# WMHS_Team_A_Mission_Possible_Electrical.net
KiCad netlist of a schematic drawn in EAGLE
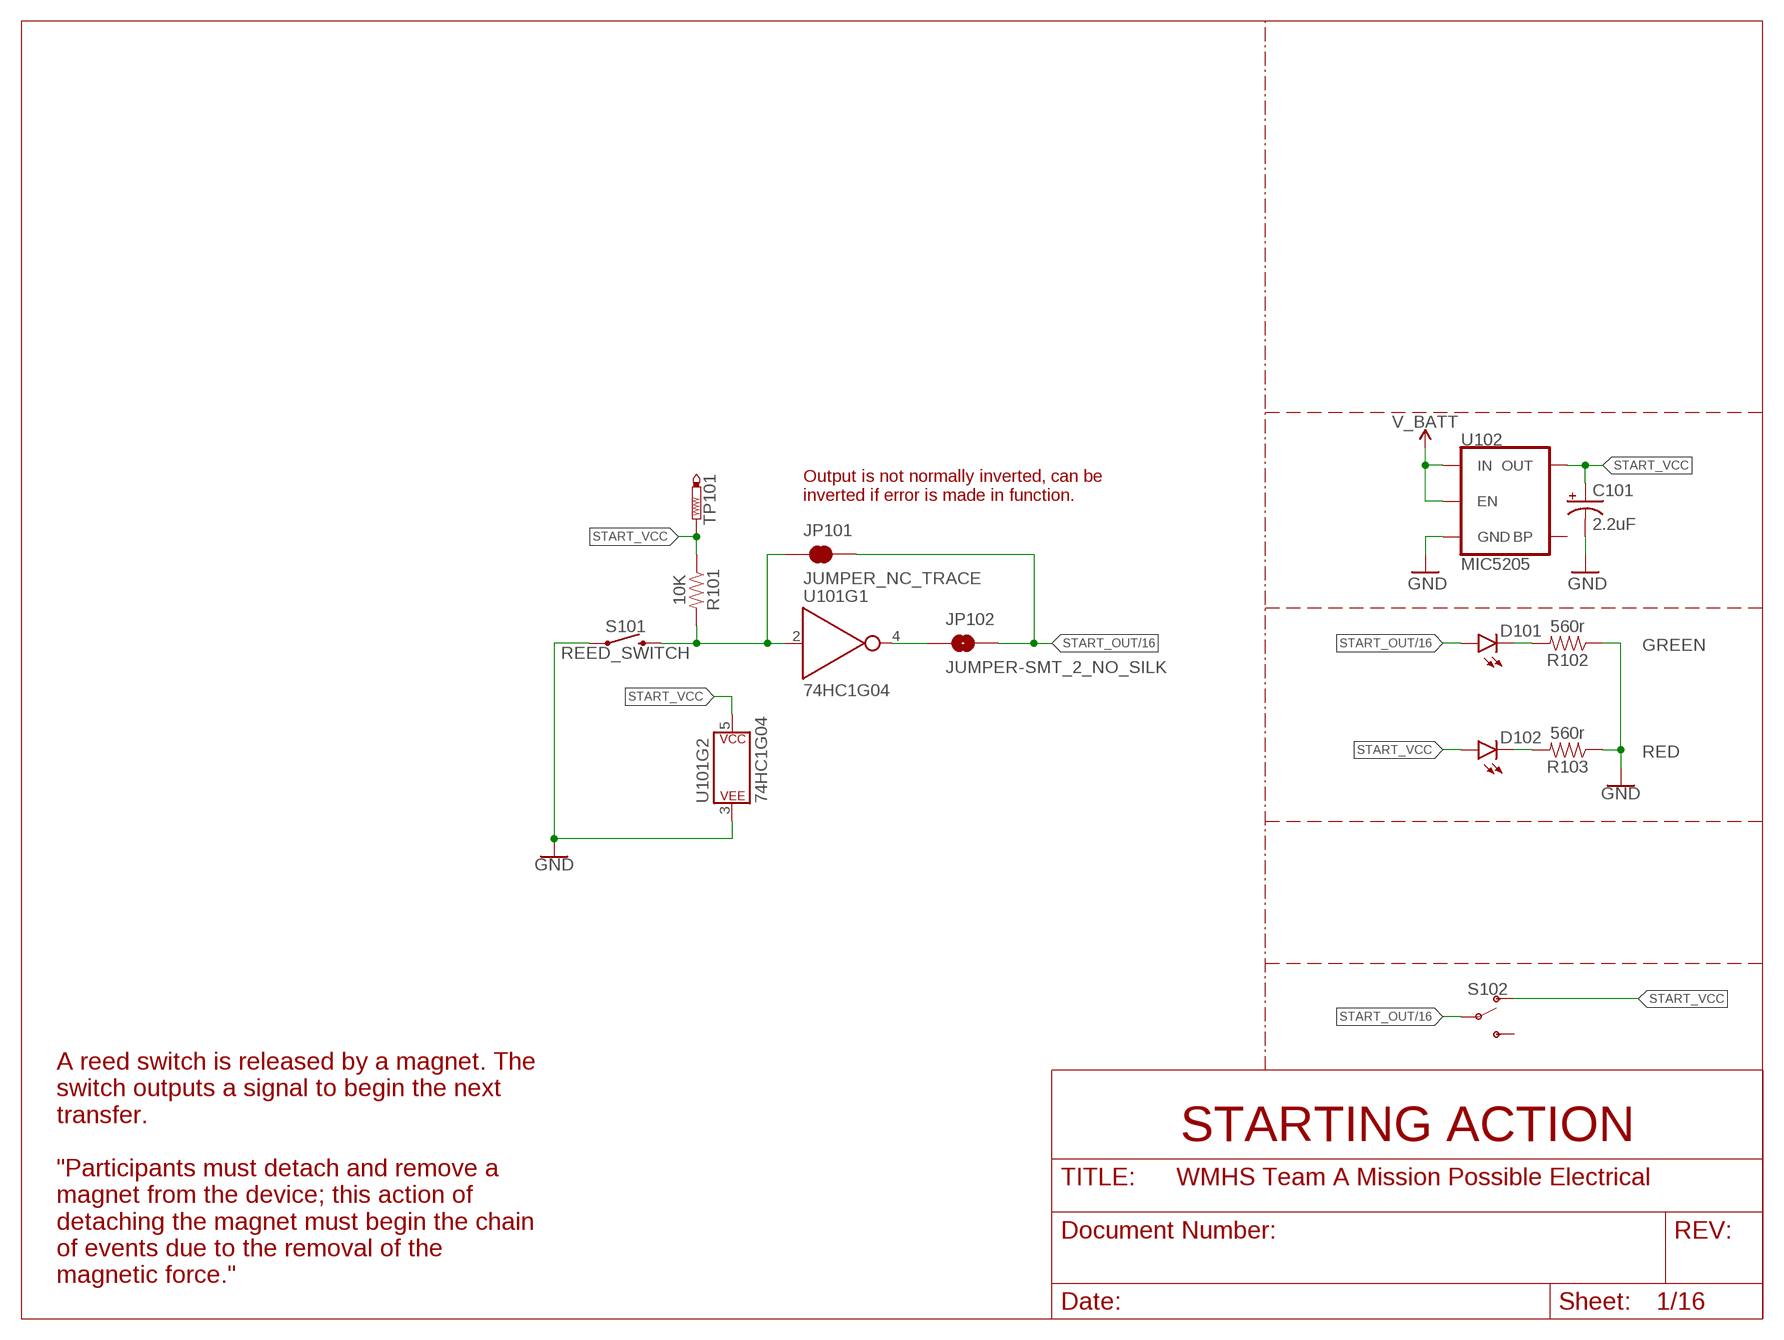
[diagram p0: schematic, sheet 1]
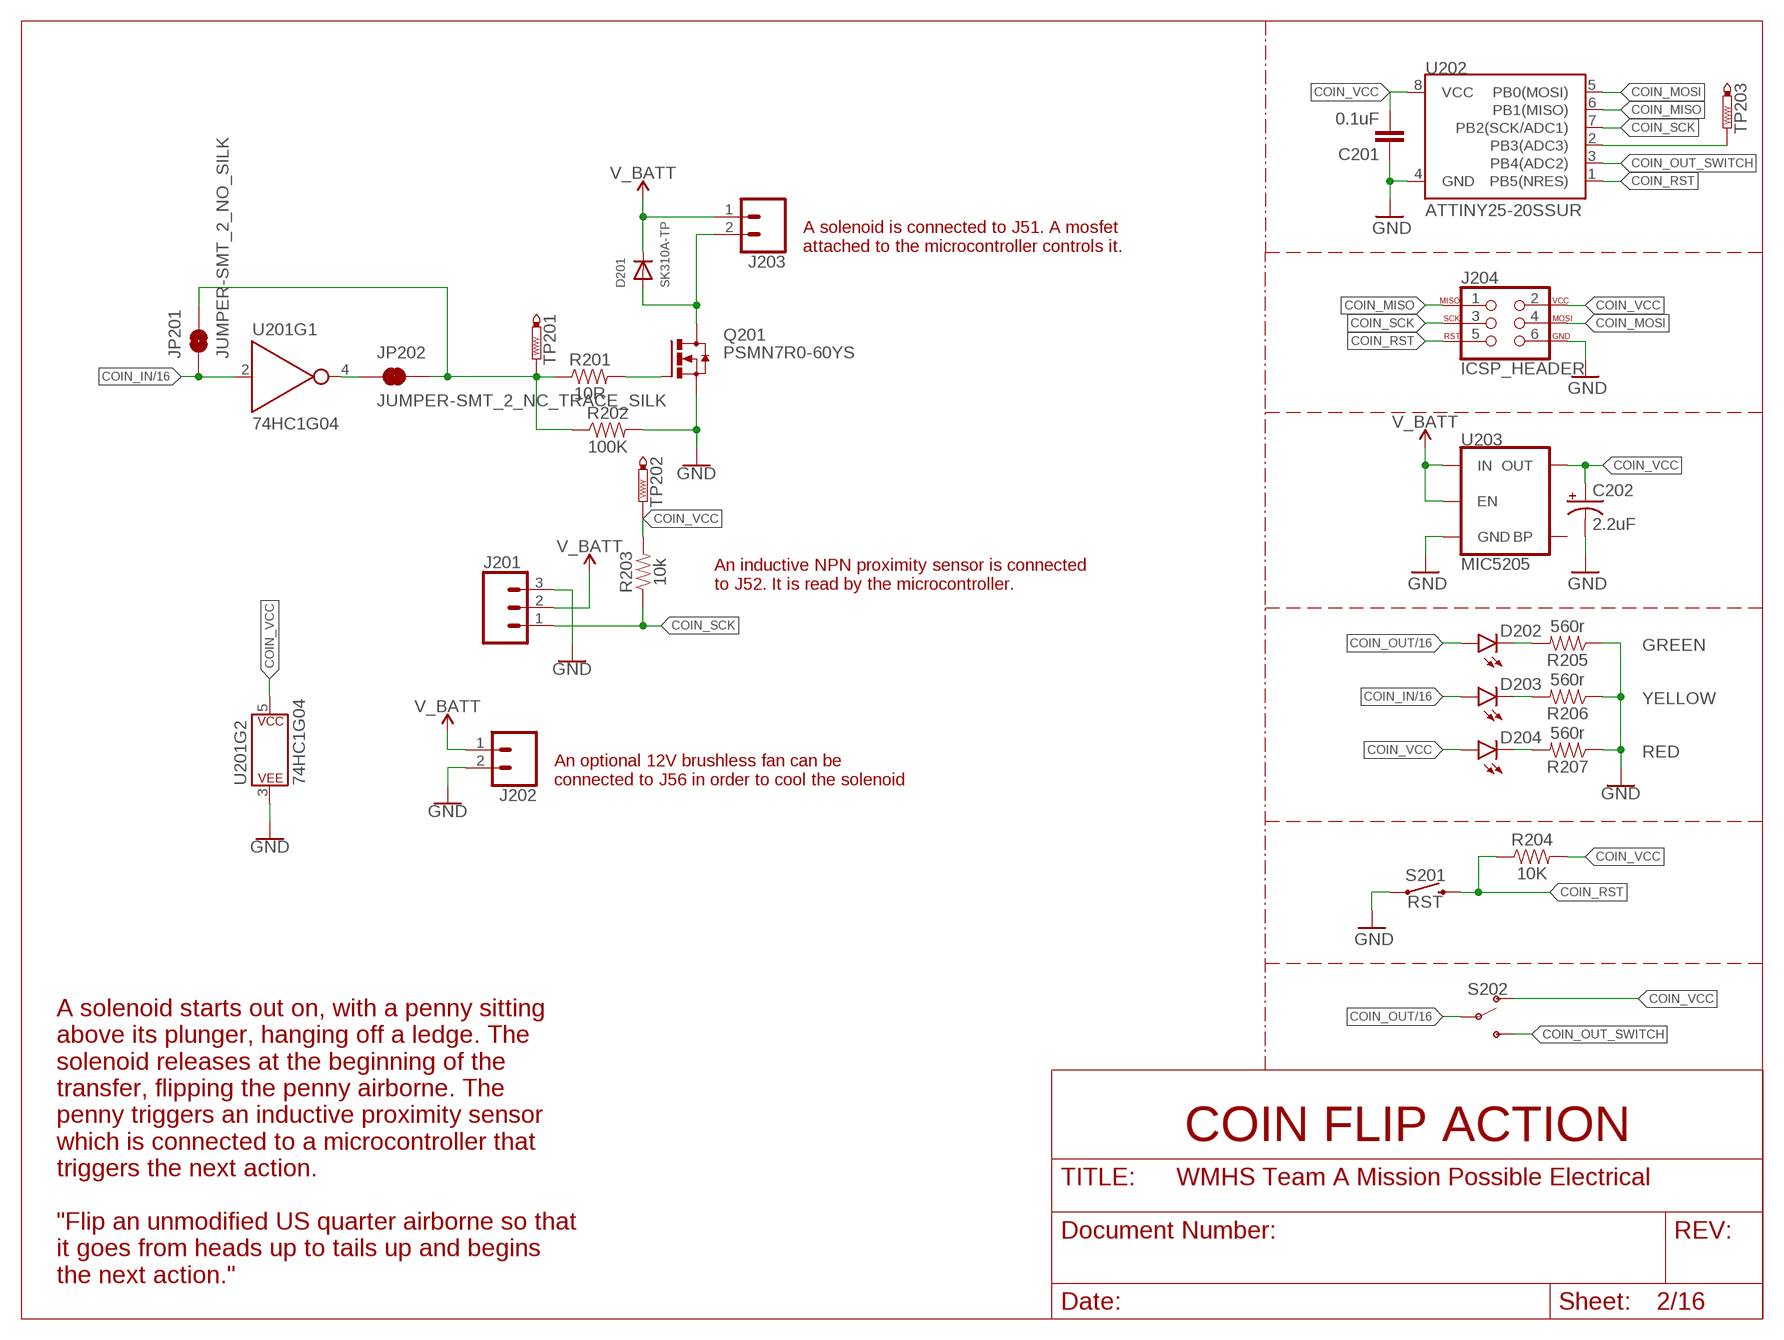
[diagram p1: schematic, sheet 2]
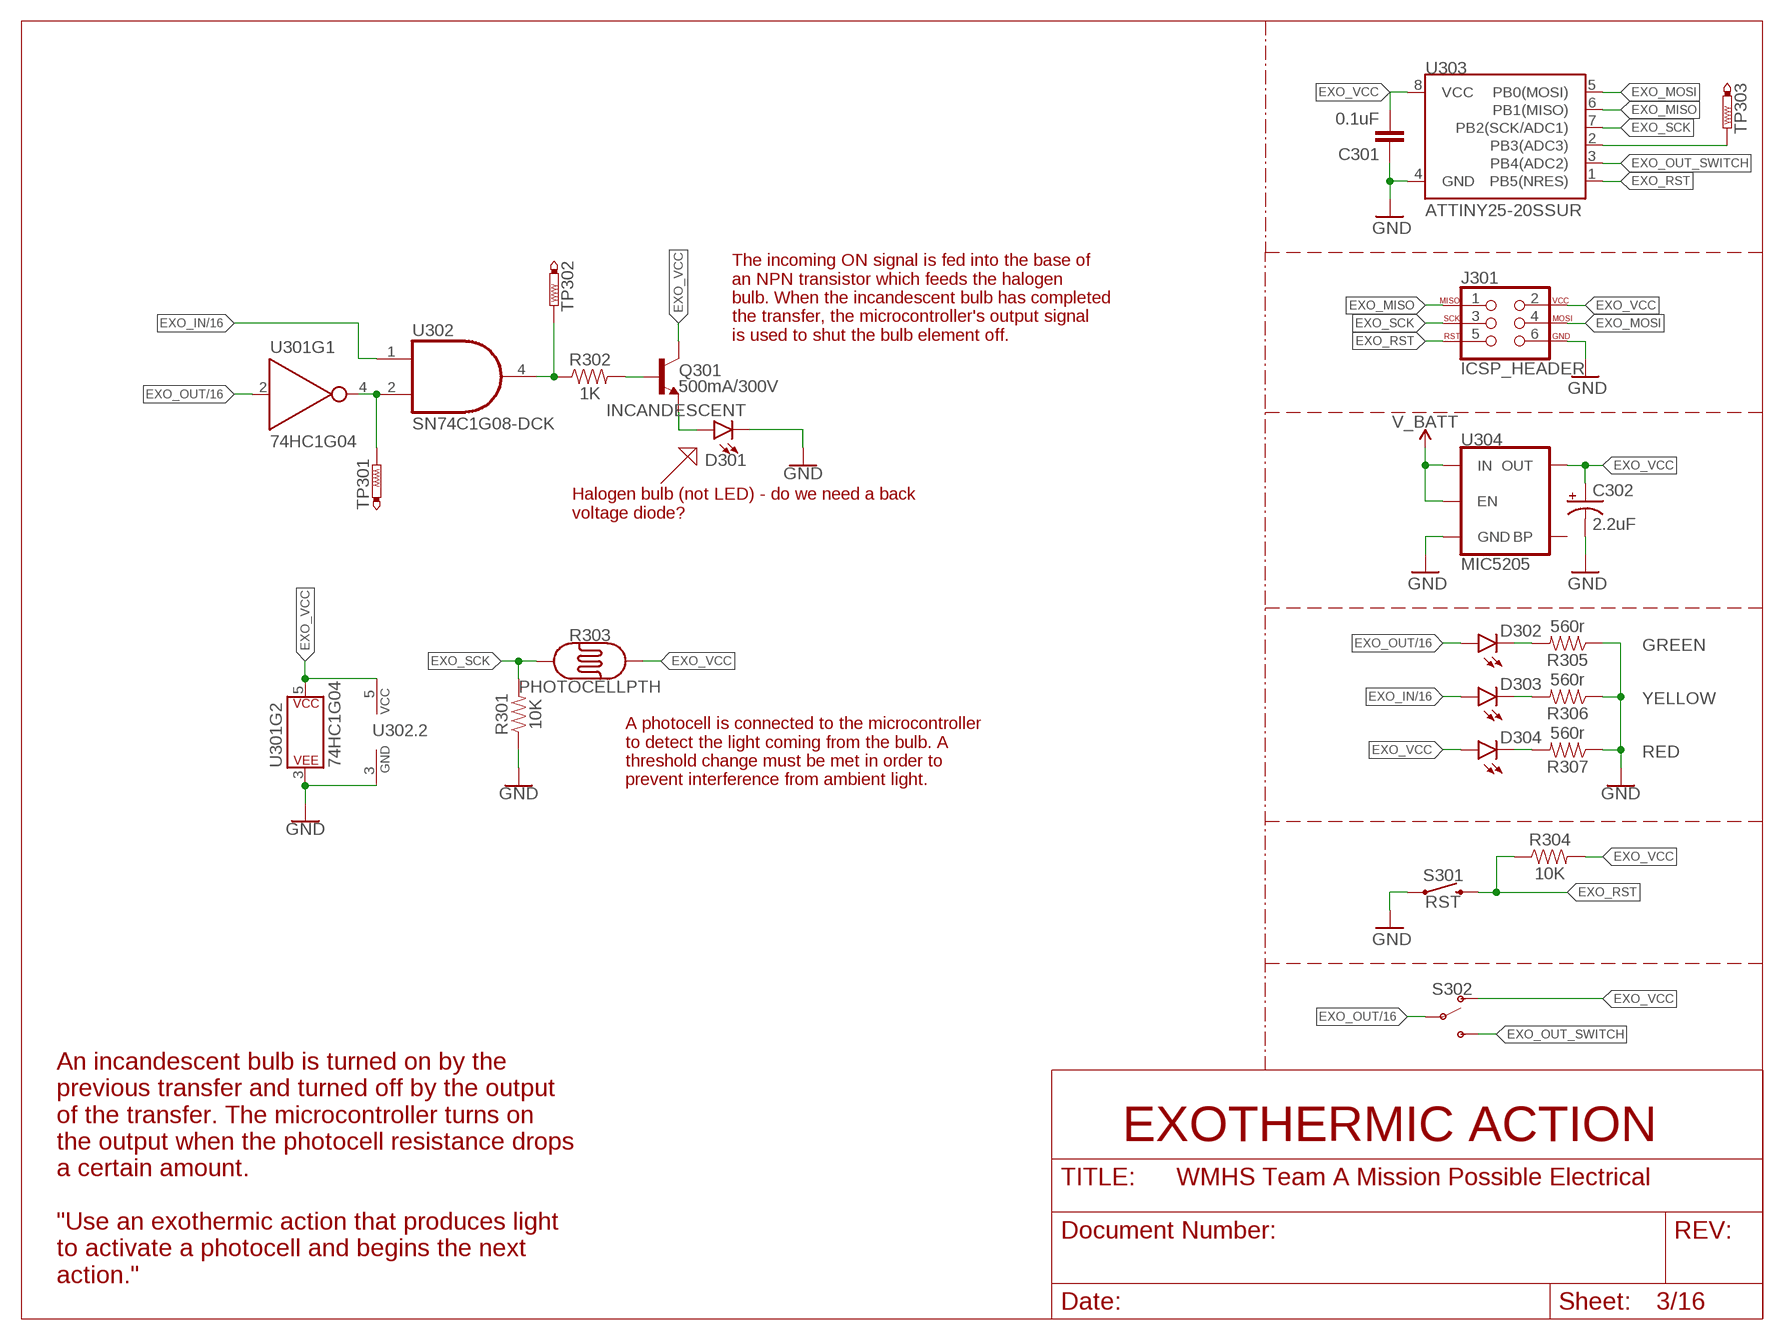
[diagram p2: schematic, sheet 3]
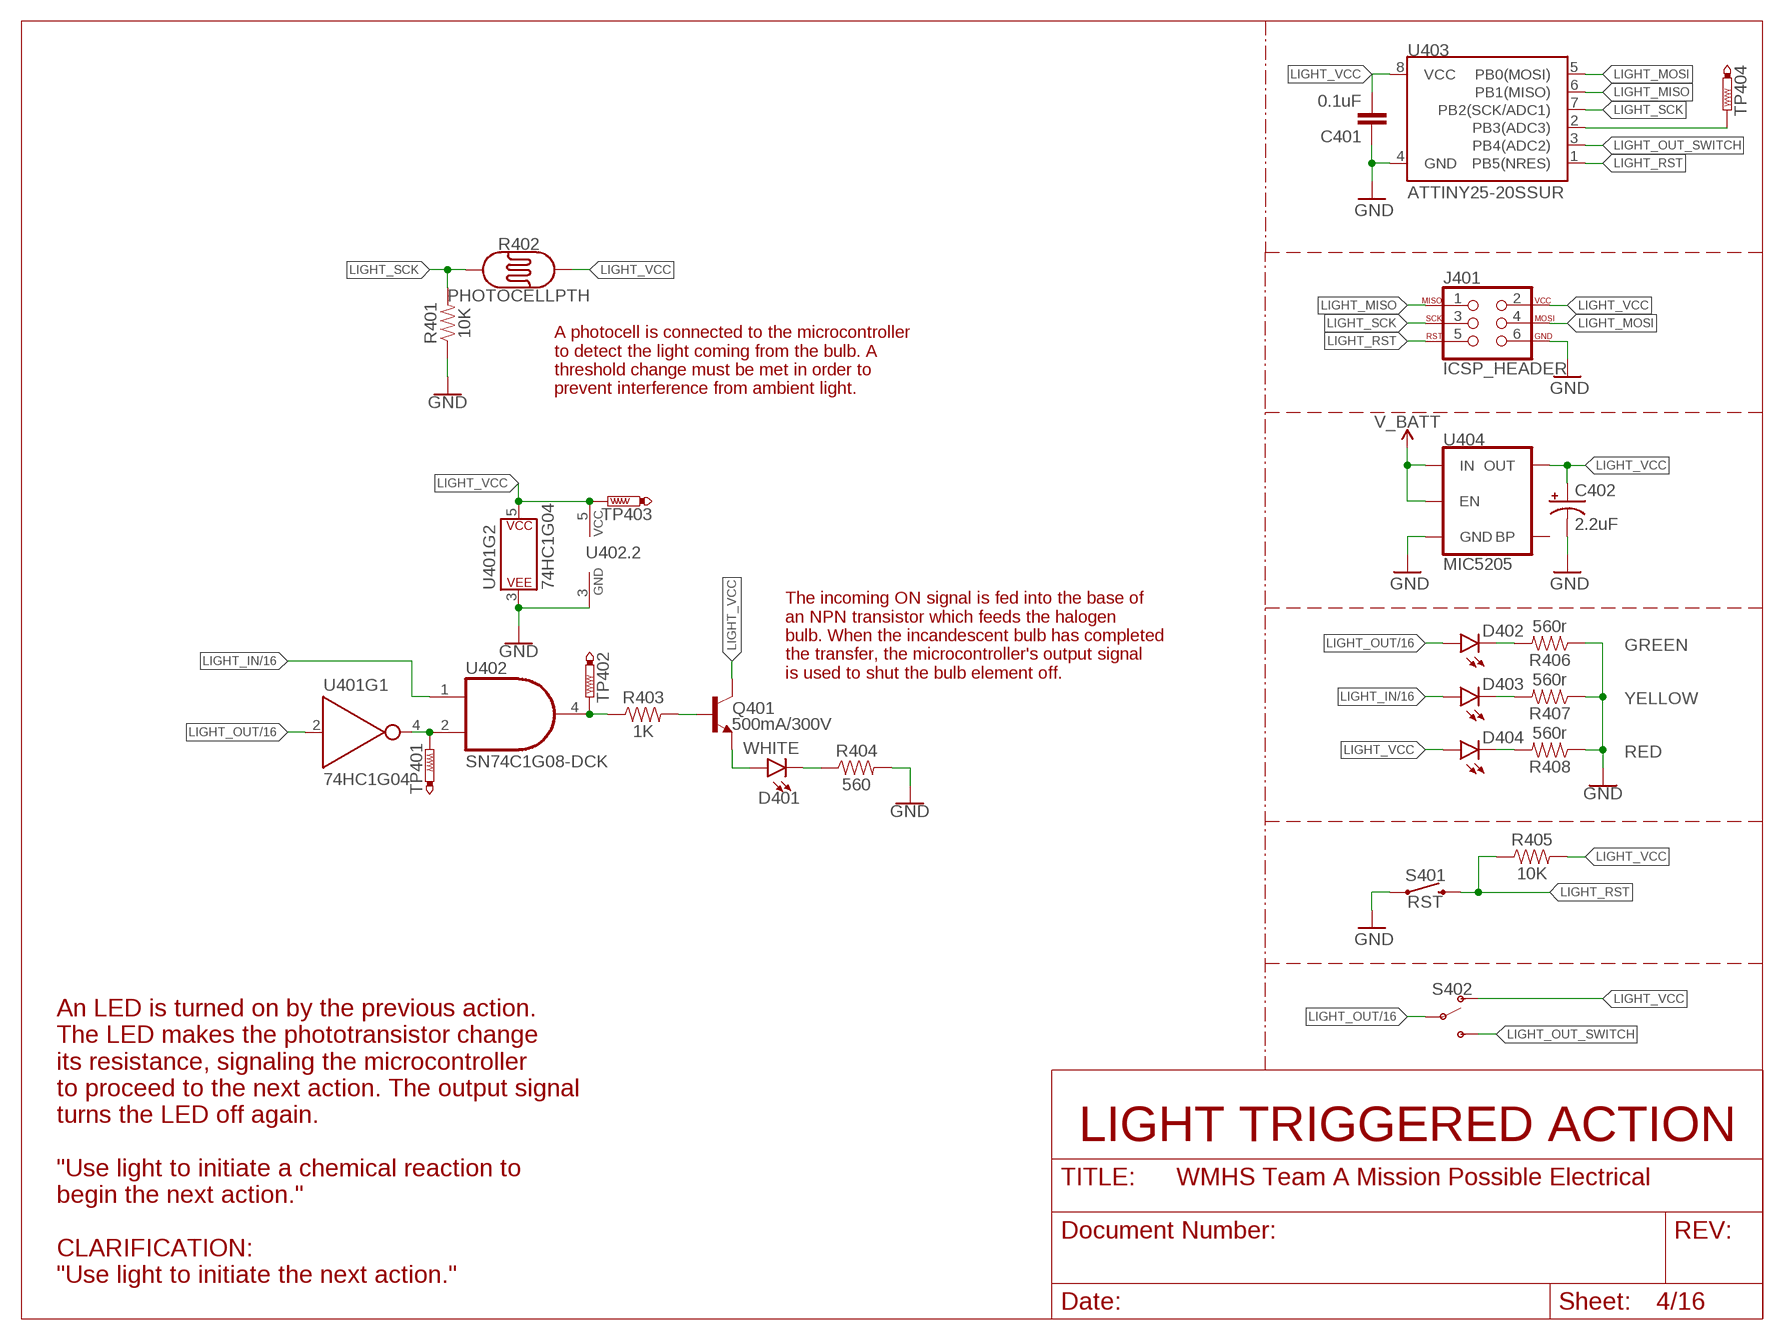
[diagram p3: schematic, sheet 4]
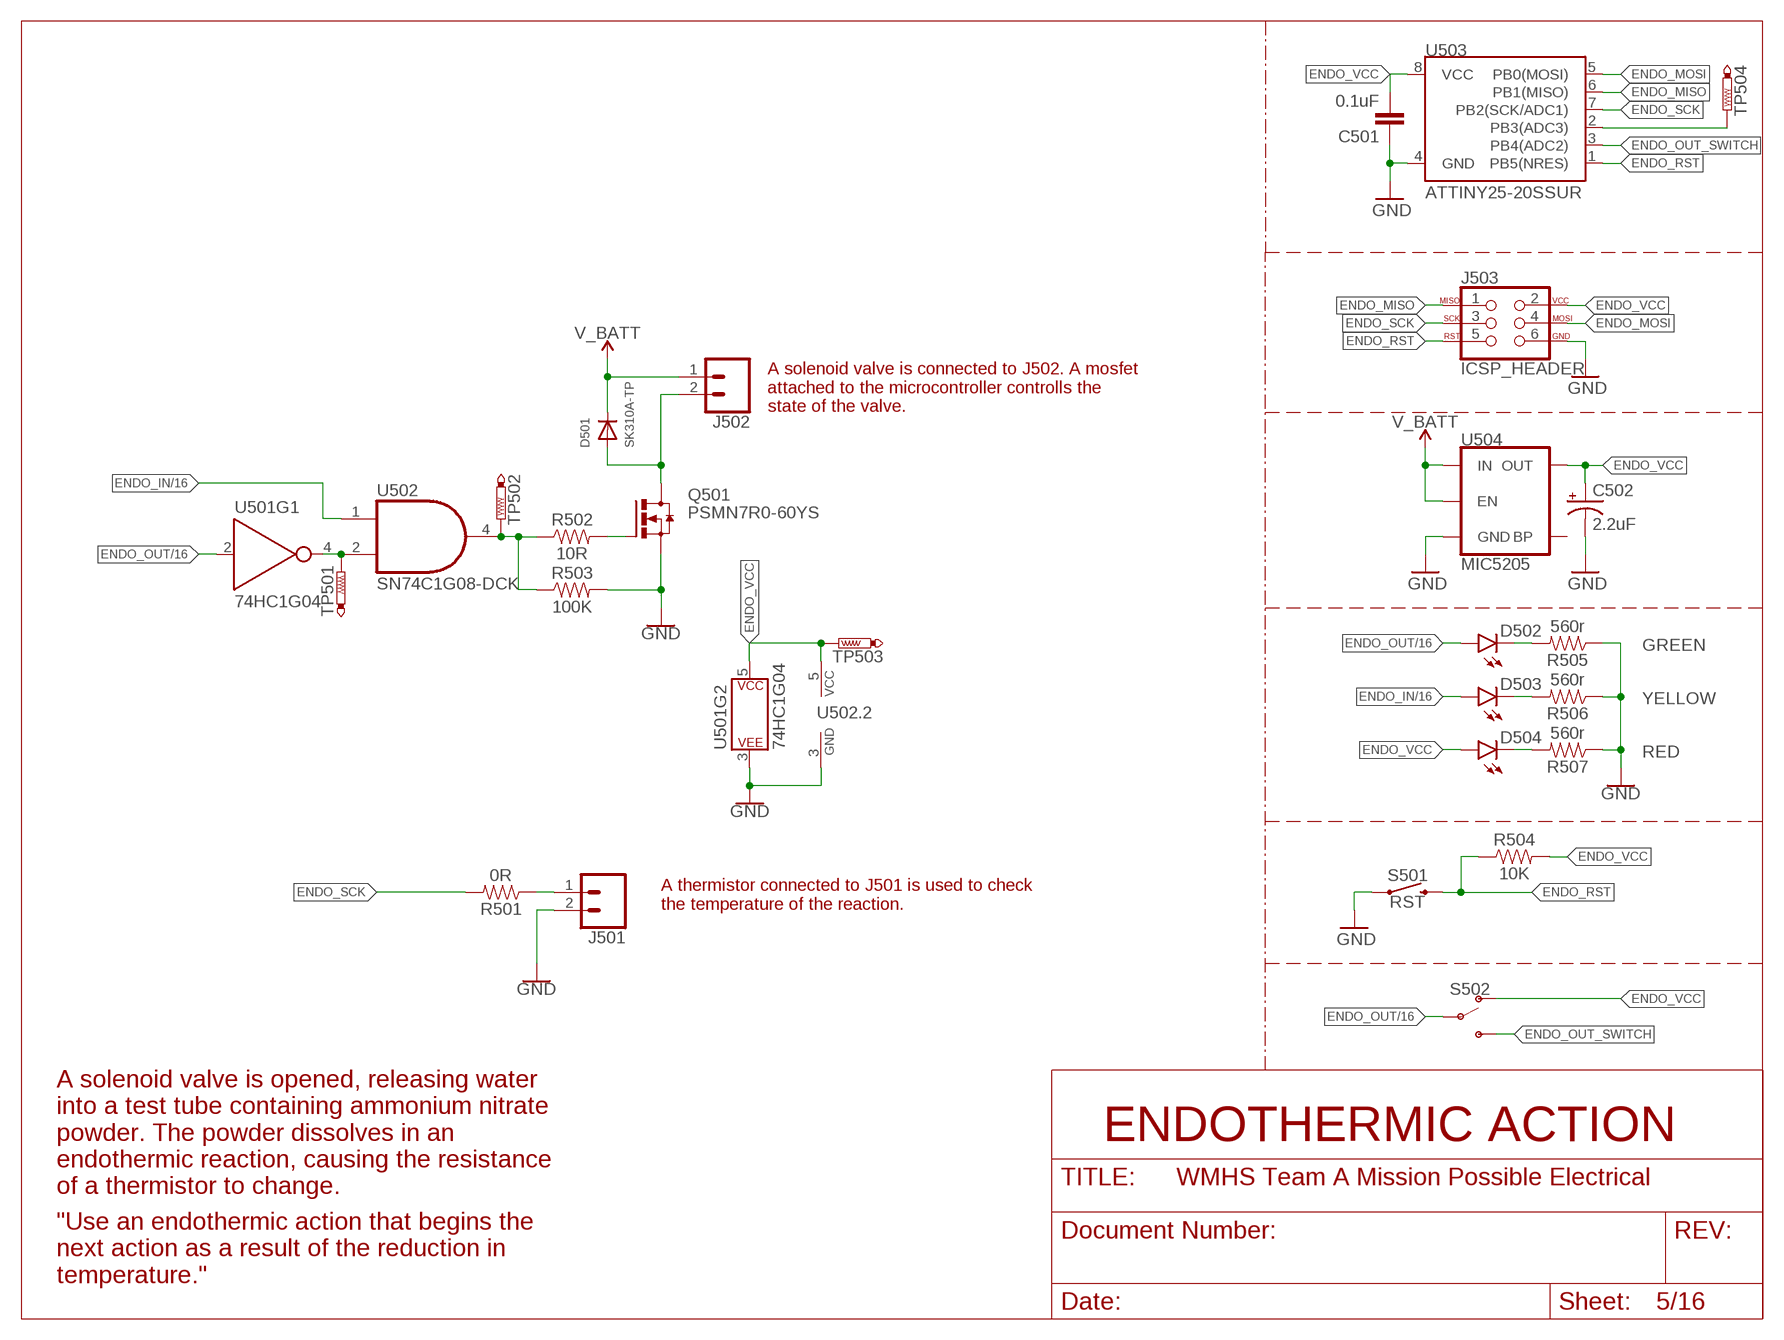
[diagram p4: schematic, sheet 5]
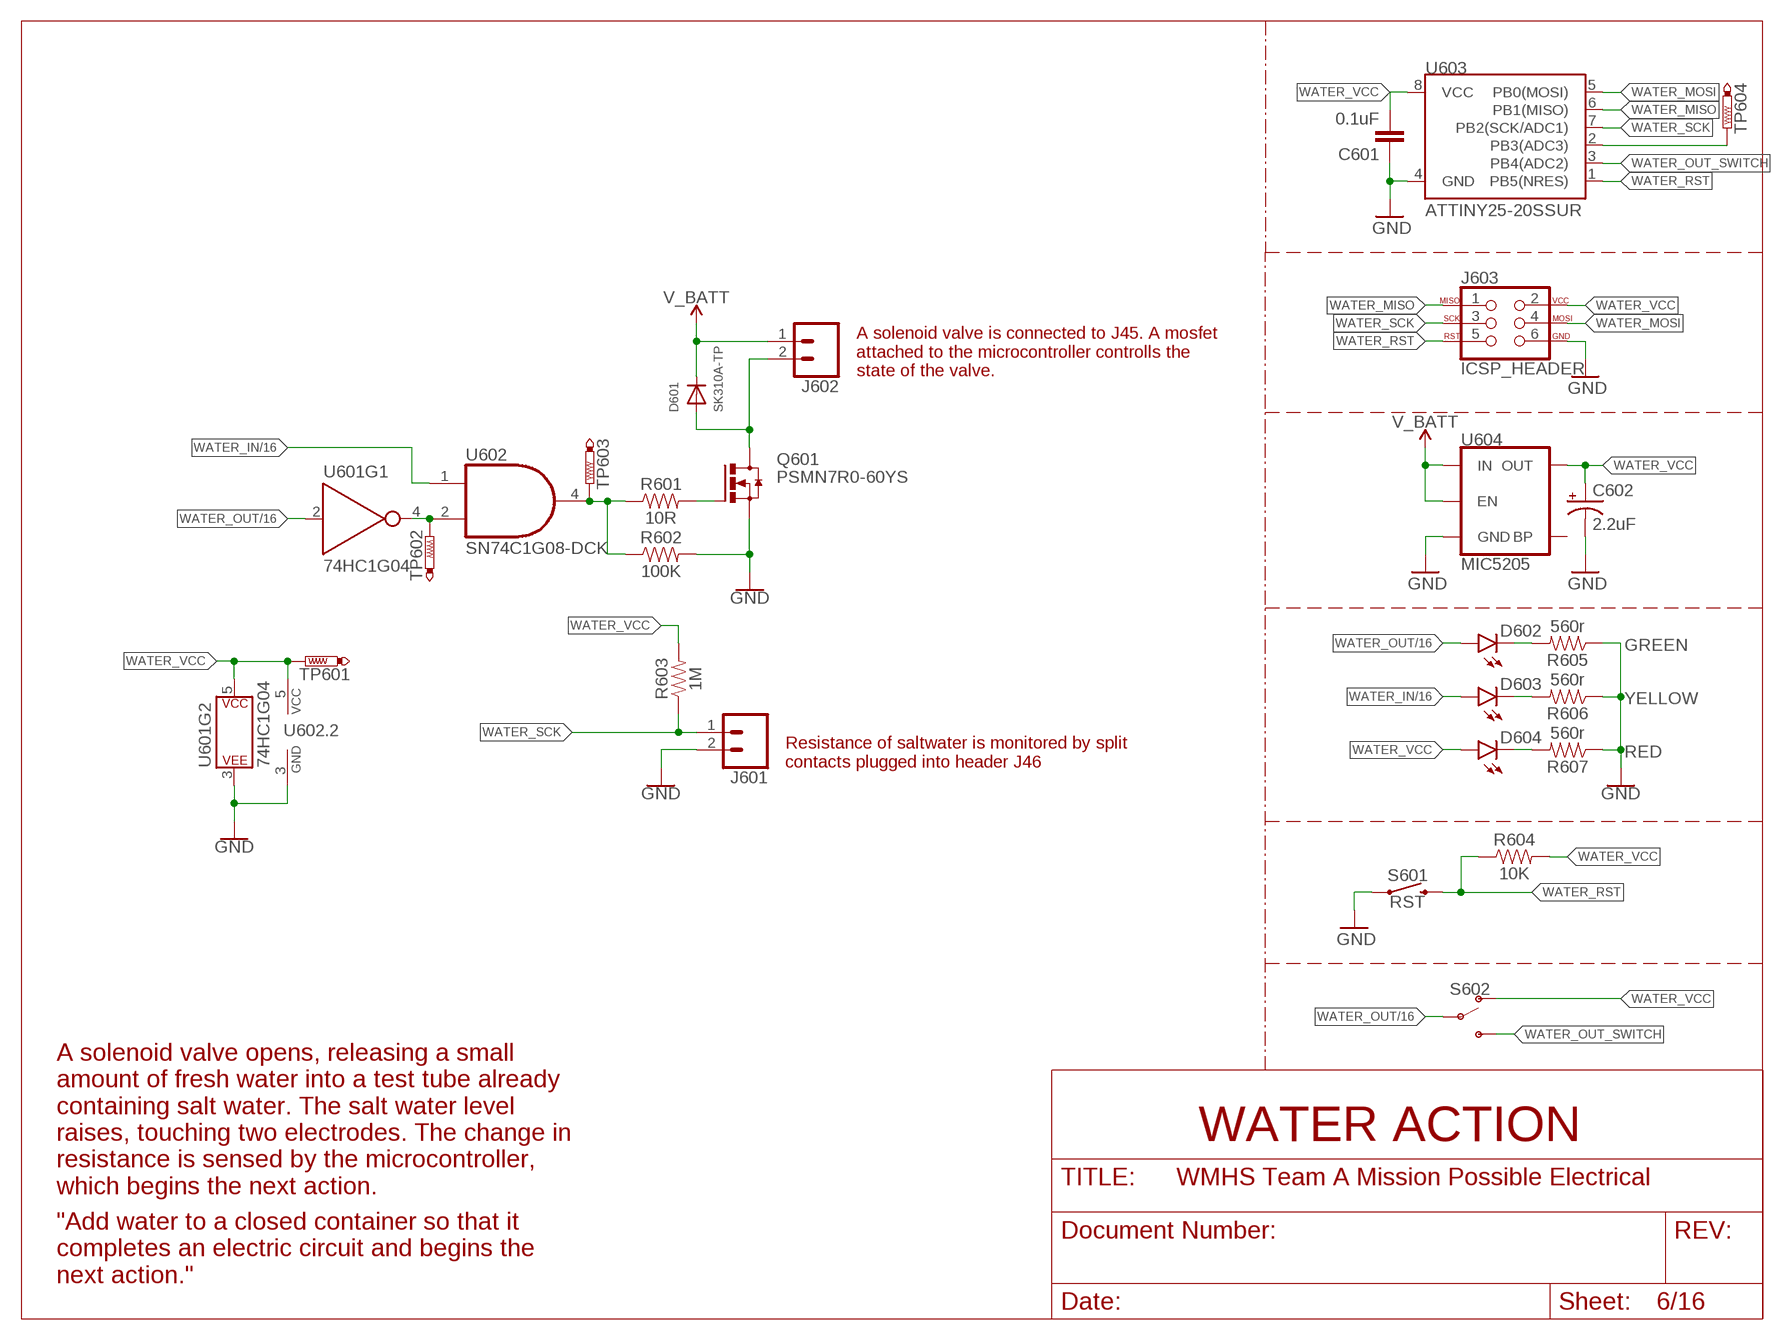
[diagram p5: schematic, sheet 6]
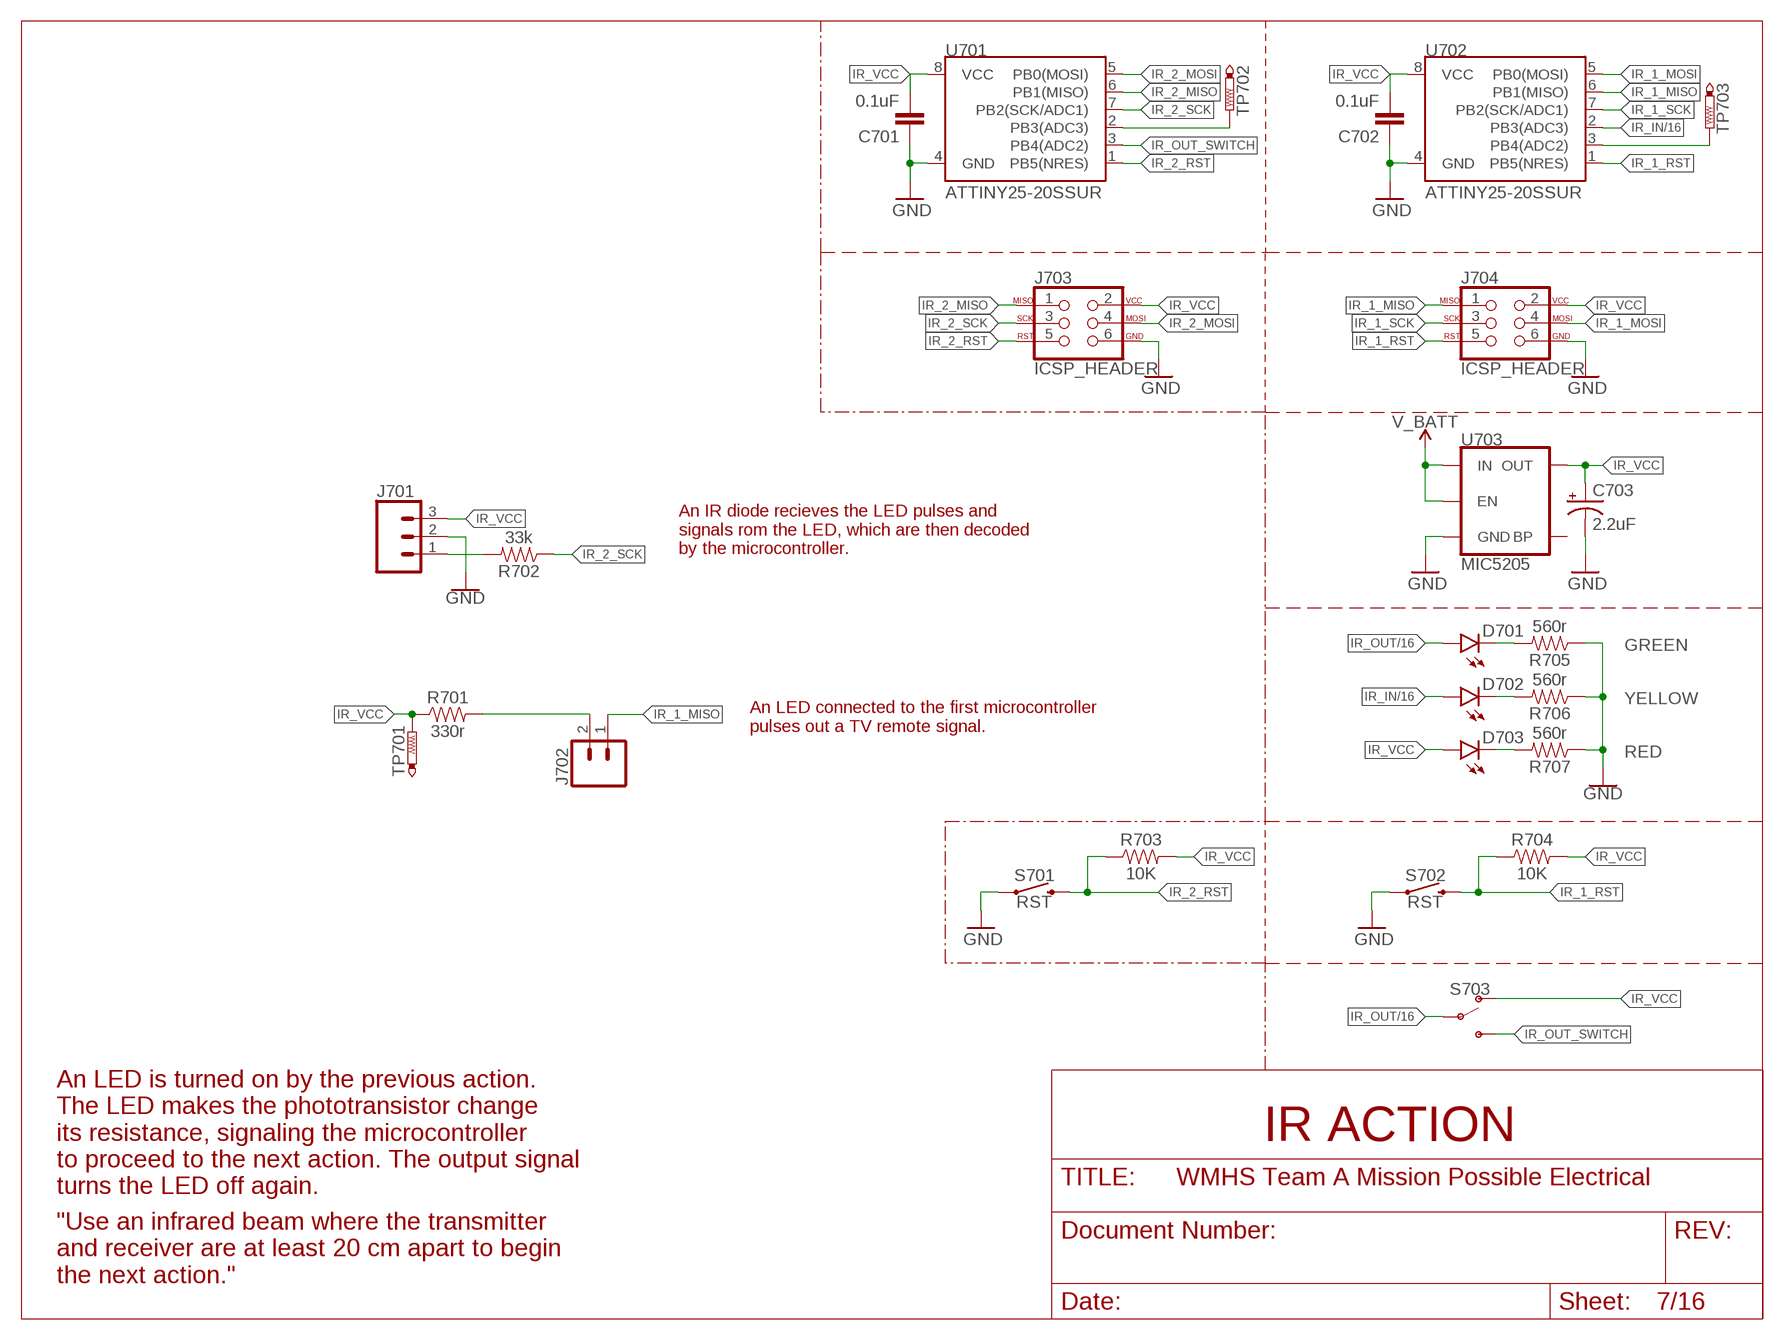
[diagram p6: schematic, sheet 7]
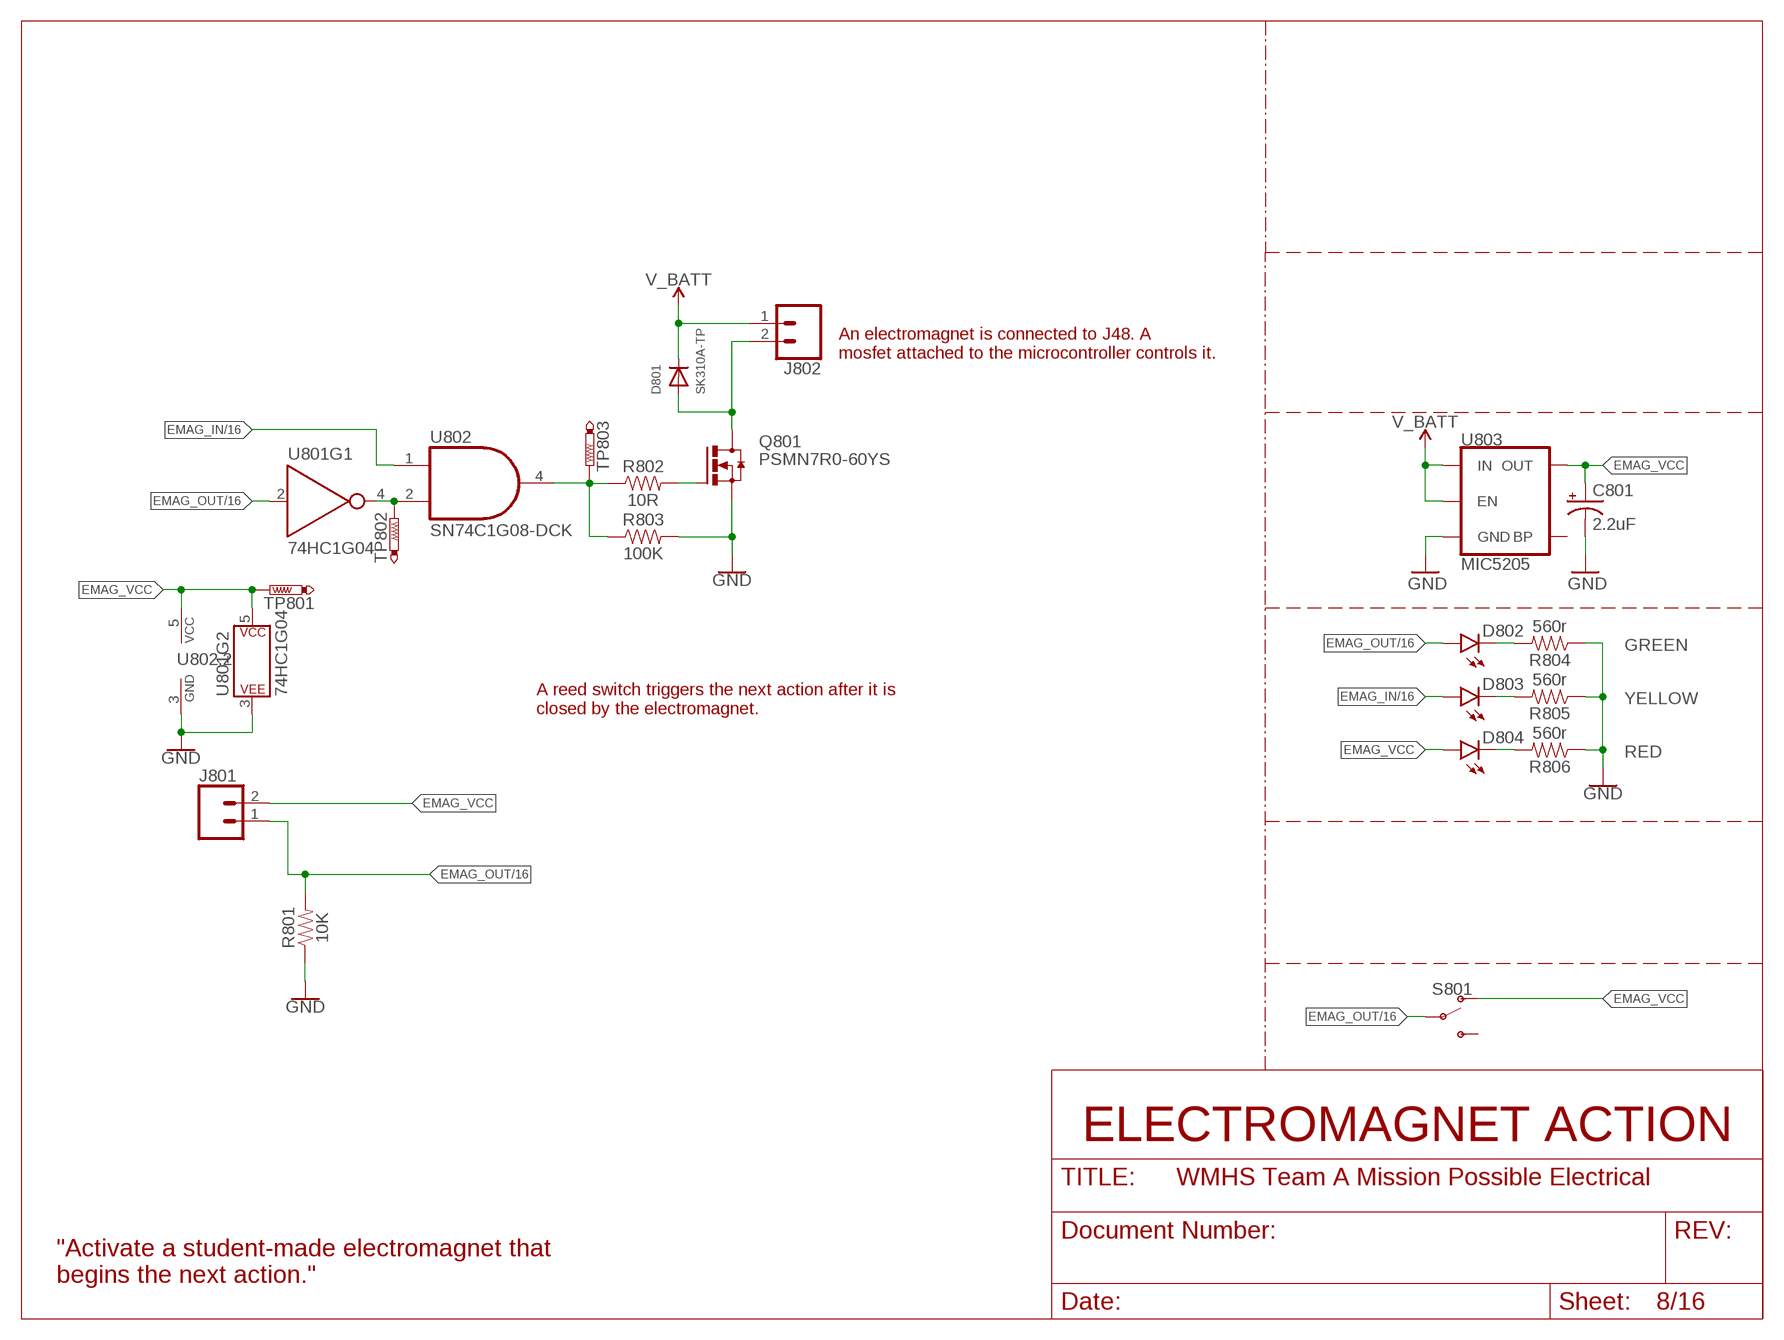
[diagram p7: schematic, sheet 8]
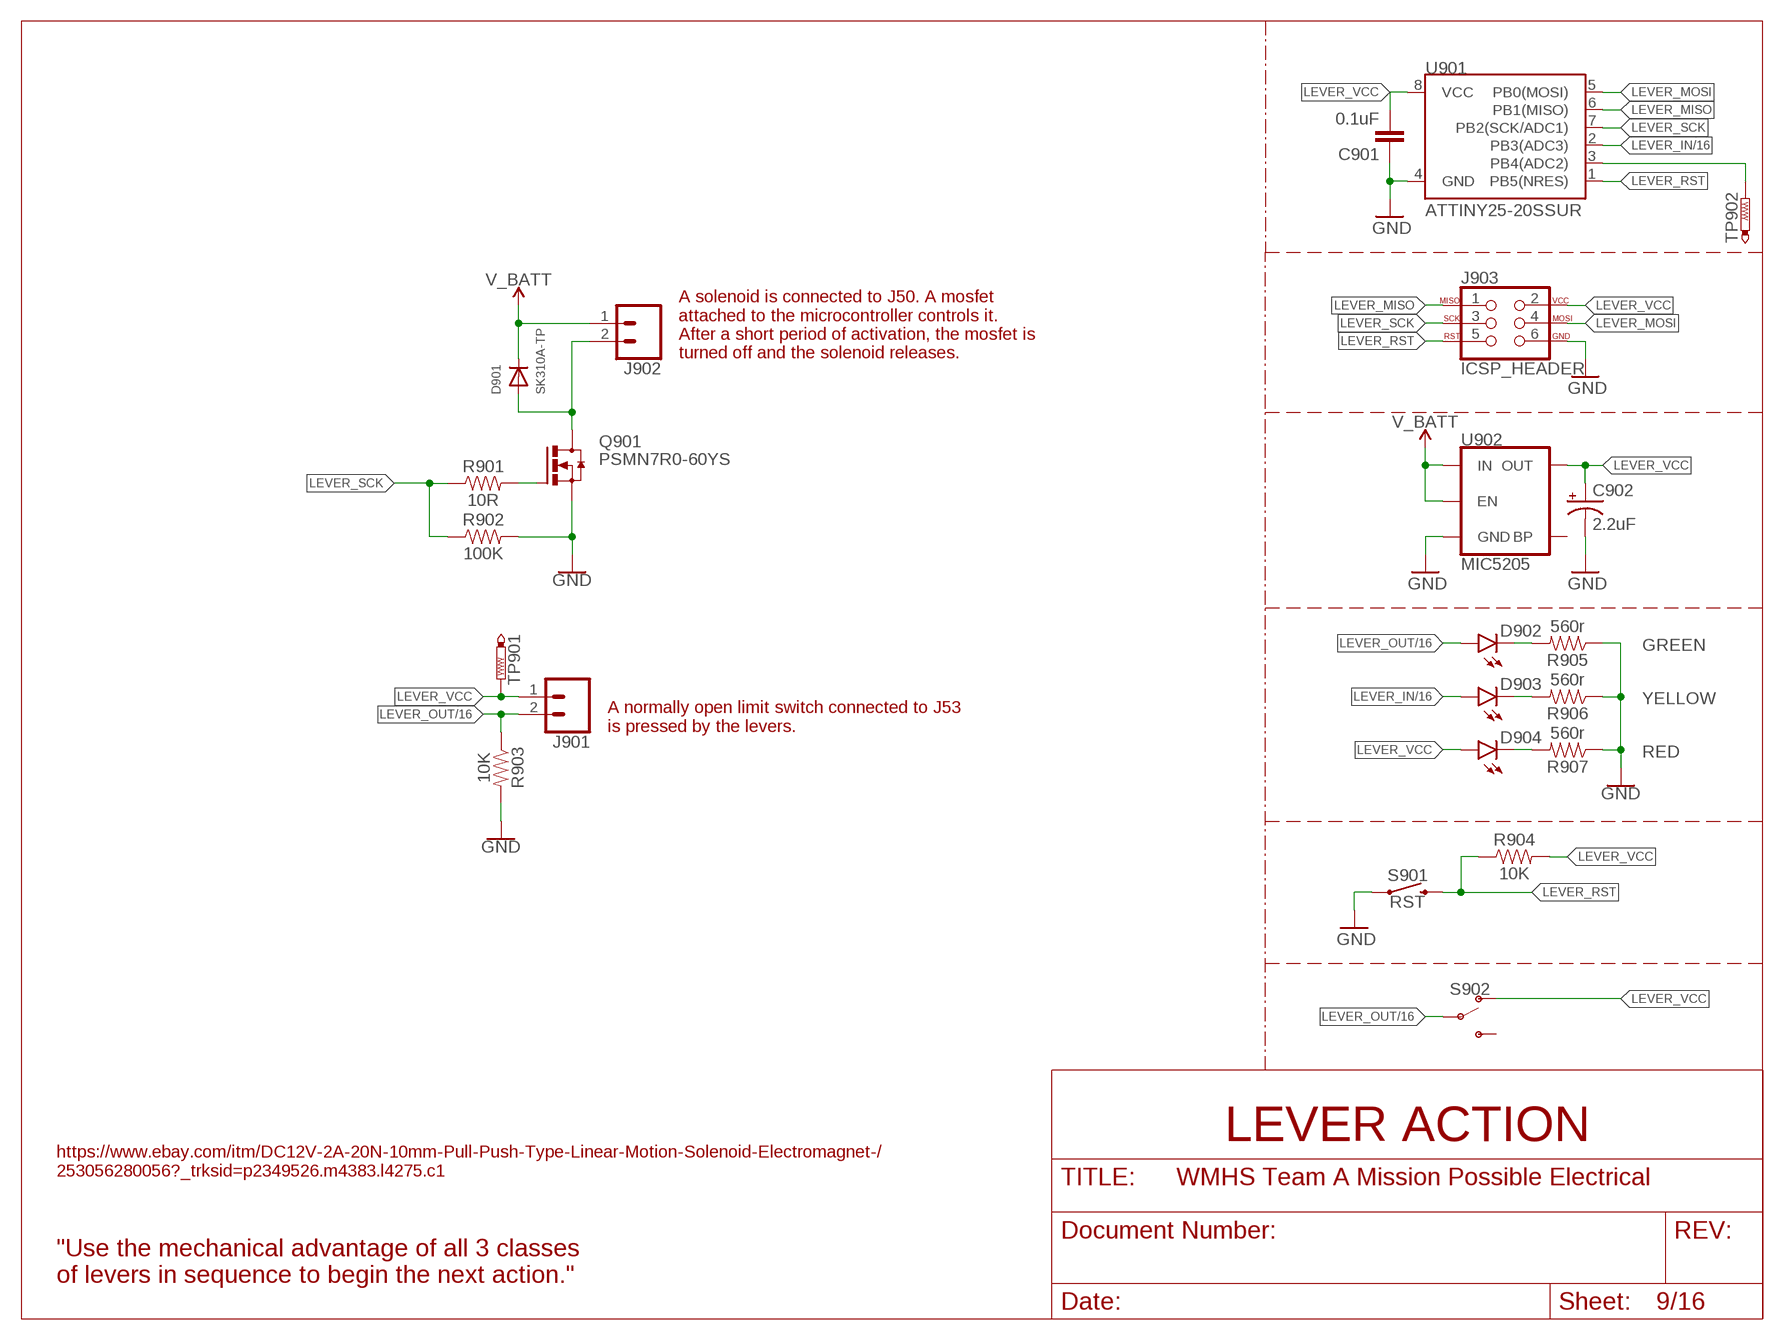
[diagram p8: schematic, sheet 9]
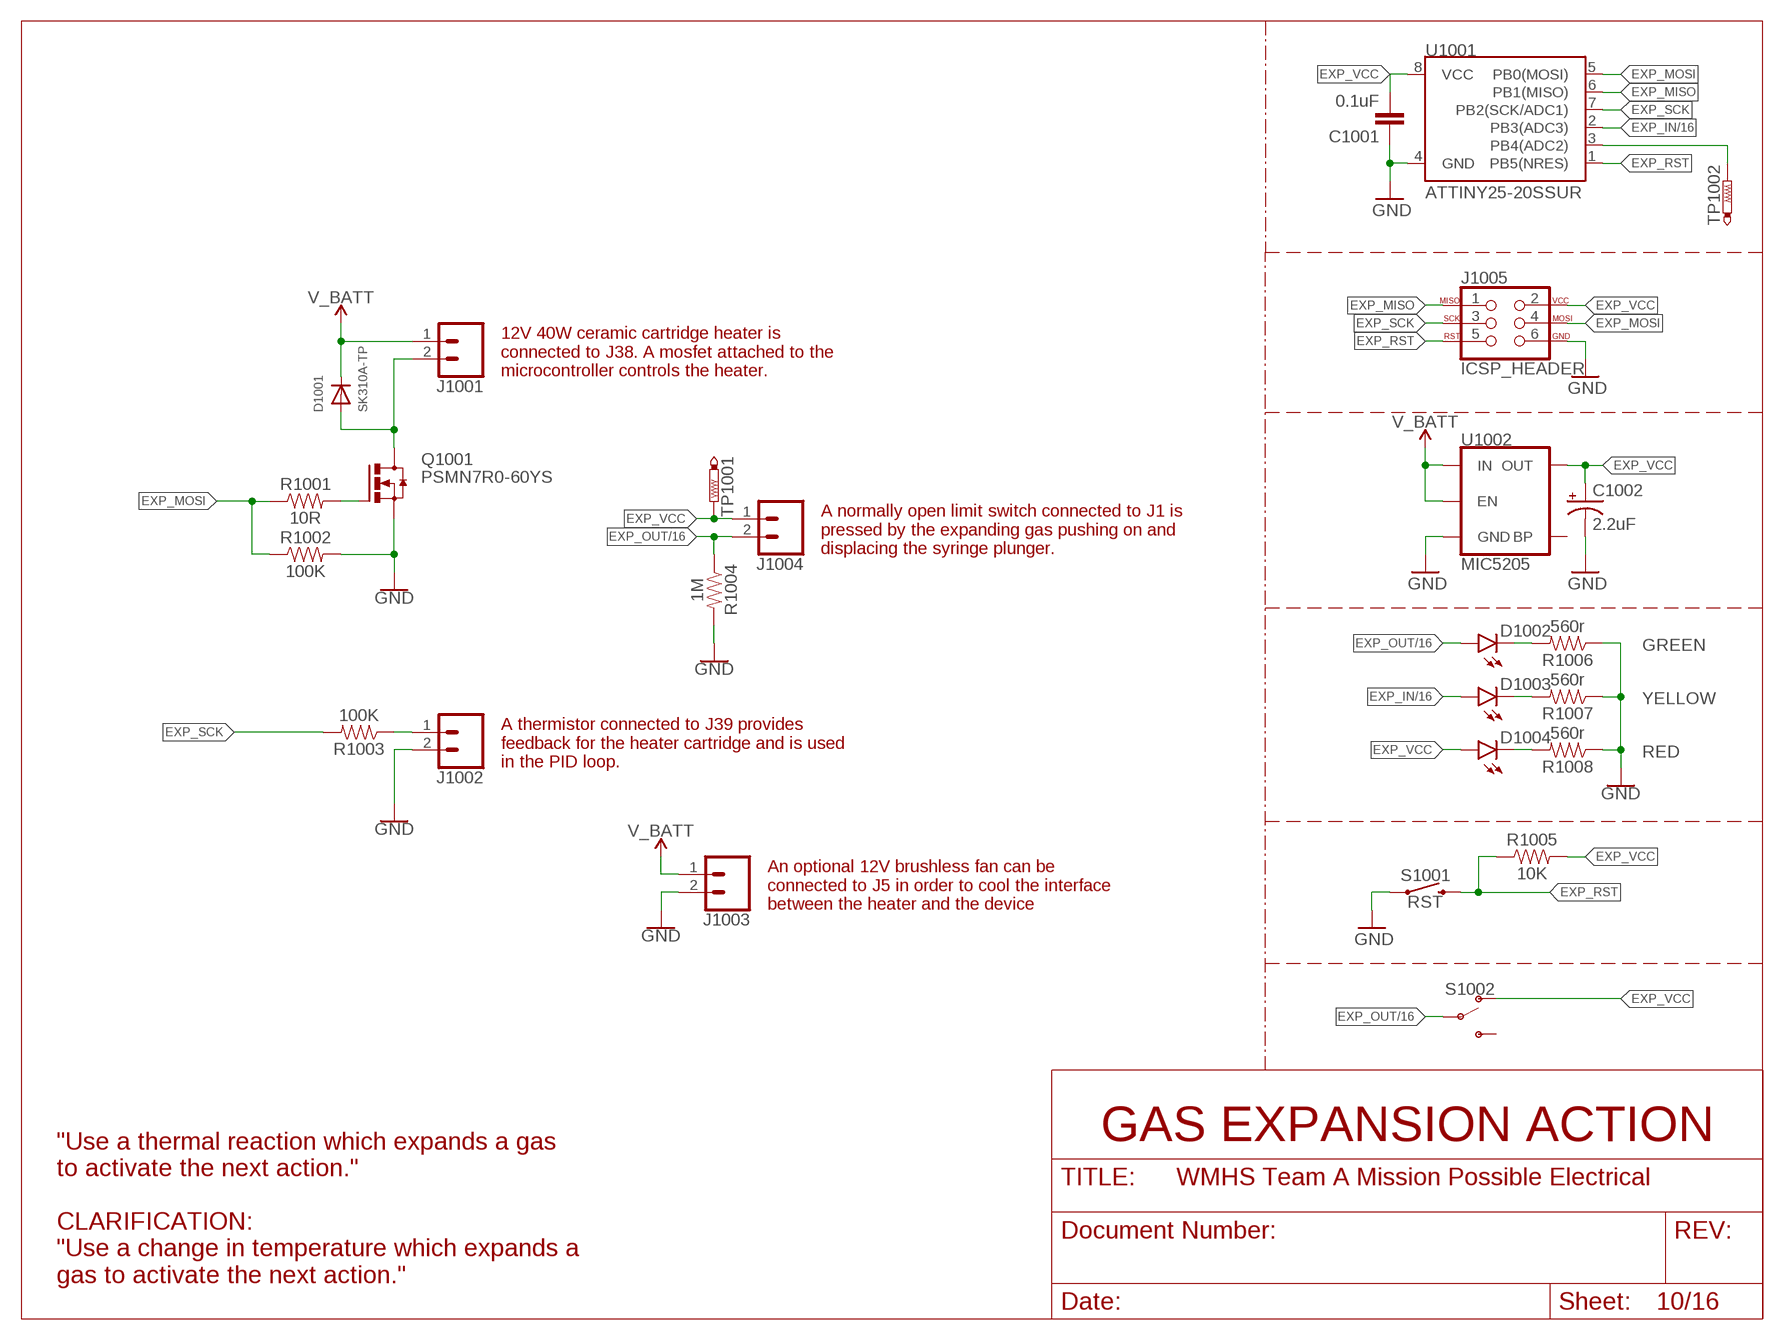
[diagram p9: schematic, sheet 10]
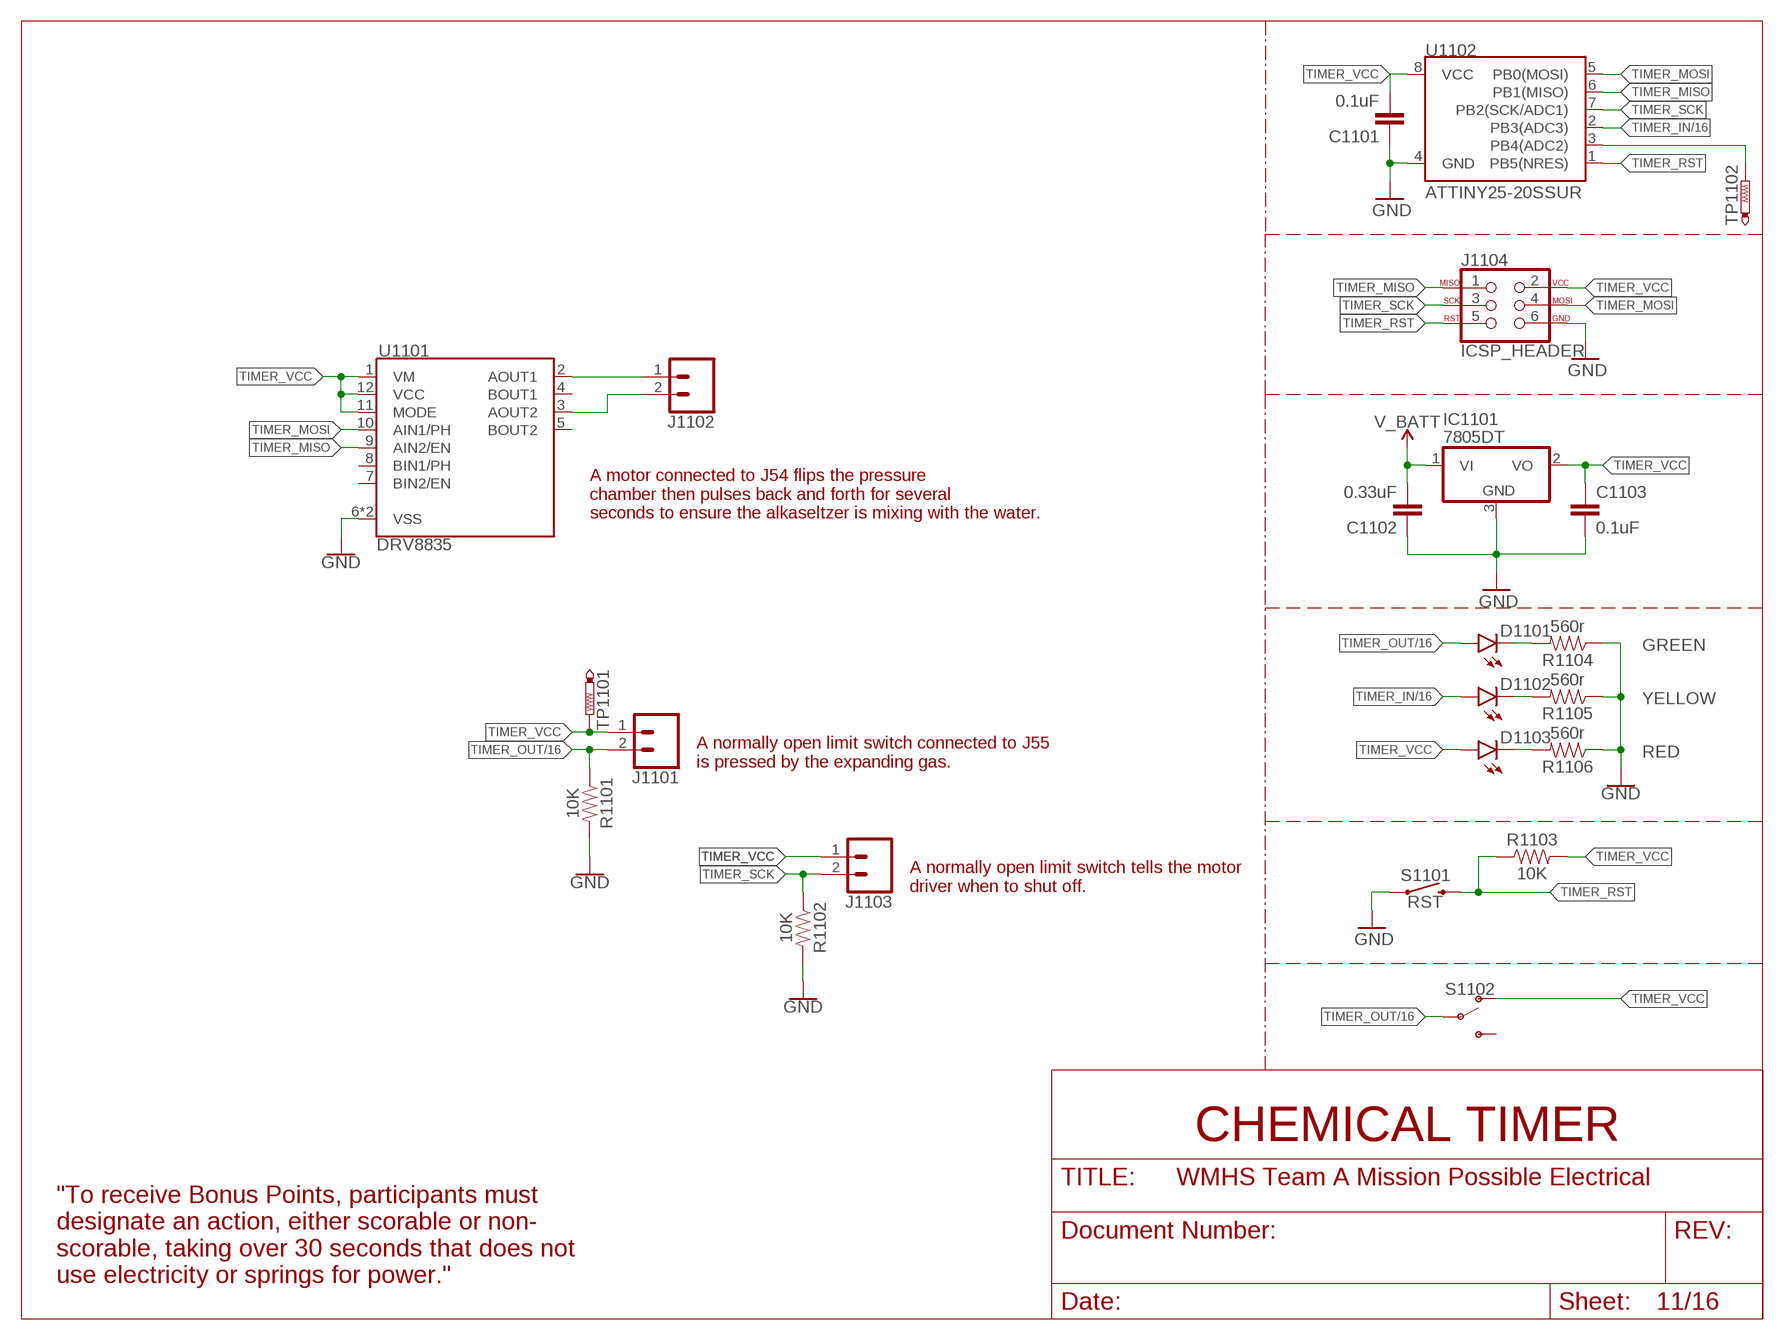
[diagram p10: schematic, sheet 11]
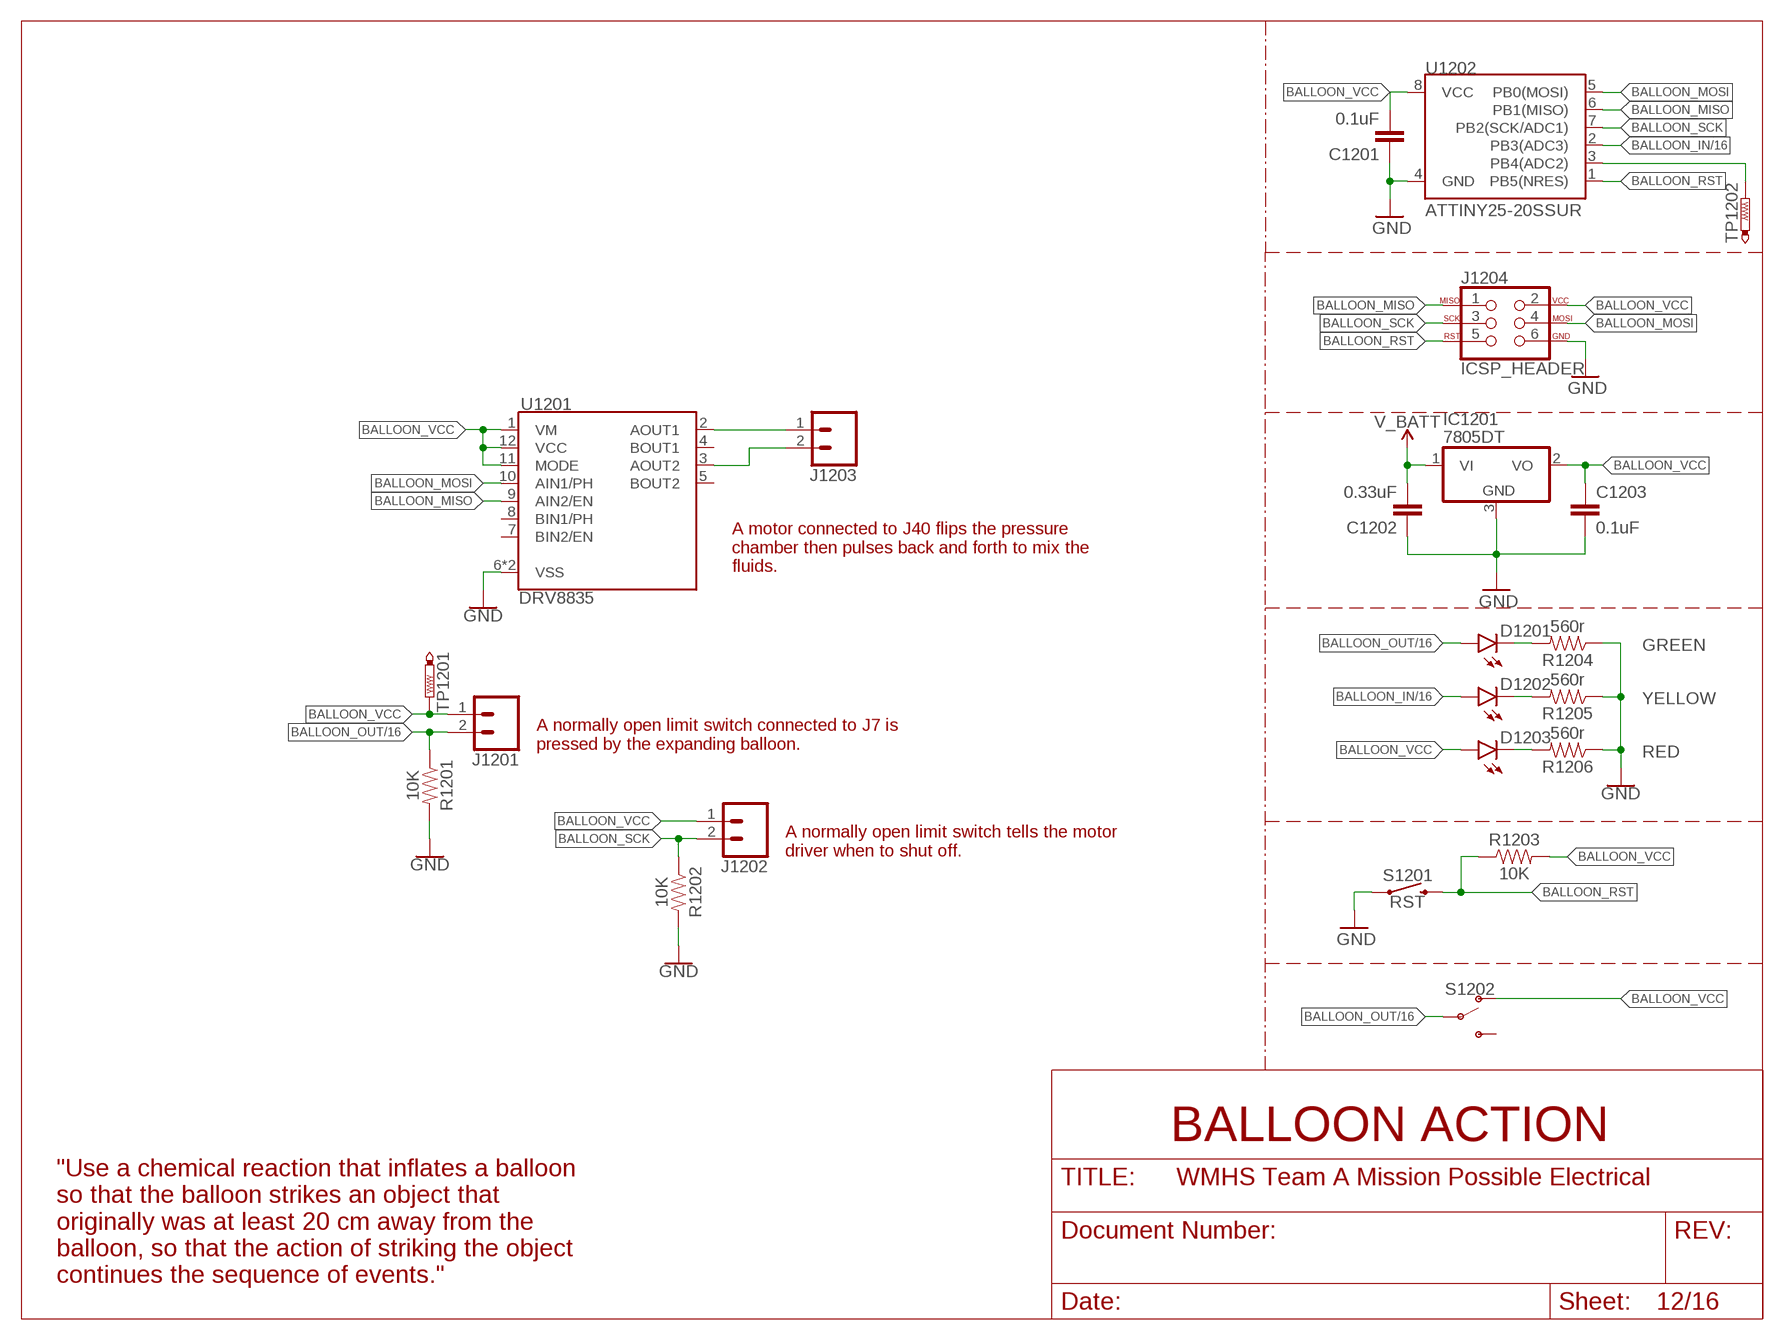
[diagram p11: schematic, sheet 12]
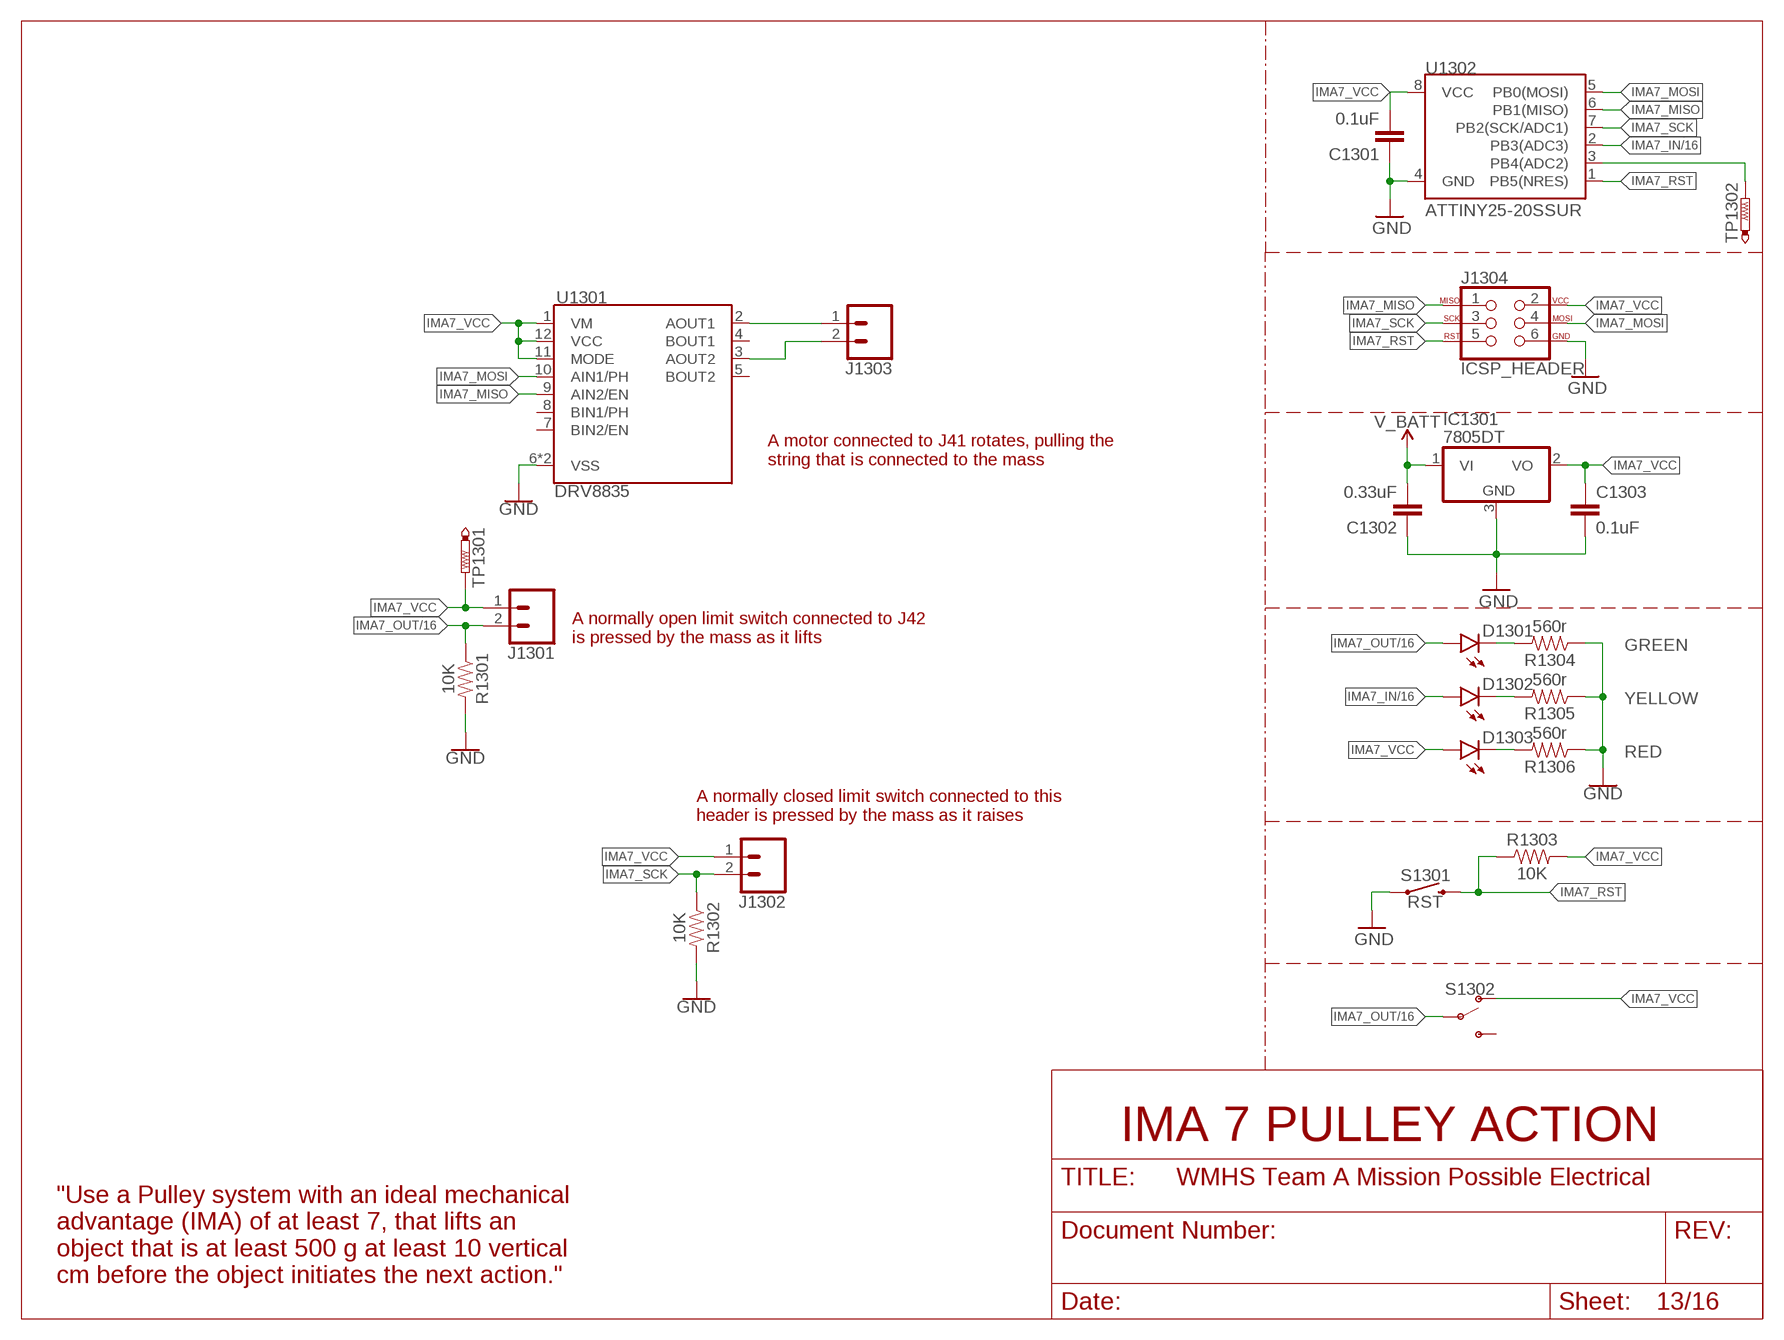
[diagram p12: schematic, sheet 13]
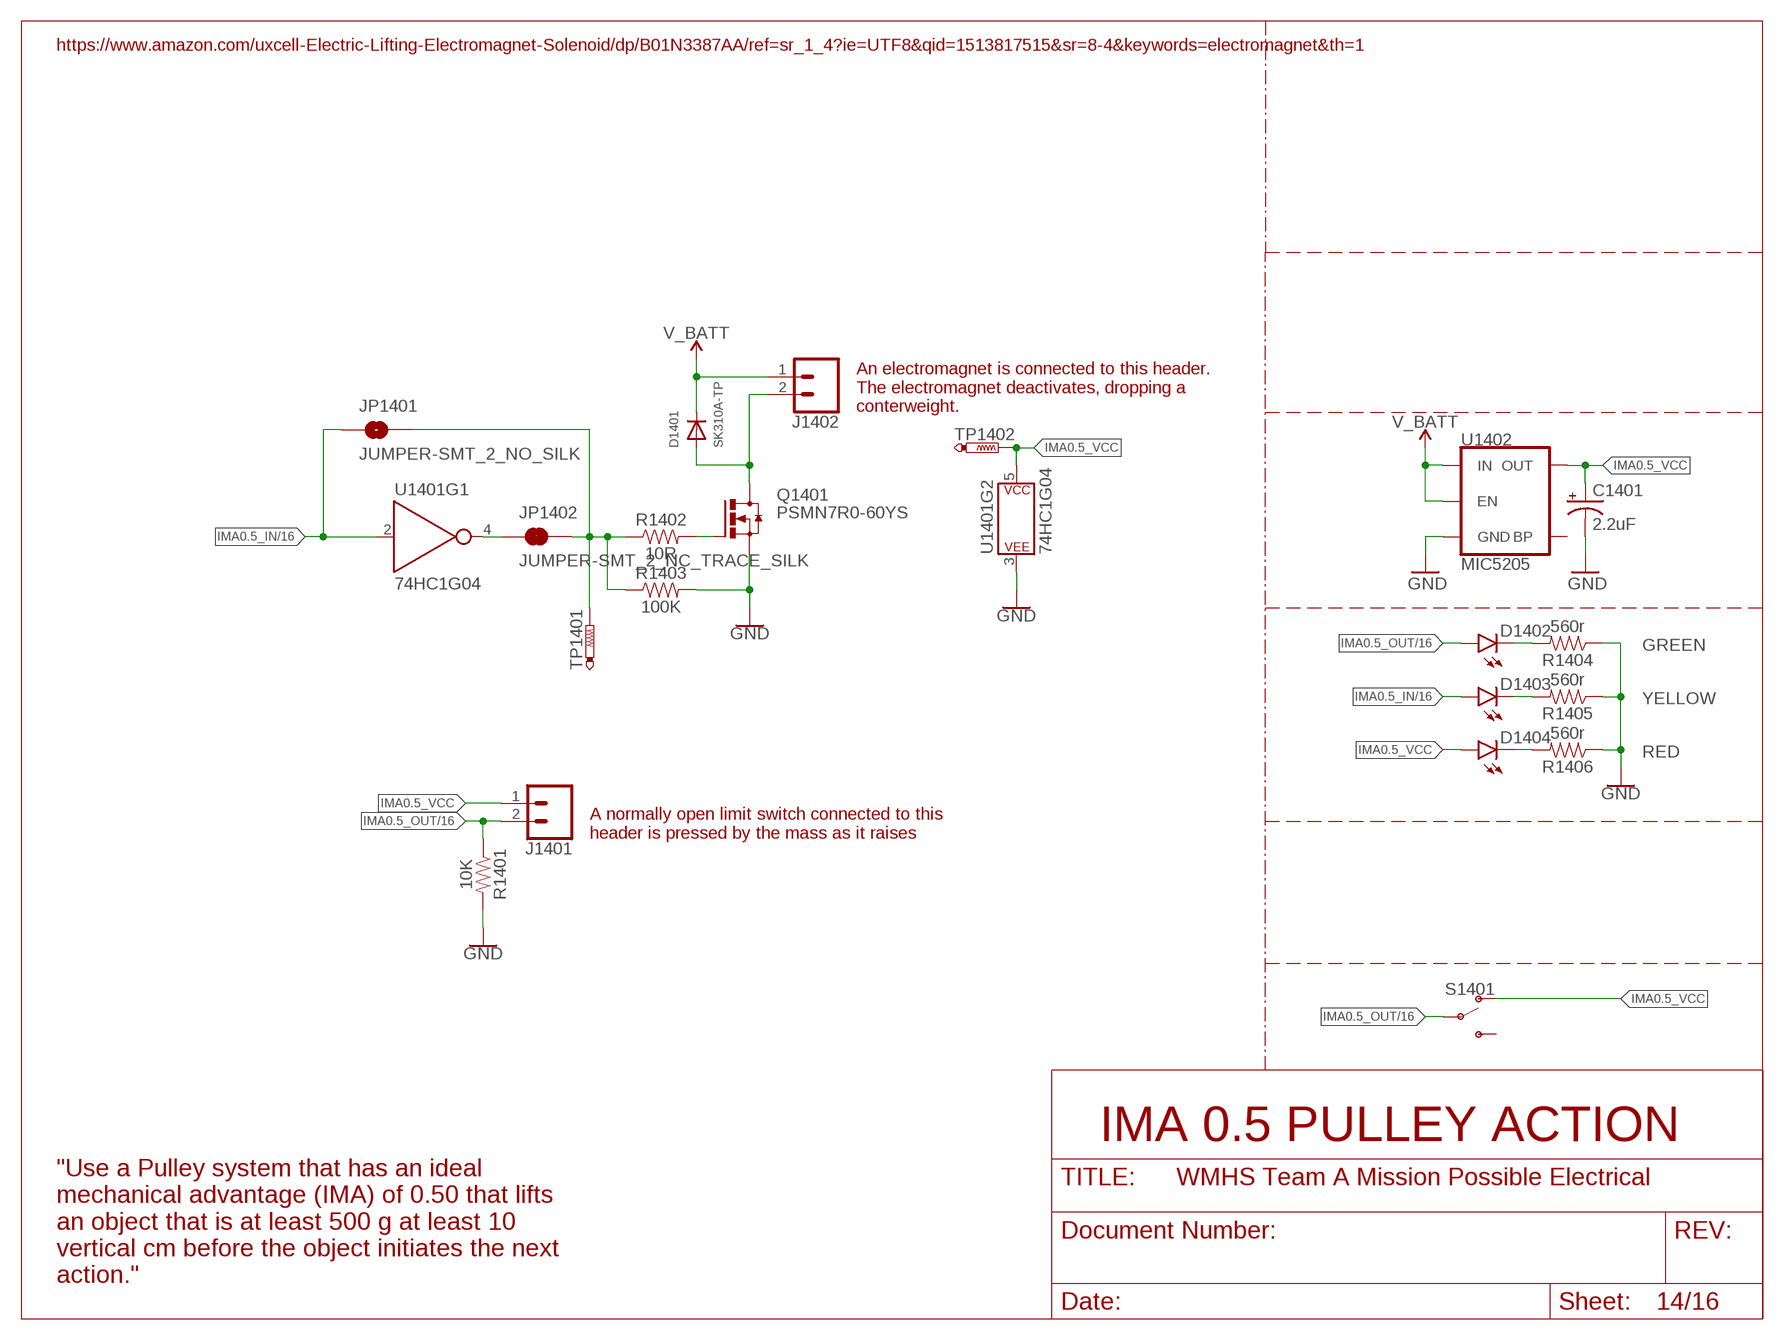
[diagram p13: schematic, sheet 14]
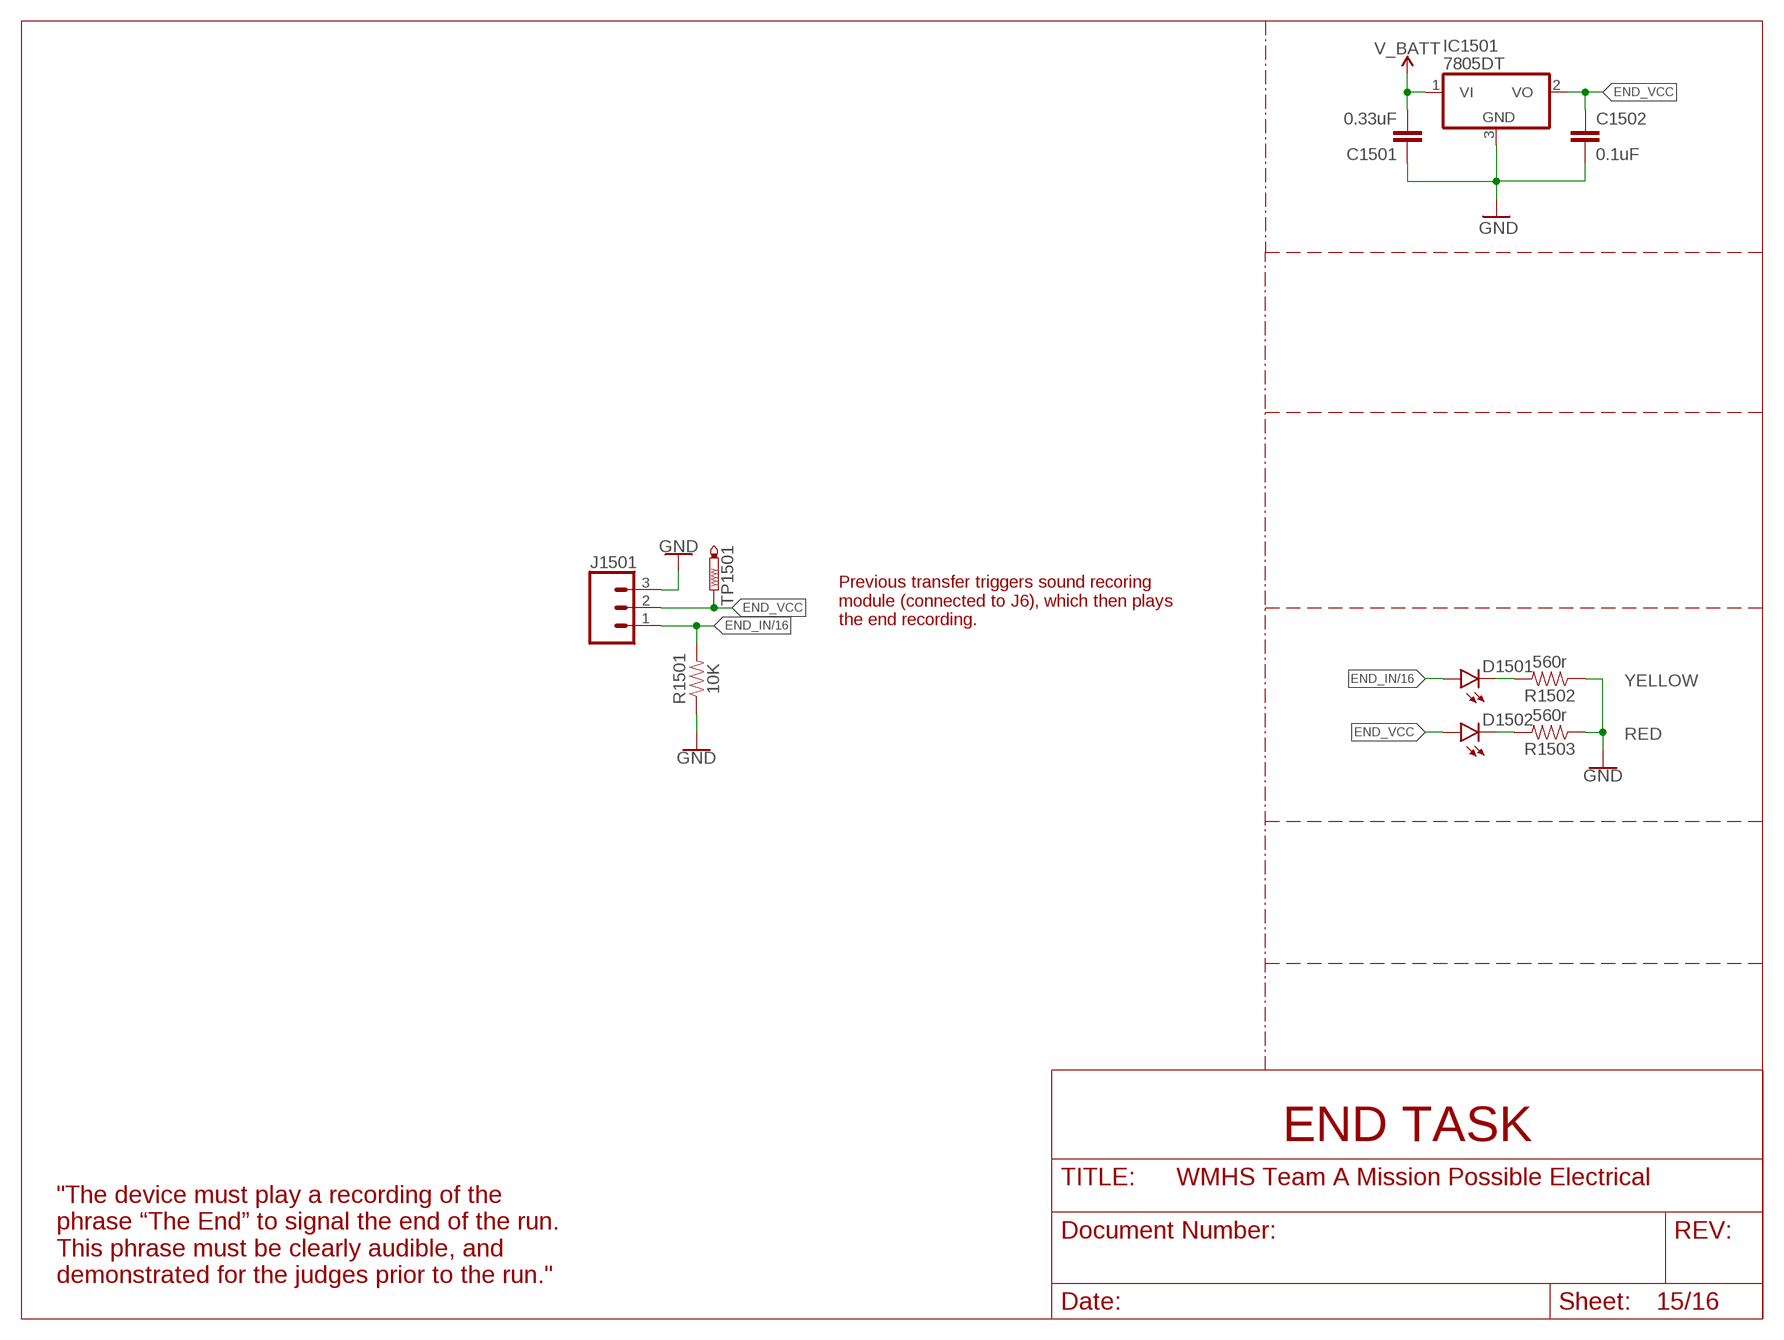
[diagram p14: schematic, sheet 15]
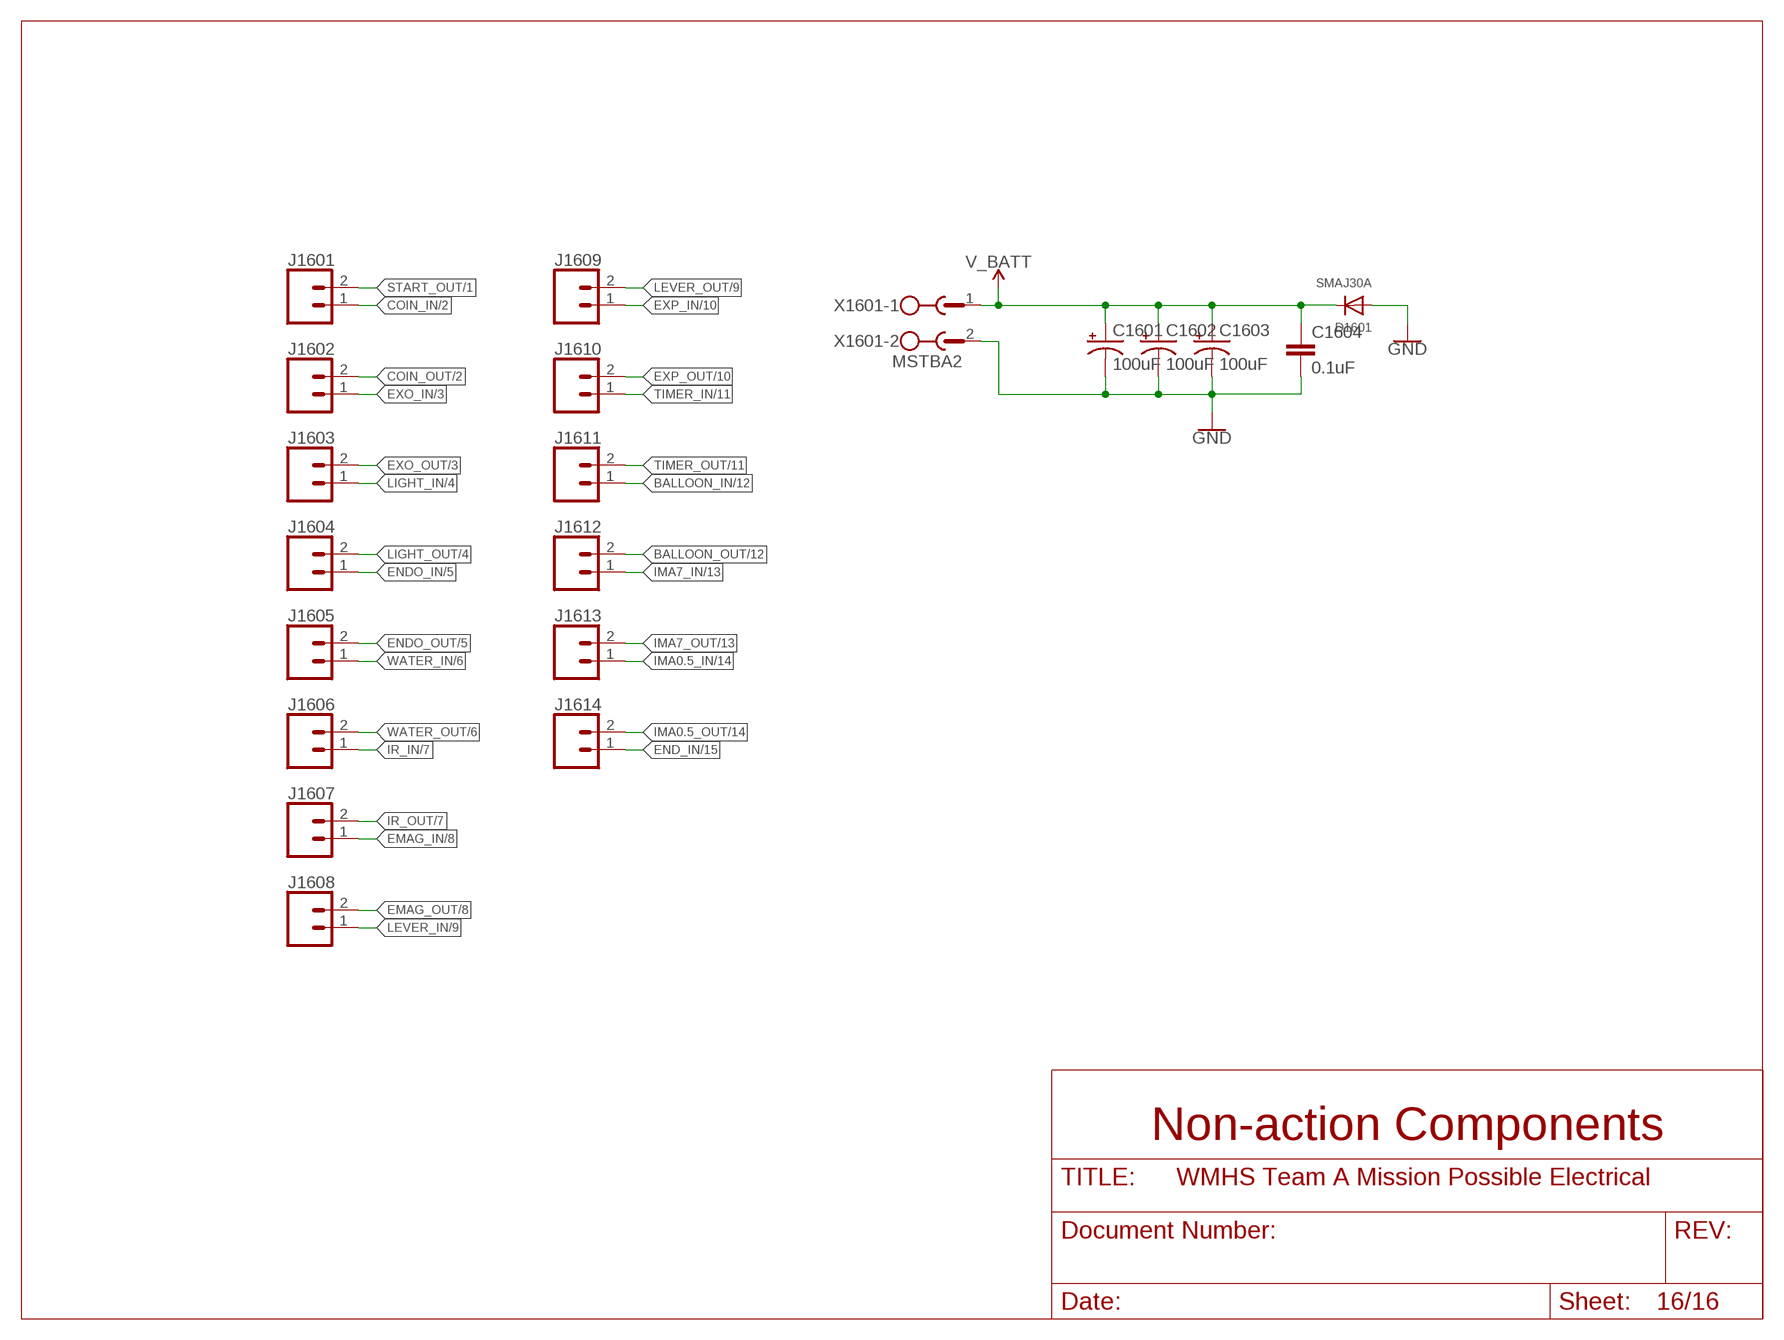
[diagram p15: schematic, sheet 16]

(export (version "E")
  (design (tool "Eeschema 10.0.6"))
  (components
    (comp (ref "C1201")
      (value "0.1uF")
      (footprint "eagle-import:0603")
      (libsource (lib "eagle-import") (part "0.1UF-0603-25V-5%"))
    )
    (comp (ref "C1202")
      (value "0.33uF")
      (footprint "eagle-import:0603")
      (libsource (lib "eagle-import") (part "0.1UF-0603-25V-(+80/-20%)"))
    )
    (comp (ref "C1203")
      (value "0.1uF")
      (footprint "eagle-import:0603")
      (libsource (lib "eagle-import") (part "0.1UF-0603-25V-(+80/-20%)"))
    )
    (comp (ref "D1201")
      (value "GREEN")
      (footprint "eagle-import:LED-0603")
      (libsource (lib "eagle-import") (part "LED-GREEN0603"))
    )
    (comp (ref "D1202")
      (value "YELLOW")
      (footprint "eagle-import:LED-0603")
      (libsource (lib "eagle-import") (part "LED-YELLOW0603"))
    )
    (comp (ref "D1203")
      (value "RED")
      (footprint "eagle-import:LED-0603")
      (libsource (lib "eagle-import") (part "LED-RED0603"))
    )
    (comp (ref "IC1201")
      (value "7805DT")
      (footprint "eagle-import:TO252")
      (libsource (lib "eagle-import") (part "78DT05"))
    )
    (comp (ref "J1201")
      (value "CONN_02LOCK")
      (footprint "eagle-import:1X02_LOCK")
      (libsource (lib "eagle-import") (part "CONN_02LOCK"))
    )
    (comp (ref "J1202")
      (value "CONN_02LOCK")
      (footprint "eagle-import:1X02_LOCK")
      (libsource (lib "eagle-import") (part "CONN_02LOCK"))
    )
    (comp (ref "J1203")
      (value "CONN_02LOCK")
      (footprint "eagle-import:1X02_LOCK")
      (libsource (lib "eagle-import") (part "CONN_02LOCK"))
    )
    (comp (ref "J1204")
      (value "ICSP_HEADER")
      (footprint "eagle-import:2X3")
      (libsource (lib "eagle-import") (part "AVR_SPI_PROG_3X2PTH"))
    )
    (comp (ref "R1201")
      (value "10K")
      (footprint "eagle-import:0603")
      (libsource (lib "eagle-import") (part "RESISTOR0603"))
    )
    (comp (ref "R1202")
      (value "10K")
      (footprint "eagle-import:0603")
      (libsource (lib "eagle-import") (part "RESISTOR0603"))
    )
    (comp (ref "R1203")
      (value "10K")
      (footprint "eagle-import:0603")
      (libsource (lib "eagle-import") (part "330OHM-0603-1/10W-1%"))
    )
    (comp (ref "R1204")
      (value "560r")
      (footprint "eagle-import:0603")
      (libsource (lib "eagle-import") (part "330OHM-0603-1/10W-1%"))
    )
    (comp (ref "R1205")
      (value "560r")
      (footprint "eagle-import:0603")
      (libsource (lib "eagle-import") (part "330OHM-0603-1/10W-1%"))
    )
    (comp (ref "R1206")
      (value "560r")
      (footprint "eagle-import:0603")
      (libsource (lib "eagle-import") (part "330OHM-0603-1/10W-1%"))
    )
    (comp (ref "S1201")
      (value "RST")
      (footprint "eagle-import:TACTILE_SWITCH_SMD_5.2MM")
      (libsource (lib "eagle-import") (part "MOMENTARY-SWITCH-SPST-SMD-5.2-REDUNDANT"))
    )
    (comp (ref "S1202")
      (value "SWITCH-SPDT-SMD-AYZ0202")
      (footprint "eagle-import:SWITCH_DPDT_SMD_AYZ0202")
      (libsource (lib "eagle-import") (part "SWITCH-SPDT-SMD-AYZ0202"))
    )
    (comp (ref "TP1201")
      (value "PTR1TP20R")
      (footprint "eagle-import:TP20R")
      (libsource (lib "eagle-import") (part "PTR1TP20R"))
    )
    (comp (ref "TP1202")
      (value "PTR1TP20R")
      (footprint "eagle-import:TP20R")
      (libsource (lib "eagle-import") (part "PTR1TP20R"))
    )
    (comp (ref "U1201")
      (value "DRV8835")
      (footprint "eagle-import:WSON-12")
      (libsource (lib "eagle-import") (part "DRV883X"))
    )
    (comp (ref "U1202")
      (value "ATTINY25-20SSUR")
      (footprint "eagle-import:SOIC8")
      (libsource (lib "eagle-import") (part "ATTINY45-SMT-NARROW"))
    )
    (comp (ref "C701")
      (value "0.1uF")
      (footprint "eagle-import:0603")
      (libsource (lib "eagle-import") (part "0.1UF-0603-25V-5%"))
    )
    (comp (ref "C702")
      (value "0.1uF")
      (footprint "eagle-import:0603")
      (libsource (lib "eagle-import") (part "0.1UF-0603-25V-5%"))
    )
    (comp (ref "C703")
      (value "2.2uF")
      (footprint "eagle-import:EIA3216")
      (libsource (lib "eagle-import") (part "10UF-POLAR-EIA3216-16V-10%(TANT)"))
    )
    (comp (ref "D701")
      (value "GREEN")
      (footprint "eagle-import:LED-0603")
      (libsource (lib "eagle-import") (part "LED-GREEN0603"))
    )
    (comp (ref "D702")
      (value "YELLOW")
      (footprint "eagle-import:LED-0603")
      (libsource (lib "eagle-import") (part "LED-YELLOW0603"))
    )
    (comp (ref "D703")
      (value "RED")
      (footprint "eagle-import:LED-0603")
      (libsource (lib "eagle-import") (part "LED-RED0603"))
    )
    (comp (ref "J701")
      (value "CONN_03")
      (footprint "eagle-import:1X03")
      (libsource (lib "eagle-import") (part "CONN_03"))
    )
    (comp (ref "J702")
      (value "CONN_02LOCK")
      (footprint "eagle-import:1X02_LOCK")
      (libsource (lib "eagle-import") (part "CONN_02LOCK"))
    )
    (comp (ref "J703")
      (value "ICSP_HEADER")
      (footprint "eagle-import:2X3")
      (libsource (lib "eagle-import") (part "AVR_SPI_PROG_3X2PTH"))
    )
    (comp (ref "J704")
      (value "ICSP_HEADER")
      (footprint "eagle-import:2X3")
      (libsource (lib "eagle-import") (part "AVR_SPI_PROG_3X2PTH"))
    )
    (comp (ref "R701")
      (value "330r")
      (footprint "eagle-import:0603")
      (libsource (lib "eagle-import") (part "RESISTOR0603"))
    )
    (comp (ref "R702")
      (value "33k")
      (footprint "eagle-import:0603")
      (libsource (lib "eagle-import") (part "RESISTOR0603"))
    )
    (comp (ref "R703")
      (value "10K")
      (footprint "eagle-import:0603")
      (libsource (lib "eagle-import") (part "330OHM-0603-1/10W-1%"))
    )
    (comp (ref "R704")
      (value "10K")
      (footprint "eagle-import:0603")
      (libsource (lib "eagle-import") (part "330OHM-0603-1/10W-1%"))
    )
    (comp (ref "R705")
      (value "560r")
      (footprint "eagle-import:0603")
      (libsource (lib "eagle-import") (part "330OHM-0603-1/10W-1%"))
    )
    (comp (ref "R706")
      (value "560r")
      (footprint "eagle-import:0603")
      (libsource (lib "eagle-import") (part "330OHM-0603-1/10W-1%"))
    )
    (comp (ref "R707")
      (value "560r")
      (footprint "eagle-import:0603")
      (libsource (lib "eagle-import") (part "330OHM-0603-1/10W-1%"))
    )
    (comp (ref "S701")
      (value "RST")
      (footprint "eagle-import:TACTILE_SWITCH_SMD_5.2MM")
      (libsource (lib "eagle-import") (part "MOMENTARY-SWITCH-SPST-SMD-5.2-REDUNDANT"))
    )
    (comp (ref "S702")
      (value "RST")
      (footprint "eagle-import:TACTILE_SWITCH_SMD_5.2MM")
      (libsource (lib "eagle-import") (part "MOMENTARY-SWITCH-SPST-SMD-5.2-REDUNDANT"))
    )
    (comp (ref "S703")
      (value "SWITCH-SPDT-SMD-AYZ0202")
      (footprint "eagle-import:SWITCH_DPDT_SMD_AYZ0202")
      (libsource (lib "eagle-import") (part "SWITCH-SPDT-SMD-AYZ0202"))
    )
    (comp (ref "TP701")
      (value "PTR1TP20R")
      (footprint "eagle-import:TP20R")
      (libsource (lib "eagle-import") (part "PTR1TP20R"))
    )
    (comp (ref "TP702")
      (value "PTR1TP20R")
      (footprint "eagle-import:TP20R")
      (libsource (lib "eagle-import") (part "PTR1TP20R"))
    )
    (comp (ref "TP703")
      (value "PTR1TP20R")
      (footprint "eagle-import:TP20R")
      (libsource (lib "eagle-import") (part "PTR1TP20R"))
    )
    (comp (ref "U701")
      (value "ATTINY25-20SSUR")
      (footprint "eagle-import:SOIC8")
      (libsource (lib "eagle-import") (part "ATTINY45-SMT-NARROW"))
    )
    (comp (ref "U702")
      (value "ATTINY25-20SSUR")
      (footprint "eagle-import:SOIC8")
      (libsource (lib "eagle-import") (part "ATTINY45-SMT-NARROW"))
    )
    (comp (ref "U703")
      (value "MIC5205")
      (footprint "eagle-import:SOT23-5")
      (libsource (lib "eagle-import") (part "V_REG_MIC52055V"))
    )
    (comp (ref "C401")
      (value "0.1uF")
      (footprint "eagle-import:0603")
      (libsource (lib "eagle-import") (part "0.1UF-0603-25V-5%"))
    )
    (comp (ref "C402")
      (value "2.2uF")
      (footprint "eagle-import:EIA3216")
      (libsource (lib "eagle-import") (part "10UF-POLAR-EIA3216-16V-10%(TANT)"))
    )
    (comp (ref "D401")
      (value "WHITE")
      (footprint "eagle-import:LED_3MM")
      (libsource (lib "eagle-import") (part "LED3MM"))
    )
    (comp (ref "D402")
      (value "GREEN")
      (footprint "eagle-import:LED-0603")
      (libsource (lib "eagle-import") (part "LED-GREEN0603"))
    )
    (comp (ref "D403")
      (value "YELLOW")
      (footprint "eagle-import:LED-0603")
      (libsource (lib "eagle-import") (part "LED-YELLOW0603"))
    )
    (comp (ref "D404")
      (value "RED")
      (footprint "eagle-import:LED-0603")
      (libsource (lib "eagle-import") (part "LED-RED0603"))
    )
    (comp (ref "J401")
      (value "ICSP_HEADER")
      (footprint "eagle-import:2X3")
      (libsource (lib "eagle-import") (part "AVR_SPI_PROG_3X2PTH"))
    )
    (comp (ref "Q401")
      (value "500mA/300V")
      (footprint "eagle-import:SOT23-3")
      (libsource (lib "eagle-import") (part "TRANS_NPN-MMBTA42"))
    )
    (comp (ref "R401")
      (value "10K")
      (footprint "eagle-import:0603")
      (libsource (lib "eagle-import") (part "RESISTOR0603"))
    )
    (comp (ref "R402")
      (value "PHOTOCELLPTH")
      (footprint "eagle-import:PHOTOCELL")
      (libsource (lib "eagle-import") (part "PHOTOCELLPTH"))
    )
    (comp (ref "R403")
      (value "1K")
      (footprint "eagle-import:0603")
      (libsource (lib "eagle-import") (part "RESISTOR0603"))
    )
    (comp (ref "R404")
      (value "560")
      (footprint "eagle-import:0603")
      (libsource (lib "eagle-import") (part "RESISTOR0603"))
    )
    (comp (ref "R405")
      (value "10K")
      (footprint "eagle-import:0603")
      (libsource (lib "eagle-import") (part "330OHM-0603-1/10W-1%"))
    )
    (comp (ref "R406")
      (value "560r")
      (footprint "eagle-import:0603")
      (libsource (lib "eagle-import") (part "330OHM-0603-1/10W-1%"))
    )
    (comp (ref "R407")
      (value "560r")
      (footprint "eagle-import:0603")
      (libsource (lib "eagle-import") (part "330OHM-0603-1/10W-1%"))
    )
    (comp (ref "R408")
      (value "560r")
      (footprint "eagle-import:0603")
      (libsource (lib "eagle-import") (part "330OHM-0603-1/10W-1%"))
    )
    (comp (ref "S401")
      (value "RST")
      (footprint "eagle-import:TACTILE_SWITCH_SMD_5.2MM")
      (libsource (lib "eagle-import") (part "MOMENTARY-SWITCH-SPST-SMD-5.2-REDUNDANT"))
    )
    (comp (ref "S402")
      (value "SWITCH-SPDT-SMD-AYZ0202")
      (footprint "eagle-import:SWITCH_DPDT_SMD_AYZ0202")
      (libsource (lib "eagle-import") (part "SWITCH-SPDT-SMD-AYZ0202"))
    )
    (comp (ref "TP401")
      (value "PTR1TP20R")
      (footprint "eagle-import:TP20R")
      (libsource (lib "eagle-import") (part "PTR1TP20R"))
    )
    (comp (ref "TP402")
      (value "PTR1TP20R")
      (footprint "eagle-import:TP20R")
      (libsource (lib "eagle-import") (part "PTR1TP20R"))
    )
    (comp (ref "TP403")
      (value "PTR1TP20R")
      (footprint "eagle-import:TP20R")
      (libsource (lib "eagle-import") (part "PTR1TP20R"))
    )
    (comp (ref "TP404")
      (value "PTR1TP20R")
      (footprint "eagle-import:TP20R")
      (libsource (lib "eagle-import") (part "PTR1TP20R"))
    )
    (comp (ref "U401")
      (value "74HC1G04")
      (footprint "eagle-import:SOT353")
      (libsource (lib "eagle-import") (part "741G04HC"))
    )
    (comp (ref "U402")
      (value "SN74C1G08-DCK")
      (footprint "eagle-import:SC-70-5")
      (libsource (lib "eagle-import") (part "SN74C1G08-DCK"))
    )
    (comp (ref "U403")
      (value "ATTINY25-20SSUR")
      (footprint "eagle-import:SOIC8")
      (libsource (lib "eagle-import") (part "ATTINY45-SMT-NARROW"))
    )
    (comp (ref "U404")
      (value "MIC5205")
      (footprint "eagle-import:SOT23-5")
      (libsource (lib "eagle-import") (part "V_REG_MIC52055V"))
    )
    (comp (ref "C201")
      (value "0.1uF")
      (footprint "eagle-import:0603")
      (libsource (lib "eagle-import") (part "0.1UF-0603-25V-5%"))
    )
    (comp (ref "C202")
      (value "2.2uF")
      (footprint "eagle-import:EIA3216")
      (libsource (lib "eagle-import") (part "10UF-POLAR-EIA3216-16V-10%(TANT)"))
    )
    (comp (ref "D201")
      (value "SK310A-TP")
      (footprint "eagle-import:SMADIODE")
      (libsource (lib "eagle-import") (part "DIODESMA"))
    )
    (comp (ref "D202")
      (value "GREEN")
      (footprint "eagle-import:LED-0603")
      (libsource (lib "eagle-import") (part "LED-GREEN0603"))
    )
    (comp (ref "D203")
      (value "YELLOW")
      (footprint "eagle-import:LED-0603")
      (libsource (lib "eagle-import") (part "LED-YELLOW0603"))
    )
    (comp (ref "D204")
      (value "RED")
      (footprint "eagle-import:LED-0603")
      (libsource (lib "eagle-import") (part "LED-RED0603"))
    )
    (comp (ref "J201")
      (value "CONN_03LOCK")
      (footprint "eagle-import:1X03_LOCK")
      (libsource (lib "eagle-import") (part "CONN_03LOCK"))
    )
    (comp (ref "J202")
      (value "CONN_02LOCK")
      (footprint "eagle-import:1X02_LOCK")
      (libsource (lib "eagle-import") (part "CONN_02LOCK"))
    )
    (comp (ref "J203")
      (value "CONN_023.5MM_LOCK")
      (footprint "eagle-import:SCREWTERMINAL-3.5MM-2_LOCK")
      (libsource (lib "eagle-import") (part "CONN_023.5MM_LOCK"))
    )
    (comp (ref "J204")
      (value "ICSP_HEADER")
      (footprint "eagle-import:2X3")
      (libsource (lib "eagle-import") (part "AVR_SPI_PROG_3X2PTH"))
    )
    (comp (ref "JP201")
      (value "JUMPER-SMT_2_NO_SILK")
      (footprint "eagle-import:SMT-JUMPER_2_NO_SILK")
      (libsource (lib "eagle-import") (part "JUMPER-SMT_2_NO_SILK"))
    )
    (comp (ref "JP202")
      (value "JUMPER-SMT_2_NC_TRACE_SILK")
      (footprint "eagle-import:SMT-JUMPER_2_NC_TRACE_SILK")
      (libsource (lib "eagle-import") (part "JUMPER-SMT_2_NC_TRACE_SILK"))
    )
    (comp (ref "Q201")
      (value "PSMN7R0-60YS")
      (footprint "eagle-import:SOT669")
      (libsource (lib "eagle-import") (part "PSMN7R0-60YS"))
    )
    (comp (ref "R201")
      (value "10R")
      (footprint "eagle-import:0603")
      (libsource (lib "eagle-import") (part "RESISTOR0603"))
    )
    (comp (ref "R202")
      (value "100K")
      (footprint "eagle-import:0603")
      (libsource (lib "eagle-import") (part "RESISTOR0603"))
    )
    (comp (ref "R203")
      (value "10k")
      (footprint "eagle-import:0603")
      (libsource (lib "eagle-import") (part "RESISTOR0603"))
    )
    (comp (ref "R204")
      (value "10K")
      (footprint "eagle-import:0603")
      (libsource (lib "eagle-import") (part "330OHM-0603-1/10W-1%"))
    )
    (comp (ref "R205")
      (value "560r")
      (footprint "eagle-import:0603")
      (libsource (lib "eagle-import") (part "330OHM-0603-1/10W-1%"))
    )
    (comp (ref "R206")
      (value "560r")
      (footprint "eagle-import:0603")
      (libsource (lib "eagle-import") (part "330OHM-0603-1/10W-1%"))
    )
    (comp (ref "R207")
      (value "560r")
      (footprint "eagle-import:0603")
      (libsource (lib "eagle-import") (part "330OHM-0603-1/10W-1%"))
    )
    (comp (ref "S201")
      (value "RST")
      (footprint "eagle-import:TACTILE_SWITCH_SMD_5.2MM")
      (libsource (lib "eagle-import") (part "MOMENTARY-SWITCH-SPST-SMD-5.2-REDUNDANT"))
    )
    (comp (ref "S202")
      (value "SWITCH-SPDT-SMD-AYZ0202")
      (footprint "eagle-import:SWITCH_DPDT_SMD_AYZ0202")
      (libsource (lib "eagle-import") (part "SWITCH-SPDT-SMD-AYZ0202"))
    )
    (comp (ref "TP201")
      (value "PTR1TP20R")
      (footprint "eagle-import:TP20R")
      (libsource (lib "eagle-import") (part "PTR1TP20R"))
    )
    (comp (ref "TP202")
      (value "PTR1TP20R")
      (footprint "eagle-import:TP20R")
      (libsource (lib "eagle-import") (part "PTR1TP20R"))
    )
    (comp (ref "TP203")
      (value "PTR1TP20R")
      (footprint "eagle-import:TP20R")
      (libsource (lib "eagle-import") (part "PTR1TP20R"))
    )
    (comp (ref "U201")
      (value "74HC1G04")
      (footprint "eagle-import:SOT353")
      (libsource (lib "eagle-import") (part "741G04HC"))
    )
    (comp (ref "U202")
      (value "ATTINY25-20SSUR")
      (footprint "eagle-import:SOIC8")
      (libsource (lib "eagle-import") (part "ATTINY45-SMT-NARROW"))
    )
    (comp (ref "U203")
      (value "MIC5205")
      (footprint "eagle-import:SOT23-5")
      (libsource (lib "eagle-import") (part "V_REG_MIC52055V"))
    )
    (comp (ref "C101")
      (value "2.2uF")
      (footprint "eagle-import:EIA3216")
      (libsource (lib "eagle-import") (part "10UF-POLAR-EIA3216-16V-10%(TANT)"))
    )
    (comp (ref "D101")
      (value "GREEN")
      (footprint "eagle-import:LED-0603")
      (libsource (lib "eagle-import") (part "LED-GREEN0603"))
    )
    (comp (ref "D102")
      (value "RED")
      (footprint "eagle-import:LED-0603")
      (libsource (lib "eagle-import") (part "LED-RED0603"))
    )
    (comp (ref "JP101")
      (value "JUMPER_NC_TRACE")
      (footprint "eagle-import:SMT-JUMPER_2_NC_TRACE_SILK")
      (libsource (lib "eagle-import") (part "JUMPER-SMT_2_NC_TRACE_SILK"))
    )
    (comp (ref "JP102")
      (value "JUMPER-SMT_2_NO_SILK")
      (footprint "eagle-import:SMT-JUMPER_2_NO_SILK")
      (libsource (lib "eagle-import") (part "JUMPER-SMT_2_NO_SILK"))
    )
    (comp (ref "R101")
      (value "10K")
      (footprint "eagle-import:0603")
      (libsource (lib "eagle-import") (part "330OHM-0603-1/10W-1%"))
    )
    (comp (ref "R102")
      (value "560r")
      (footprint "eagle-import:0603")
      (libsource (lib "eagle-import") (part "330OHM-0603-1/10W-1%"))
    )
    (comp (ref "R103")
      (value "560r")
      (footprint "eagle-import:0603")
      (libsource (lib "eagle-import") (part "330OHM-0603-1/10W-1%"))
    )
    (comp (ref "S101")
      (value "REED_SWITCH")
      (footprint "eagle-import:AXIAL_GULLWING_REED")
      (libsource (lib "eagle-import") (part "MDSM-10_REED_SWITCH"))
    )
    (comp (ref "S102")
      (value "SWITCH-SPDT-SMD-AYZ0202")
      (footprint "eagle-import:SWITCH_DPDT_SMD_AYZ0202")
      (libsource (lib "eagle-import") (part "SWITCH-SPDT-SMD-AYZ0202"))
    )
    (comp (ref "TP101")
      (value "PTR1TP20R")
      (footprint "eagle-import:TP20R")
      (libsource (lib "eagle-import") (part "PTR1TP20R"))
    )
    (comp (ref "U101")
      (value "74HC1G04")
      (footprint "eagle-import:SOT353")
      (libsource (lib "eagle-import") (part "741G04HC"))
    )
    (comp (ref "U102")
      (value "MIC5205")
      (footprint "eagle-import:SOT23-5")
      (libsource (lib "eagle-import") (part "V_REG_MIC52055V"))
    )
    (comp (ref "C1301")
      (value "0.1uF")
      (footprint "eagle-import:0603")
      (libsource (lib "eagle-import") (part "0.1UF-0603-25V-5%"))
    )
    (comp (ref "C1302")
      (value "0.33uF")
      (footprint "eagle-import:0603")
      (libsource (lib "eagle-import") (part "0.1UF-0603-25V-(+80/-20%)"))
    )
    (comp (ref "C1303")
      (value "0.1uF")
      (footprint "eagle-import:0603")
      (libsource (lib "eagle-import") (part "0.1UF-0603-25V-(+80/-20%)"))
    )
    (comp (ref "D1301")
      (value "GREEN")
      (footprint "eagle-import:LED-0603")
      (libsource (lib "eagle-import") (part "LED-GREEN0603"))
    )
    (comp (ref "D1302")
      (value "YELLOW")
      (footprint "eagle-import:LED-0603")
      (libsource (lib "eagle-import") (part "LED-YELLOW0603"))
    )
    (comp (ref "D1303")
      (value "RED")
      (footprint "eagle-import:LED-0603")
      (libsource (lib "eagle-import") (part "LED-RED0603"))
    )
    (comp (ref "IC1301")
      (value "7805DT")
      (footprint "eagle-import:TO252")
      (libsource (lib "eagle-import") (part "78DT05"))
    )
    (comp (ref "J1301")
      (value "CONN_02LOCK")
      (footprint "eagle-import:1X02_LOCK")
      (libsource (lib "eagle-import") (part "CONN_02LOCK"))
    )
    (comp (ref "J1302")
      (value "CONN_02LOCK")
      (footprint "eagle-import:1X02_LOCK")
      (libsource (lib "eagle-import") (part "CONN_02LOCK"))
    )
    (comp (ref "J1303")
      (value "CONN_02LOCK")
      (footprint "eagle-import:1X02_LOCK")
      (libsource (lib "eagle-import") (part "CONN_02LOCK"))
    )
    (comp (ref "J1304")
      (value "ICSP_HEADER")
      (footprint "eagle-import:2X3")
      (libsource (lib "eagle-import") (part "AVR_SPI_PROG_3X2PTH"))
    )
    (comp (ref "R1301")
      (value "10K")
      (footprint "eagle-import:0603")
      (libsource (lib "eagle-import") (part "RESISTOR0603"))
    )
    (comp (ref "R1302")
      (value "10K")
      (footprint "eagle-import:0603")
      (libsource (lib "eagle-import") (part "RESISTOR0603"))
    )
    (comp (ref "R1303")
      (value "10K")
      (footprint "eagle-import:0603")
      (libsource (lib "eagle-import") (part "330OHM-0603-1/10W-1%"))
    )
    (comp (ref "R1304")
      (value "560r")
      (footprint "eagle-import:0603")
      (libsource (lib "eagle-import") (part "330OHM-0603-1/10W-1%"))
    )
    (comp (ref "R1305")
      (value "560r")
      (footprint "eagle-import:0603")
      (libsource (lib "eagle-import") (part "330OHM-0603-1/10W-1%"))
    )
    (comp (ref "R1306")
      (value "560r")
      (footprint "eagle-import:0603")
      (libsource (lib "eagle-import") (part "330OHM-0603-1/10W-1%"))
    )
    (comp (ref "S1301")
      (value "RST")
      (footprint "eagle-import:TACTILE_SWITCH_SMD_5.2MM")
      (libsource (lib "eagle-import") (part "MOMENTARY-SWITCH-SPST-SMD-5.2-REDUNDANT"))
    )
    (comp (ref "S1302")
      (value "SWITCH-SPDT-SMD-AYZ0202")
      (footprint "eagle-import:SWITCH_DPDT_SMD_AYZ0202")
      (libsource (lib "eagle-import") (part "SWITCH-SPDT-SMD-AYZ0202"))
    )
    (comp (ref "TP1301")
      (value "PTR1TP20R")
      (footprint "eagle-import:TP20R")
      (libsource (lib "eagle-import") (part "PTR1TP20R"))
    )
    (comp (ref "TP1302")
      (value "PTR1TP20R")
      (footprint "eagle-import:TP20R")
      (libsource (lib "eagle-import") (part "PTR1TP20R"))
    )
    (comp (ref "U1301")
      (value "DRV8835")
      (footprint "eagle-import:WSON-12")
      (libsource (lib "eagle-import") (part "DRV883X"))
    )
    (comp (ref "U1302")
      (value "ATTINY25-20SSUR")
      (footprint "eagle-import:SOIC8")
      (libsource (lib "eagle-import") (part "ATTINY45-SMT-NARROW"))
    )
    (comp (ref "C801")
      (value "2.2uF")
      (footprint "eagle-import:EIA3216")
      (libsource (lib "eagle-import") (part "10UF-POLAR-EIA3216-16V-10%(TANT)"))
    )
    (comp (ref "D801")
      (value "SK310A-TP")
      (footprint "eagle-import:SMADIODE")
      (libsource (lib "eagle-import") (part "DIODESMA"))
    )
    (comp (ref "D802")
      (value "GREEN")
      (footprint "eagle-import:LED-0603")
      (libsource (lib "eagle-import") (part "LED-GREEN0603"))
    )
    (comp (ref "D803")
      (value "YELLOW")
      (footprint "eagle-import:LED-0603")
      (libsource (lib "eagle-import") (part "LED-YELLOW0603"))
    )
    (comp (ref "D804")
      (value "RED")
      (footprint "eagle-import:LED-0603")
      (libsource (lib "eagle-import") (part "LED-RED0603"))
    )
    (comp (ref "J801")
      (value "CONN_02LOCK")
      (footprint "eagle-import:1X02_LOCK")
      (libsource (lib "eagle-import") (part "CONN_02LOCK"))
    )
    (comp (ref "J802")
      (value "CONN_023.5MM_LOCK")
      (footprint "eagle-import:SCREWTERMINAL-3.5MM-2_LOCK")
      (libsource (lib "eagle-import") (part "CONN_023.5MM_LOCK"))
    )
    (comp (ref "Q801")
      (value "PSMN7R0-60YS")
      (footprint "eagle-import:SOT669")
      (libsource (lib "eagle-import") (part "PSMN7R0-60YS"))
    )
    (comp (ref "R801")
      (value "10K")
      (footprint "eagle-import:0603")
      (libsource (lib "eagle-import") (part "RESISTOR0603"))
    )
    (comp (ref "R802")
      (value "10R")
      (footprint "eagle-import:0603")
      (libsource (lib "eagle-import") (part "RESISTOR0603"))
    )
    (comp (ref "R803")
      (value "100K")
      (footprint "eagle-import:0603")
      (libsource (lib "eagle-import") (part "RESISTOR0603"))
    )
    (comp (ref "R804")
      (value "560r")
      (footprint "eagle-import:0603")
      (libsource (lib "eagle-import") (part "330OHM-0603-1/10W-1%"))
    )
    (comp (ref "R805")
      (value "560r")
      (footprint "eagle-import:0603")
      (libsource (lib "eagle-import") (part "330OHM-0603-1/10W-1%"))
    )
    (comp (ref "R806")
      (value "560r")
      (footprint "eagle-import:0603")
      (libsource (lib "eagle-import") (part "330OHM-0603-1/10W-1%"))
    )
    (comp (ref "S801")
      (value "SWITCH-SPDT-SMD-AYZ0202")
      (footprint "eagle-import:SWITCH_DPDT_SMD_AYZ0202")
      (libsource (lib "eagle-import") (part "SWITCH-SPDT-SMD-AYZ0202"))
    )
    (comp (ref "TP801")
      (value "PTR1TP20R")
      (footprint "eagle-import:TP20R")
      (libsource (lib "eagle-import") (part "PTR1TP20R"))
    )
    (comp (ref "TP802")
      (value "PTR1TP20R")
      (footprint "eagle-import:TP20R")
      (libsource (lib "eagle-import") (part "PTR1TP20R"))
    )
    (comp (ref "TP803")
      (value "PTR1TP20R")
      (footprint "eagle-import:TP20R")
      (libsource (lib "eagle-import") (part "PTR1TP20R"))
    )
    (comp (ref "U801")
      (value "74HC1G04")
      (footprint "eagle-import:SOT353")
      (libsource (lib "eagle-import") (part "741G04HC"))
    )
    (comp (ref "U802")
      (value "SN74C1G08-DCK")
      (footprint "eagle-import:SC-70-5")
      (libsource (lib "eagle-import") (part "SN74C1G08-DCK"))
    )
    (comp (ref "U803")
      (value "MIC5205")
      (footprint "eagle-import:SOT23-5")
      (libsource (lib "eagle-import") (part "V_REG_MIC52055V"))
    )
    (comp (ref "C601")
      (value "0.1uF")
      (footprint "eagle-import:0603")
      (libsource (lib "eagle-import") (part "0.1UF-0603-25V-5%"))
    )
    (comp (ref "C602")
      (value "2.2uF")
      (footprint "eagle-import:EIA3216")
      (libsource (lib "eagle-import") (part "10UF-POLAR-EIA3216-16V-10%(TANT)"))
    )
    (comp (ref "D601")
      (value "SK310A-TP")
      (footprint "eagle-import:SMADIODE")
      (libsource (lib "eagle-import") (part "DIODESMA"))
    )
    (comp (ref "D602")
      (value "GREEN")
      (footprint "eagle-import:LED-0603")
      (libsource (lib "eagle-import") (part "LED-GREEN0603"))
    )
    (comp (ref "D603")
      (value "YELLOW")
      (footprint "eagle-import:LED-0603")
      (libsource (lib "eagle-import") (part "LED-YELLOW0603"))
    )
    (comp (ref "D604")
      (value "RED")
      (footprint "eagle-import:LED-0603")
      (libsource (lib "eagle-import") (part "LED-RED0603"))
    )
    (comp (ref "J601")
      (value "CONN_02LOCK")
      (footprint "eagle-import:1X02_LOCK")
      (libsource (lib "eagle-import") (part "CONN_02LOCK"))
    )
    (comp (ref "J602")
      (value "CONN_023.5MM_LOCK")
      (footprint "eagle-import:SCREWTERMINAL-3.5MM-2_LOCK")
      (libsource (lib "eagle-import") (part "CONN_023.5MM_LOCK"))
    )
    (comp (ref "J603")
      (value "ICSP_HEADER")
      (footprint "eagle-import:2X3")
      (libsource (lib "eagle-import") (part "AVR_SPI_PROG_3X2PTH"))
    )
    (comp (ref "Q601")
      (value "PSMN7R0-60YS")
      (footprint "eagle-import:SOT669")
      (libsource (lib "eagle-import") (part "PSMN7R0-60YS"))
    )
    (comp (ref "R601")
      (value "10R")
      (footprint "eagle-import:0603")
      (libsource (lib "eagle-import") (part "RESISTOR0603"))
    )
    (comp (ref "R602")
      (value "100K")
      (footprint "eagle-import:0603")
      (libsource (lib "eagle-import") (part "RESISTOR0603"))
    )
    (comp (ref "R603")
      (value "1M")
      (footprint "eagle-import:0603")
      (libsource (lib "eagle-import") (part "RESISTOR0603"))
    )
    (comp (ref "R604")
      (value "10K")
      (footprint "eagle-import:0603")
      (libsource (lib "eagle-import") (part "330OHM-0603-1/10W-1%"))
    )
    (comp (ref "R605")
      (value "560r")
      (footprint "eagle-import:0603")
      (libsource (lib "eagle-import") (part "330OHM-0603-1/10W-1%"))
    )
    (comp (ref "R606")
      (value "560r")
      (footprint "eagle-import:0603")
      (libsource (lib "eagle-import") (part "330OHM-0603-1/10W-1%"))
    )
    (comp (ref "R607")
      (value "560r")
      (footprint "eagle-import:0603")
      (libsource (lib "eagle-import") (part "330OHM-0603-1/10W-1%"))
    )
    (comp (ref "S601")
      (value "RST")
      (footprint "eagle-import:TACTILE_SWITCH_SMD_5.2MM")
      (libsource (lib "eagle-import") (part "MOMENTARY-SWITCH-SPST-SMD-5.2-REDUNDANT"))
    )
    (comp (ref "S602")
      (value "SWITCH-SPDT-SMD-AYZ0202")
      (footprint "eagle-import:SWITCH_DPDT_SMD_AYZ0202")
      (libsource (lib "eagle-import") (part "SWITCH-SPDT-SMD-AYZ0202"))
    )
    (comp (ref "TP601")
      (value "PTR1TP20R")
      (footprint "eagle-import:TP20R")
      (libsource (lib "eagle-import") (part "PTR1TP20R"))
    )
    (comp (ref "TP602")
      (value "PTR1TP20R")
      (footprint "eagle-import:TP20R")
      (libsource (lib "eagle-import") (part "PTR1TP20R"))
    )
    (comp (ref "TP603")
      (value "PTR1TP20R")
      (footprint "eagle-import:TP20R")
      (libsource (lib "eagle-import") (part "PTR1TP20R"))
    )
    (comp (ref "TP604")
      (value "PTR1TP20R")
      (footprint "eagle-import:TP20R")
      (libsource (lib "eagle-import") (part "PTR1TP20R"))
    )
    (comp (ref "U601")
      (value "74HC1G04")
      (footprint "eagle-import:SOT353")
      (libsource (lib "eagle-import") (part "741G04HC"))
    )
    (comp (ref "U602")
      (value "SN74C1G08-DCK")
      (footprint "eagle-import:SC-70-5")
      (libsource (lib "eagle-import") (part "SN74C1G08-DCK"))
    )
    (comp (ref "U603")
      (value "ATTINY25-20SSUR")
      (footprint "eagle-import:SOIC8")
      (libsource (lib "eagle-import") (part "ATTINY45-SMT-NARROW"))
    )
    (comp (ref "U604")
      (value "MIC5205")
      (footprint "eagle-import:SOT23-5")
      (libsource (lib "eagle-import") (part "V_REG_MIC52055V"))
    )
    (comp (ref "C1601")
      (value "100uF")
      (footprint "eagle-import:PANASONIC_D")
      (libsource (lib "eagle-import") (part "100UF-POLAR-25V-20%(ELEC)"))
    )
    (comp (ref "C1602")
      (value "100uF")
      (footprint "eagle-import:PANASONIC_D")
      (libsource (lib "eagle-import") (part "100UF-POLAR-25V-20%(ELEC)"))
    )
    (comp (ref "C1603")
      (value "100uF")
      (footprint "eagle-import:PANASONIC_D")
      (libsource (lib "eagle-import") (part "100UF-POLAR-25V-20%(ELEC)"))
    )
    (comp (ref "C1604")
      (value "0.1uF")
      (footprint "eagle-import:0603")
      (libsource (lib "eagle-import") (part "0.1UF-0603-25V-5%"))
    )
    (comp (ref "D1601")
      (value "SMAJ30A")
      (footprint "eagle-import:SMADIODE")
      (libsource (lib "eagle-import") (part "DIODESMA"))
    )
    (comp (ref "J1601")
      (value "CONN_02")
      (footprint "eagle-import:1X02")
      (libsource (lib "eagle-import") (part "CONN_02"))
    )
    (comp (ref "J1602")
      (value "CONN_02")
      (footprint "eagle-import:1X02")
      (libsource (lib "eagle-import") (part "CONN_02"))
    )
    (comp (ref "J1603")
      (value "CONN_02")
      (footprint "eagle-import:1X02")
      (libsource (lib "eagle-import") (part "CONN_02"))
    )
    (comp (ref "J1604")
      (value "CONN_02")
      (footprint "eagle-import:1X02")
      (libsource (lib "eagle-import") (part "CONN_02"))
    )
    (comp (ref "J1605")
      (value "CONN_02")
      (footprint "eagle-import:1X02")
      (libsource (lib "eagle-import") (part "CONN_02"))
    )
    (comp (ref "J1606")
      (value "CONN_02")
      (footprint "eagle-import:1X02")
      (libsource (lib "eagle-import") (part "CONN_02"))
    )
    (comp (ref "J1607")
      (value "CONN_02")
      (footprint "eagle-import:1X02")
      (libsource (lib "eagle-import") (part "CONN_02"))
    )
    (comp (ref "J1608")
      (value "CONN_02")
      (footprint "eagle-import:1X02")
      (libsource (lib "eagle-import") (part "CONN_02"))
    )
    (comp (ref "J1609")
      (value "CONN_02")
      (footprint "eagle-import:1X02")
      (libsource (lib "eagle-import") (part "CONN_02"))
    )
    (comp (ref "J1610")
      (value "CONN_02")
      (footprint "eagle-import:1X02")
      (libsource (lib "eagle-import") (part "CONN_02"))
    )
    (comp (ref "J1611")
      (value "CONN_02")
      (footprint "eagle-import:1X02")
      (libsource (lib "eagle-import") (part "CONN_02"))
    )
    (comp (ref "J1612")
      (value "CONN_02")
      (footprint "eagle-import:1X02")
      (libsource (lib "eagle-import") (part "CONN_02"))
    )
    (comp (ref "J1613")
      (value "CONN_02")
      (footprint "eagle-import:1X02")
      (libsource (lib "eagle-import") (part "CONN_02"))
    )
    (comp (ref "J1614")
      (value "CONN_02")
      (footprint "eagle-import:1X02")
      (libsource (lib "eagle-import") (part "CONN_02"))
    )
    (comp (ref "X1601")
      (value "MSTBA2")
      (footprint "eagle-import:MSTBA2")
      (fields (field (name "MF") "FARNELL") (field (name "MPN") "1757242"))
      (libsource (lib "eagle-import") (part "MSTBA2"))
    )
    (comp (ref "C1001")
      (value "0.1uF")
      (footprint "eagle-import:0603")
      (libsource (lib "eagle-import") (part "0.1UF-0603-25V-5%"))
    )
    (comp (ref "C1002")
      (value "2.2uF")
      (footprint "eagle-import:EIA3216")
      (libsource (lib "eagle-import") (part "10UF-POLAR-EIA3216-16V-10%(TANT)"))
    )
    (comp (ref "D1001")
      (value "SK310A-TP")
      (footprint "eagle-import:SMADIODE")
      (libsource (lib "eagle-import") (part "DIODESMA"))
    )
    (comp (ref "D1002")
      (value "GREEN")
      (footprint "eagle-import:LED-0603")
      (libsource (lib "eagle-import") (part "LED-GREEN0603"))
    )
    (comp (ref "D1003")
      (value "YELLOW")
      (footprint "eagle-import:LED-0603")
      (libsource (lib "eagle-import") (part "LED-YELLOW0603"))
    )
    (comp (ref "D1004")
      (value "RED")
      (footprint "eagle-import:LED-0603")
      (libsource (lib "eagle-import") (part "LED-RED0603"))
    )
    (comp (ref "J1001")
      (value "CONN_023.5MM_LOCK")
      (footprint "eagle-import:SCREWTERMINAL-3.5MM-2_LOCK")
      (libsource (lib "eagle-import") (part "CONN_023.5MM_LOCK"))
    )
    (comp (ref "J1002")
      (value "CONN_02LOCK")
      (footprint "eagle-import:1X02_LOCK")
      (libsource (lib "eagle-import") (part "CONN_02LOCK"))
    )
    (comp (ref "J1003")
      (value "CONN_02LOCK")
      (footprint "eagle-import:1X02_LOCK")
      (libsource (lib "eagle-import") (part "CONN_02LOCK"))
    )
    (comp (ref "J1004")
      (value "CONN_02LOCK")
      (footprint "eagle-import:1X02_LOCK")
      (libsource (lib "eagle-import") (part "CONN_02LOCK"))
    )
    (comp (ref "J1005")
      (value "ICSP_HEADER")
      (footprint "eagle-import:2X3")
      (libsource (lib "eagle-import") (part "AVR_SPI_PROG_3X2PTH"))
    )
    (comp (ref "Q1001")
      (value "PSMN7R0-60YS")
      (footprint "eagle-import:SOT669")
      (libsource (lib "eagle-import") (part "PSMN7R0-60YS"))
    )
    (comp (ref "R1001")
      (value "10R")
      (footprint "eagle-import:0603")
      (libsource (lib "eagle-import") (part "RESISTOR0603"))
    )
    (comp (ref "R1002")
      (value "100K")
      (footprint "eagle-import:0603")
      (libsource (lib "eagle-import") (part "RESISTOR0603"))
    )
    (comp (ref "R1003")
      (value "100K")
      (footprint "eagle-import:0603")
      (libsource (lib "eagle-import") (part "RESISTOR0603"))
    )
    (comp (ref "R1004")
      (value "1M")
      (footprint "eagle-import:0603")
      (libsource (lib "eagle-import") (part "RESISTOR0603"))
    )
    (comp (ref "R1005")
      (value "10K")
      (footprint "eagle-import:0603")
      (libsource (lib "eagle-import") (part "330OHM-0603-1/10W-1%"))
    )
    (comp (ref "R1006")
      (value "560r")
      (footprint "eagle-import:0603")
      (libsource (lib "eagle-import") (part "330OHM-0603-1/10W-1%"))
    )
    (comp (ref "R1007")
      (value "560r")
      (footprint "eagle-import:0603")
      (libsource (lib "eagle-import") (part "330OHM-0603-1/10W-1%"))
    )
    (comp (ref "R1008")
      (value "560r")
      (footprint "eagle-import:0603")
      (libsource (lib "eagle-import") (part "330OHM-0603-1/10W-1%"))
    )
    (comp (ref "S1001")
      (value "RST")
      (footprint "eagle-import:TACTILE_SWITCH_SMD_5.2MM")
      (libsource (lib "eagle-import") (part "MOMENTARY-SWITCH-SPST-SMD-5.2-REDUNDANT"))
    )
    (comp (ref "S1002")
      (value "SWITCH-SPDT-SMD-AYZ0202")
      (footprint "eagle-import:SWITCH_DPDT_SMD_AYZ0202")
      (libsource (lib "eagle-import") (part "SWITCH-SPDT-SMD-AYZ0202"))
    )
    (comp (ref "TP1001")
      (value "PTR1TP20R")
      (footprint "eagle-import:TP20R")
      (libsource (lib "eagle-import") (part "PTR1TP20R"))
    )
    (comp (ref "TP1002")
      (value "PTR1TP20R")
      (footprint "eagle-import:TP20R")
      (libsource (lib "eagle-import") (part "PTR1TP20R"))
    )
    (comp (ref "U1001")
      (value "ATTINY25-20SSUR")
      (footprint "eagle-import:SOIC8")
      (libsource (lib "eagle-import") (part "ATTINY45-SMT-NARROW"))
    )
    (comp (ref "U1002")
      (value "MIC5205")
      (footprint "eagle-import:SOT23-5")
      (libsource (lib "eagle-import") (part "V_REG_MIC52055V"))
    )
    (comp (ref "C301")
      (value "0.1uF")
      (footprint "eagle-import:0603")
      (libsource (lib "eagle-import") (part "0.1UF-0603-25V-5%"))
    )
    (comp (ref "C302")
      (value "2.2uF")
      (footprint "eagle-import:EIA3216")
      (libsource (lib "eagle-import") (part "10UF-POLAR-EIA3216-16V-10%(TANT)"))
    )
    (comp (ref "D301")
      (value "INCANDESCENT")
      (footprint "eagle-import:LED_3MM")
      (libsource (lib "eagle-import") (part "LED3MM"))
    )
    (comp (ref "D302")
      (value "GREEN")
      (footprint "eagle-import:LED-0603")
      (libsource (lib "eagle-import") (part "LED-GREEN0603"))
    )
    (comp (ref "D303")
      (value "YELLOW")
      (footprint "eagle-import:LED-0603")
      (libsource (lib "eagle-import") (part "LED-YELLOW0603"))
    )
    (comp (ref "D304")
      (value "RED")
      (footprint "eagle-import:LED-0603")
      (libsource (lib "eagle-import") (part "LED-RED0603"))
    )
    (comp (ref "J301")
      (value "ICSP_HEADER")
      (footprint "eagle-import:2X3")
      (libsource (lib "eagle-import") (part "AVR_SPI_PROG_3X2PTH"))
    )
    (comp (ref "Q301")
      (value "500mA/300V")
      (footprint "eagle-import:SOT23-3")
      (libsource (lib "eagle-import") (part "TRANS_NPN-MMBTA42"))
    )
    (comp (ref "R301")
      (value "10K")
      (footprint "eagle-import:0603")
      (libsource (lib "eagle-import") (part "RESISTOR0603"))
    )
    (comp (ref "R302")
      (value "1K")
      (footprint "eagle-import:0603")
      (libsource (lib "eagle-import") (part "RESISTOR0603"))
    )
    (comp (ref "R303")
      (value "PHOTOCELLPTH")
      (footprint "eagle-import:PHOTOCELL")
      (libsource (lib "eagle-import") (part "PHOTOCELLPTH"))
    )
    (comp (ref "R304")
      (value "10K")
      (footprint "eagle-import:0603")
      (libsource (lib "eagle-import") (part "330OHM-0603-1/10W-1%"))
    )
    (comp (ref "R305")
      (value "560r")
      (footprint "eagle-import:0603")
      (libsource (lib "eagle-import") (part "330OHM-0603-1/10W-1%"))
    )
    (comp (ref "R306")
      (value "560r")
      (footprint "eagle-import:0603")
      (libsource (lib "eagle-import") (part "330OHM-0603-1/10W-1%"))
    )
    (comp (ref "R307")
      (value "560r")
      (footprint "eagle-import:0603")
      (libsource (lib "eagle-import") (part "330OHM-0603-1/10W-1%"))
    )
    (comp (ref "S301")
      (value "RST")
      (footprint "eagle-import:TACTILE_SWITCH_SMD_5.2MM")
      (libsource (lib "eagle-import") (part "MOMENTARY-SWITCH-SPST-SMD-5.2-REDUNDANT"))
    )
    (comp (ref "S302")
      (value "SWITCH-SPDT-SMD-AYZ0202")
      (footprint "eagle-import:SWITCH_DPDT_SMD_AYZ0202")
      (libsource (lib "eagle-import") (part "SWITCH-SPDT-SMD-AYZ0202"))
    )
    (comp (ref "TP301")
      (value "PTR1TP20R")
      (footprint "eagle-import:TP20R")
      (libsource (lib "eagle-import") (part "PTR1TP20R"))
    )
    (comp (ref "TP302")
      (value "PTR1TP20R")
      (footprint "eagle-import:TP20R")
      (libsource (lib "eagle-import") (part "PTR1TP20R"))
    )
    (comp (ref "TP303")
      (value "PTR1TP20R")
      (footprint "eagle-import:TP20R")
      (libsource (lib "eagle-import") (part "PTR1TP20R"))
    )
    (comp (ref "U301")
      (value "74HC1G04")
      (footprint "eagle-import:SOT353")
      (libsource (lib "eagle-import") (part "741G04HC"))
    )
    (comp (ref "U302")
      (value "SN74C1G08-DCK")
      (footprint "eagle-import:SC-70-5")
      (libsource (lib "eagle-import") (part "SN74C1G08-DCK"))
    )
    (comp (ref "U303")
      (value "ATTINY25-20SSUR")
      (footprint "eagle-import:SOIC8")
      (libsource (lib "eagle-import") (part "ATTINY45-SMT-NARROW"))
    )
    (comp (ref "U304")
      (value "MIC5205")
      (footprint "eagle-import:SOT23-5")
      (libsource (lib "eagle-import") (part "V_REG_MIC52055V"))
    )
    (comp (ref "C1501")
      (value "0.33uF")
      (footprint "eagle-import:0603")
      (libsource (lib "eagle-import") (part "0.1UF-0603-25V-(+80/-20%)"))
    )
    (comp (ref "C1502")
      (value "0.1uF")
      (footprint "eagle-import:0603")
      (libsource (lib "eagle-import") (part "0.1UF-0603-25V-(+80/-20%)"))
    )
    (comp (ref "D1501")
      (value "YELLOW")
      (footprint "eagle-import:LED-0603")
      (libsource (lib "eagle-import") (part "LED-YELLOW0603"))
    )
    (comp (ref "D1502")
      (value "RED")
      (footprint "eagle-import:LED-0603")
      (libsource (lib "eagle-import") (part "LED-RED0603"))
    )
    (comp (ref "IC1501")
      (value "7805DT")
      (footprint "eagle-import:TO252")
      (libsource (lib "eagle-import") (part "78DT05"))
    )
    (comp (ref "J1501")
      (value "CONN_03LOCK")
      (footprint "eagle-import:1X03_LOCK")
      (libsource (lib "eagle-import") (part "CONN_03LOCK"))
    )
    (comp (ref "R1501")
      (value "10K")
      (footprint "eagle-import:0603")
      (libsource (lib "eagle-import") (part "RESISTOR0603"))
    )
    (comp (ref "R1502")
      (value "560r")
      (footprint "eagle-import:0603")
      (libsource (lib "eagle-import") (part "330OHM-0603-1/10W-1%"))
    )
    (comp (ref "R1503")
      (value "560r")
      (footprint "eagle-import:0603")
      (libsource (lib "eagle-import") (part "330OHM-0603-1/10W-1%"))
    )
    (comp (ref "TP1501")
      (value "PTR1TP20R")
      (footprint "eagle-import:TP20R")
      (libsource (lib "eagle-import") (part "PTR1TP20R"))
    )
    (comp (ref "C1401")
      (value "2.2uF")
      (footprint "eagle-import:EIA3216")
      (libsource (lib "eagle-import") (part "10UF-POLAR-EIA3216-16V-10%(TANT)"))
    )
    (comp (ref "D1401")
      (value "SK310A-TP")
      (footprint "eagle-import:SMADIODE")
      (libsource (lib "eagle-import") (part "DIODESMA"))
    )
    (comp (ref "D1402")
      (value "GREEN")
      (footprint "eagle-import:LED-0603")
      (libsource (lib "eagle-import") (part "LED-GREEN0603"))
    )
    (comp (ref "D1403")
      (value "YELLOW")
      (footprint "eagle-import:LED-0603")
      (libsource (lib "eagle-import") (part "LED-YELLOW0603"))
    )
    (comp (ref "D1404")
      (value "RED")
      (footprint "eagle-import:LED-0603")
      (libsource (lib "eagle-import") (part "LED-RED0603"))
    )
    (comp (ref "J1401")
      (value "CONN_02LOCK")
      (footprint "eagle-import:1X02_LOCK")
      (libsource (lib "eagle-import") (part "CONN_02LOCK"))
    )
    (comp (ref "J1402")
      (value "CONN_023.5MM_LOCK")
      (footprint "eagle-import:SCREWTERMINAL-3.5MM-2_LOCK")
      (libsource (lib "eagle-import") (part "CONN_023.5MM_LOCK"))
    )
    (comp (ref "JP1401")
      (value "JUMPER-SMT_2_NO_SILK")
      (footprint "eagle-import:SMT-JUMPER_2_NO_SILK")
      (libsource (lib "eagle-import") (part "JUMPER-SMT_2_NO_SILK"))
    )
    (comp (ref "JP1402")
      (value "JUMPER-SMT_2_NC_TRACE_SILK")
      (footprint "eagle-import:SMT-JUMPER_2_NC_TRACE_SILK")
      (libsource (lib "eagle-import") (part "JUMPER-SMT_2_NC_TRACE_SILK"))
    )
    (comp (ref "Q1401")
      (value "PSMN7R0-60YS")
      (footprint "eagle-import:SOT669")
      (libsource (lib "eagle-import") (part "PSMN7R0-60YS"))
    )
    (comp (ref "R1401")
      (value "10K")
      (footprint "eagle-import:0603")
      (libsource (lib "eagle-import") (part "RESISTOR0603"))
    )
    (comp (ref "R1402")
      (value "10R")
      (footprint "eagle-import:0603")
      (libsource (lib "eagle-import") (part "RESISTOR0603"))
    )
    (comp (ref "R1403")
      (value "100K")
      (footprint "eagle-import:0603")
      (libsource (lib "eagle-import") (part "RESISTOR0603"))
    )
    (comp (ref "R1404")
      (value "560r")
      (footprint "eagle-import:0603")
      (libsource (lib "eagle-import") (part "330OHM-0603-1/10W-1%"))
    )
    (comp (ref "R1405")
      (value "560r")
      (footprint "eagle-import:0603")
      (libsource (lib "eagle-import") (part "330OHM-0603-1/10W-1%"))
    )
    (comp (ref "R1406")
      (value "560r")
      (footprint "eagle-import:0603")
      (libsource (lib "eagle-import") (part "330OHM-0603-1/10W-1%"))
    )
    (comp (ref "S1401")
      (value "SWITCH-SPDT-SMD-AYZ0202")
      (footprint "eagle-import:SWITCH_DPDT_SMD_AYZ0202")
      (libsource (lib "eagle-import") (part "SWITCH-SPDT-SMD-AYZ0202"))
    )
    (comp (ref "TP1401")
      (value "PTR1TP20R")
      (footprint "eagle-import:TP20R")
      (libsource (lib "eagle-import") (part "PTR1TP20R"))
    )
    (comp (ref "TP1402")
      (value "PTR1TP20R")
      (footprint "eagle-import:TP20R")
      (libsource (lib "eagle-import") (part "PTR1TP20R"))
    )
    (comp (ref "U1401")
      (value "74HC1G04")
      (footprint "eagle-import:SOT353")
      (libsource (lib "eagle-import") (part "741G04HC"))
    )
    (comp (ref "U1402")
      (value "MIC5205")
      (footprint "eagle-import:SOT23-5")
      (libsource (lib "eagle-import") (part "V_REG_MIC52055V"))
    )
    (comp (ref "C901")
      (value "0.1uF")
      (footprint "eagle-import:0603")
      (libsource (lib "eagle-import") (part "0.1UF-0603-25V-5%"))
    )
    (comp (ref "C902")
      (value "2.2uF")
      (footprint "eagle-import:EIA3216")
      (libsource (lib "eagle-import") (part "10UF-POLAR-EIA3216-16V-10%(TANT)"))
    )
    (comp (ref "D901")
      (value "SK310A-TP")
      (footprint "eagle-import:SMADIODE")
      (libsource (lib "eagle-import") (part "DIODESMA"))
    )
    (comp (ref "D902")
      (value "GREEN")
      (footprint "eagle-import:LED-0603")
      (libsource (lib "eagle-import") (part "LED-GREEN0603"))
    )
    (comp (ref "D903")
      (value "YELLOW")
      (footprint "eagle-import:LED-0603")
      (libsource (lib "eagle-import") (part "LED-YELLOW0603"))
    )
    (comp (ref "D904")
      (value "RED")
      (footprint "eagle-import:LED-0603")
      (libsource (lib "eagle-import") (part "LED-RED0603"))
    )
    (comp (ref "J901")
      (value "CONN_02LOCK")
      (footprint "eagle-import:1X02_LOCK")
      (libsource (lib "eagle-import") (part "CONN_02LOCK"))
    )
    (comp (ref "J902")
      (value "CONN_023.5MM_LOCK")
      (footprint "eagle-import:SCREWTERMINAL-3.5MM-2_LOCK")
      (libsource (lib "eagle-import") (part "CONN_023.5MM_LOCK"))
    )
    (comp (ref "J903")
      (value "ICSP_HEADER")
      (footprint "eagle-import:2X3")
      (libsource (lib "eagle-import") (part "AVR_SPI_PROG_3X2PTH"))
    )
    (comp (ref "Q901")
      (value "PSMN7R0-60YS")
      (footprint "eagle-import:SOT669")
      (libsource (lib "eagle-import") (part "PSMN7R0-60YS"))
    )
    (comp (ref "R901")
      (value "10R")
      (footprint "eagle-import:0603")
      (libsource (lib "eagle-import") (part "RESISTOR0603"))
    )
    (comp (ref "R902")
      (value "100K")
      (footprint "eagle-import:0603")
      (libsource (lib "eagle-import") (part "RESISTOR0603"))
    )
    (comp (ref "R903")
      (value "10K")
      (footprint "eagle-import:0603")
      (libsource (lib "eagle-import") (part "RESISTOR0603"))
    )
    (comp (ref "R904")
      (value "10K")
      (footprint "eagle-import:0603")
      (libsource (lib "eagle-import") (part "330OHM-0603-1/10W-1%"))
    )
    (comp (ref "R905")
      (value "560r")
      (footprint "eagle-import:0603")
      (libsource (lib "eagle-import") (part "330OHM-0603-1/10W-1%"))
    )
    (comp (ref "R906")
      (value "560r")
      (footprint "eagle-import:0603")
      (libsource (lib "eagle-import") (part "330OHM-0603-1/10W-1%"))
    )
    (comp (ref "R907")
      (value "560r")
      (footprint "eagle-import:0603")
      (libsource (lib "eagle-import") (part "330OHM-0603-1/10W-1%"))
    )
    (comp (ref "S901")
      (value "RST")
      (footprint "eagle-import:TACTILE_SWITCH_SMD_5.2MM")
      (libsource (lib "eagle-import") (part "MOMENTARY-SWITCH-SPST-SMD-5.2-REDUNDANT"))
    )
    (comp (ref "S902")
      (value "SWITCH-SPDT-SMD-AYZ0202")
      (footprint "eagle-import:SWITCH_DPDT_SMD_AYZ0202")
      (libsource (lib "eagle-import") (part "SWITCH-SPDT-SMD-AYZ0202"))
    )
    (comp (ref "TP901")
      (value "PTR1TP20R")
      (footprint "eagle-import:TP20R")
      (libsource (lib "eagle-import") (part "PTR1TP20R"))
    )
    (comp (ref "TP902")
      (value "PTR1TP20R")
      (footprint "eagle-import:TP20R")
      (libsource (lib "eagle-import") (part "PTR1TP20R"))
    )
    (comp (ref "U901")
      (value "ATTINY25-20SSUR")
      (footprint "eagle-import:SOIC8")
      (libsource (lib "eagle-import") (part "ATTINY45-SMT-NARROW"))
    )
    (comp (ref "U902")
      (value "MIC5205")
      (footprint "eagle-import:SOT23-5")
      (libsource (lib "eagle-import") (part "V_REG_MIC52055V"))
    )
    (comp (ref "C1101")
      (value "0.1uF")
      (footprint "eagle-import:0603")
      (libsource (lib "eagle-import") (part "0.1UF-0603-25V-5%"))
    )
    (comp (ref "C1102")
      (value "0.33uF")
      (footprint "eagle-import:0603")
      (libsource (lib "eagle-import") (part "0.1UF-0603-25V-(+80/-20%)"))
    )
    (comp (ref "C1103")
      (value "0.1uF")
      (footprint "eagle-import:0603")
      (libsource (lib "eagle-import") (part "0.1UF-0603-100V-10%"))
    )
    (comp (ref "D1101")
      (value "GREEN")
      (footprint "eagle-import:LED-0603")
      (libsource (lib "eagle-import") (part "LED-GREEN0603"))
    )
    (comp (ref "D1102")
      (value "YELLOW")
      (footprint "eagle-import:LED-0603")
      (libsource (lib "eagle-import") (part "LED-YELLOW0603"))
    )
    (comp (ref "D1103")
      (value "RED")
      (footprint "eagle-import:LED-0603")
      (libsource (lib "eagle-import") (part "LED-RED0603"))
    )
    (comp (ref "IC1101")
      (value "7805DT")
      (footprint "eagle-import:TO252")
      (libsource (lib "eagle-import") (part "78DT05"))
    )
    (comp (ref "J1101")
      (value "CONN_02LOCK")
      (footprint "eagle-import:1X02_LOCK")
      (libsource (lib "eagle-import") (part "CONN_02LOCK"))
    )
    (comp (ref "J1102")
      (value "CONN_02LOCK")
      (footprint "eagle-import:1X02_LOCK")
      (libsource (lib "eagle-import") (part "CONN_02LOCK"))
    )
    (comp (ref "J1103")
      (value "CONN_02LOCK")
      (footprint "eagle-import:1X02_LOCK")
      (libsource (lib "eagle-import") (part "CONN_02LOCK"))
    )
    (comp (ref "J1104")
      (value "ICSP_HEADER")
      (footprint "eagle-import:2X3")
      (libsource (lib "eagle-import") (part "AVR_SPI_PROG_3X2PTH"))
    )
    (comp (ref "R1101")
      (value "10K")
      (footprint "eagle-import:0603")
      (libsource (lib "eagle-import") (part "RESISTOR0603"))
    )
    (comp (ref "R1102")
      (value "10K")
      (footprint "eagle-import:0603")
      (libsource (lib "eagle-import") (part "RESISTOR0603"))
    )
    (comp (ref "R1103")
      (value "10K")
      (footprint "eagle-import:0603")
      (libsource (lib "eagle-import") (part "330OHM-0603-1/10W-1%"))
    )
    (comp (ref "R1104")
      (value "560r")
      (footprint "eagle-import:0603")
      (libsource (lib "eagle-import") (part "330OHM-0603-1/10W-1%"))
    )
    (comp (ref "R1105")
      (value "560r")
      (footprint "eagle-import:0603")
      (libsource (lib "eagle-import") (part "330OHM-0603-1/10W-1%"))
    )
    (comp (ref "R1106")
      (value "560r")
      (footprint "eagle-import:0603")
      (libsource (lib "eagle-import") (part "330OHM-0603-1/10W-1%"))
    )
    (comp (ref "S1101")
      (value "RST")
      (footprint "eagle-import:TACTILE_SWITCH_SMD_5.2MM")
      (libsource (lib "eagle-import") (part "MOMENTARY-SWITCH-SPST-SMD-5.2-REDUNDANT"))
    )
    (comp (ref "S1102")
      (value "SWITCH-SPDT-SMD-AYZ0202")
      (footprint "eagle-import:SWITCH_DPDT_SMD_AYZ0202")
      (libsource (lib "eagle-import") (part "SWITCH-SPDT-SMD-AYZ0202"))
    )
    (comp (ref "TP1101")
      (value "PTR1TP20R")
      (footprint "eagle-import:TP20R")
      (libsource (lib "eagle-import") (part "PTR1TP20R"))
    )
    (comp (ref "TP1102")
      (value "PTR1TP20R")
      (footprint "eagle-import:TP20R")
      (libsource (lib "eagle-import") (part "PTR1TP20R"))
    )
    (comp (ref "U1101")
      (value "DRV8835")
      (footprint "eagle-import:WSON-12")
      (libsource (lib "eagle-import") (part "DRV883X"))
    )
    (comp (ref "U1102")
      (value "ATTINY25-20SSUR")
      (footprint "eagle-import:SOIC8")
      (libsource (lib "eagle-import") (part "ATTINY45-SMT-NARROW"))
    )
    (comp (ref "C501")
      (value "0.1uF")
      (footprint "eagle-import:0603")
      (libsource (lib "eagle-import") (part "0.1UF-0603-25V-5%"))
    )
    (comp (ref "C502")
      (value "2.2uF")
      (footprint "eagle-import:EIA3216")
      (libsource (lib "eagle-import") (part "10UF-POLAR-EIA3216-16V-10%(TANT)"))
    )
    (comp (ref "D501")
      (value "SK310A-TP")
      (footprint "eagle-import:SMADIODE")
      (libsource (lib "eagle-import") (part "DIODESMA"))
    )
    (comp (ref "D502")
      (value "GREEN")
      (footprint "eagle-import:LED-0603")
      (libsource (lib "eagle-import") (part "LED-GREEN0603"))
    )
    (comp (ref "D503")
      (value "YELLOW")
      (footprint "eagle-import:LED-0603")
      (libsource (lib "eagle-import") (part "LED-YELLOW0603"))
    )
    (comp (ref "D504")
      (value "RED")
      (footprint "eagle-import:LED-0603")
      (libsource (lib "eagle-import") (part "LED-RED0603"))
    )
    (comp (ref "J501")
      (value "CONN_02LOCK")
      (footprint "eagle-import:1X02_LOCK")
      (libsource (lib "eagle-import") (part "CONN_02LOCK"))
    )
    (comp (ref "J502")
      (value "CONN_023.5MM_LOCK")
      (footprint "eagle-import:SCREWTERMINAL-3.5MM-2_LOCK")
      (libsource (lib "eagle-import") (part "CONN_023.5MM_LOCK"))
    )
    (comp (ref "J503")
      (value "ICSP_HEADER")
      (footprint "eagle-import:2X3")
      (libsource (lib "eagle-import") (part "AVR_SPI_PROG_3X2PTH"))
    )
    (comp (ref "Q501")
      (value "PSMN7R0-60YS")
      (footprint "eagle-import:SOT669")
      (libsource (lib "eagle-import") (part "PSMN7R0-60YS"))
    )
    (comp (ref "R501")
      (value "0R")
      (footprint "eagle-import:0603")
      (libsource (lib "eagle-import") (part "RESISTOR0603"))
    )
    (comp (ref "R502")
      (value "10R")
      (footprint "eagle-import:0603")
      (libsource (lib "eagle-import") (part "RESISTOR0603"))
    )
    (comp (ref "R503")
      (value "100K")
      (footprint "eagle-import:0603")
      (libsource (lib "eagle-import") (part "RESISTOR0603"))
    )
    (comp (ref "R504")
      (value "10K")
      (footprint "eagle-import:0603")
      (libsource (lib "eagle-import") (part "330OHM-0603-1/10W-1%"))
    )
    (comp (ref "R505")
      (value "560r")
      (footprint "eagle-import:0603")
      (libsource (lib "eagle-import") (part "330OHM-0603-1/10W-1%"))
    )
    (comp (ref "R506")
      (value "560r")
      (footprint "eagle-import:0603")
      (libsource (lib "eagle-import") (part "330OHM-0603-1/10W-1%"))
    )
    (comp (ref "R507")
      (value "560r")
      (footprint "eagle-import:0603")
      (libsource (lib "eagle-import") (part "330OHM-0603-1/10W-1%"))
    )
    (comp (ref "S501")
      (value "RST")
      (footprint "eagle-import:TACTILE_SWITCH_SMD_5.2MM")
      (libsource (lib "eagle-import") (part "MOMENTARY-SWITCH-SPST-SMD-5.2-REDUNDANT"))
    )
    (comp (ref "S502")
      (value "SWITCH-SPDT-SMD-AYZ0202")
      (footprint "eagle-import:SWITCH_DPDT_SMD_AYZ0202")
      (libsource (lib "eagle-import") (part "SWITCH-SPDT-SMD-AYZ0202"))
    )
    (comp (ref "TP501")
      (value "PTR1TP20R")
      (footprint "eagle-import:TP20R")
      (libsource (lib "eagle-import") (part "PTR1TP20R"))
    )
    (comp (ref "TP502")
      (value "PTR1TP20R")
      (footprint "eagle-import:TP20R")
      (libsource (lib "eagle-import") (part "PTR1TP20R"))
    )
    (comp (ref "TP503")
      (value "PTR1TP20R")
      (footprint "eagle-import:TP20R")
      (libsource (lib "eagle-import") (part "PTR1TP20R"))
    )
    (comp (ref "TP504")
      (value "PTR1TP20R")
      (footprint "eagle-import:TP20R")
      (libsource (lib "eagle-import") (part "PTR1TP20R"))
    )
    (comp (ref "U501")
      (value "74HC1G04")
      (footprint "eagle-import:SOT353")
      (libsource (lib "eagle-import") (part "741G04HC"))
    )
    (comp (ref "U502")
      (value "SN74C1G08-DCK")
      (footprint "eagle-import:SC-70-5")
      (libsource (lib "eagle-import") (part "SN74C1G08-DCK"))
    )
    (comp (ref "U503")
      (value "ATTINY25-20SSUR")
      (footprint "eagle-import:SOIC8")
      (libsource (lib "eagle-import") (part "ATTINY45-SMT-NARROW"))
    )
    (comp (ref "U504")
      (value "MIC5205")
      (footprint "eagle-import:SOT23-5")
      (libsource (lib "eagle-import") (part "V_REG_MIC52055V"))
    )
  )
  (nets
    (net (code "1") (name "BALLOON_IN") (class "Default")
      (node (ref "D1202") (pin "A") (pinfunction "A_A") (pintype "passive"))
      (node (ref "J1611") (pin "1") (pinfunction "1_1") (pintype "passive"))
      (node (ref "U1202") (pin "2") (pinfunction "PB3(ADC3)_2") (pintype "bidirectional"))
    )
    (net (code "2") (name "BALLOON_MISO") (class "Default")
      (node (ref "J1204") (pin "1") (pinfunction "1_1") (pintype "passive"))
      (node (ref "U1201") (pin "9") (pinfunction "AIN2/EN_9") (pintype "bidirectional"))
      (node (ref "U1202") (pin "6") (pinfunction "PB1(MISO)_6") (pintype "bidirectional"))
    )
    (net (code "3") (name "BALLOON_MOSI") (class "Default")
      (node (ref "J1204") (pin "4") (pinfunction "4_4") (pintype "passive"))
      (node (ref "U1201") (pin "10") (pinfunction "AIN1/PH_10") (pintype "bidirectional"))
      (node (ref "U1202") (pin "5") (pinfunction "PB0(MOSI)_5") (pintype "bidirectional"))
    )
    (net (code "4") (name "BALLOON_OUT") (class "Default")
      (node (ref "D1201") (pin "A") (pinfunction "A_A") (pintype "passive"))
      (node (ref "J1201") (pin "2") (pinfunction "2_2") (pintype "passive"))
      (node (ref "J1612") (pin "2") (pinfunction "2_2") (pintype "passive"))
      (node (ref "R1201") (pin "1") (pinfunction "1_1") (pintype "passive"))
      (node (ref "S1202") (pin "2") (pinfunction "P_2") (pintype "passive"))
    )
    (net (code "5") (name "BALLOON_RST") (class "Default")
      (node (ref "J1204") (pin "5") (pinfunction "5_5") (pintype "passive"))
      (node (ref "R1203") (pin "1") (pinfunction "1_1") (pintype "passive"))
      (node (ref "S1201") (pin "3") (pinfunction "2_3") (pintype "passive"))
      (node (ref "S1201") (pin "4") (pinfunction "2_4") (pintype "passive"))
      (node (ref "U1202") (pin "1") (pinfunction "PB5(NRES)_1") (pintype "bidirectional"))
    )
    (net (code "6") (name "BALLOON_SCK") (class "Default")
      (node (ref "J1202") (pin "2") (pinfunction "2_2") (pintype "passive"))
      (node (ref "J1204") (pin "3") (pinfunction "3_3") (pintype "passive"))
      (node (ref "R1202") (pin "1") (pinfunction "1_1") (pintype "passive"))
      (node (ref "U1202") (pin "7") (pinfunction "PB2(SCK/ADC1)_7") (pintype "bidirectional"))
    )
    (net (code "7") (name "BALLOON_VCC") (class "Default")
      (node (ref "C1201") (pin "2") (pinfunction "2_2") (pintype "passive"))
      (node (ref "C1203") (pin "1") (pinfunction "1_1") (pintype "passive"))
      (node (ref "D1203") (pin "A") (pinfunction "A_A") (pintype "passive"))
      (node (ref "IC1201") (pin "2") (pinfunction "VO_2") (pintype "passive"))
      (node (ref "J1201") (pin "1") (pinfunction "1_1") (pintype "passive"))
      (node (ref "J1202") (pin "1") (pinfunction "1_1") (pintype "passive"))
      (node (ref "J1204") (pin "2") (pinfunction "2_2") (pintype "passive"))
      (node (ref "R1203") (pin "2") (pinfunction "2_2") (pintype "passive"))
      (node (ref "S1202") (pin "1") (pinfunction "O_1") (pintype "passive"))
      (node (ref "TP1201") (pin "TP") (pinfunction "TP_TP") (pintype "input"))
      (node (ref "U1201") (pin "1") (pinfunction "VM_1") (pintype "bidirectional"))
      (node (ref "U1201") (pin "11") (pinfunction "MODE_11") (pintype "bidirectional"))
      (node (ref "U1201") (pin "12") (pinfunction "VCC_12") (pintype "bidirectional"))
      (node (ref "U1202") (pin "8") (pinfunction "VCC_8") (pintype "bidirectional"))
    )
    (net (code "8") (name "COIN_IN") (class "Default")
      (node (ref "D203") (pin "A") (pinfunction "A_A") (pintype "passive"))
      (node (ref "J1601") (pin "1") (pinfunction "1_1") (pintype "passive"))
      (node (ref "JP201") (pin "1") (pinfunction "1_1") (pintype "passive"))
      (node (ref "U201") (pin "2") (pinfunction "A_2") (pintype "bidirectional"))
    )
    (net (code "9") (name "COIN_MISO") (class "Default")
      (node (ref "J204") (pin "1") (pinfunction "1_1") (pintype "passive"))
      (node (ref "U202") (pin "6") (pinfunction "PB1(MISO)_6") (pintype "bidirectional"))
    )
    (net (code "10") (name "COIN_MOSI") (class "Default")
      (node (ref "J204") (pin "4") (pinfunction "4_4") (pintype "passive"))
      (node (ref "U202") (pin "5") (pinfunction "PB0(MOSI)_5") (pintype "bidirectional"))
    )
    (net (code "11") (name "COIN_OUT") (class "Default")
      (node (ref "D202") (pin "A") (pinfunction "A_A") (pintype "passive"))
      (node (ref "J1602") (pin "2") (pinfunction "2_2") (pintype "passive"))
      (node (ref "S202") (pin "2") (pinfunction "P_2") (pintype "passive"))
    )
    (net (code "12") (name "COIN_OUT_SWITCH") (class "Default")
      (node (ref "S202") (pin "3") (pinfunction "S_3") (pintype "passive"))
      (node (ref "U202") (pin "3") (pinfunction "PB4(ADC2)_3") (pintype "bidirectional"))
    )
    (net (code "13") (name "COIN_RST") (class "Default")
      (node (ref "J204") (pin "5") (pinfunction "5_5") (pintype "passive"))
      (node (ref "R204") (pin "1") (pinfunction "1_1") (pintype "passive"))
      (node (ref "S201") (pin "3") (pinfunction "2_3") (pintype "passive"))
      (node (ref "S201") (pin "4") (pinfunction "2_4") (pintype "passive"))
      (node (ref "U202") (pin "1") (pinfunction "PB5(NRES)_1") (pintype "bidirectional"))
    )
    (net (code "14") (name "COIN_SCK") (class "Default")
      (node (ref "J201") (pin "1") (pinfunction "1_1") (pintype "passive"))
      (node (ref "J204") (pin "3") (pinfunction "3_3") (pintype "passive"))
      (node (ref "R203") (pin "1") (pinfunction "1_1") (pintype "passive"))
      (node (ref "U202") (pin "7") (pinfunction "PB2(SCK/ADC1)_7") (pintype "bidirectional"))
    )
    (net (code "15") (name "COIN_VCC") (class "Default")
      (node (ref "C201") (pin "2") (pinfunction "2_2") (pintype "passive"))
      (node (ref "C202") (pin "+") (pinfunction "+_+") (pintype "passive"))
      (node (ref "D204") (pin "A") (pinfunction "A_A") (pintype "passive"))
      (node (ref "J204") (pin "2") (pinfunction "2_2") (pintype "passive"))
      (node (ref "R203") (pin "2") (pinfunction "2_2") (pintype "passive"))
      (node (ref "R204") (pin "2") (pinfunction "2_2") (pintype "passive"))
      (node (ref "S202") (pin "1") (pinfunction "O_1") (pintype "passive"))
      (node (ref "TP202") (pin "TP") (pinfunction "TP_TP") (pintype "input"))
      (node (ref "U201") (pin "5") (pinfunction "P$V+_5") (pintype "bidirectional"))
      (node (ref "U202") (pin "8") (pinfunction "VCC_8") (pintype "bidirectional"))
      (node (ref "U203") (pin "5") (pinfunction "OUT_5") (pintype "passive"))
    )
    (net (code "16") (name "EMAG_IN") (class "Default")
      (node (ref "D803") (pin "A") (pinfunction "A_A") (pintype "passive"))
      (node (ref "J1607") (pin "1") (pinfunction "1_1") (pintype "passive"))
      (node (ref "U802") (pin "1") (pinfunction "A_1") (pintype "input"))
    )
    (net (code "17") (name "EMAG_OUT") (class "Default")
      (node (ref "D802") (pin "A") (pinfunction "A_A") (pintype "passive"))
      (node (ref "J1608") (pin "2") (pinfunction "2_2") (pintype "passive"))
      (node (ref "J801") (pin "1") (pinfunction "1_1") (pintype "passive"))
      (node (ref "R801") (pin "2") (pinfunction "2_2") (pintype "passive"))
      (node (ref "S801") (pin "2") (pinfunction "P_2") (pintype "passive"))
      (node (ref "U801") (pin "2") (pinfunction "A_2") (pintype "bidirectional"))
    )
    (net (code "18") (name "EMAG_VCC") (class "Default")
      (node (ref "C801") (pin "+") (pinfunction "+_+") (pintype "passive"))
      (node (ref "D804") (pin "A") (pinfunction "A_A") (pintype "passive"))
      (node (ref "J801") (pin "2") (pinfunction "2_2") (pintype "passive"))
      (node (ref "S801") (pin "1") (pinfunction "O_1") (pintype "passive"))
      (node (ref "TP801") (pin "TP") (pinfunction "TP_TP") (pintype "input"))
      (node (ref "U801") (pin "5") (pinfunction "P$V+_5") (pintype "bidirectional"))
      (node (ref "U802") (pin "5") (pinfunction "VCC_5") (pintype "power_in"))
      (node (ref "U803") (pin "5") (pinfunction "OUT_5") (pintype "passive"))
    )
    (net (code "19") (name "ENDO_IN") (class "Default")
      (node (ref "D503") (pin "A") (pinfunction "A_A") (pintype "passive"))
      (node (ref "J1604") (pin "1") (pinfunction "1_1") (pintype "passive"))
      (node (ref "U502") (pin "1") (pinfunction "A_1") (pintype "input"))
    )
    (net (code "20") (name "ENDO_MISO") (class "Default")
      (node (ref "J503") (pin "1") (pinfunction "1_1") (pintype "passive"))
      (node (ref "U503") (pin "6") (pinfunction "PB1(MISO)_6") (pintype "bidirectional"))
    )
    (net (code "21") (name "ENDO_MOSI") (class "Default")
      (node (ref "J503") (pin "4") (pinfunction "4_4") (pintype "passive"))
      (node (ref "U503") (pin "5") (pinfunction "PB0(MOSI)_5") (pintype "bidirectional"))
    )
    (net (code "22") (name "ENDO_OUT") (class "Default")
      (node (ref "D502") (pin "A") (pinfunction "A_A") (pintype "passive"))
      (node (ref "J1605") (pin "2") (pinfunction "2_2") (pintype "passive"))
      (node (ref "S502") (pin "2") (pinfunction "P_2") (pintype "passive"))
      (node (ref "U501") (pin "2") (pinfunction "A_2") (pintype "bidirectional"))
    )
    (net (code "23") (name "ENDO_OUT_SWITCH") (class "Default")
      (node (ref "S502") (pin "3") (pinfunction "S_3") (pintype "passive"))
      (node (ref "U503") (pin "3") (pinfunction "PB4(ADC2)_3") (pintype "bidirectional"))
    )
    (net (code "24") (name "ENDO_RST") (class "Default")
      (node (ref "J503") (pin "5") (pinfunction "5_5") (pintype "passive"))
      (node (ref "R504") (pin "1") (pinfunction "1_1") (pintype "passive"))
      (node (ref "S501") (pin "3") (pinfunction "2_3") (pintype "passive"))
      (node (ref "S501") (pin "4") (pinfunction "2_4") (pintype "passive"))
      (node (ref "U503") (pin "1") (pinfunction "PB5(NRES)_1") (pintype "bidirectional"))
    )
    (net (code "25") (name "ENDO_SCK") (class "Default")
      (node (ref "J503") (pin "3") (pinfunction "3_3") (pintype "passive"))
      (node (ref "R501") (pin "2") (pinfunction "2_2") (pintype "passive"))
      (node (ref "U503") (pin "7") (pinfunction "PB2(SCK/ADC1)_7") (pintype "bidirectional"))
    )
    (net (code "26") (name "ENDO_VCC") (class "Default")
      (node (ref "C501") (pin "2") (pinfunction "2_2") (pintype "passive"))
      (node (ref "C502") (pin "+") (pinfunction "+_+") (pintype "passive"))
      (node (ref "D504") (pin "A") (pinfunction "A_A") (pintype "passive"))
      (node (ref "J503") (pin "2") (pinfunction "2_2") (pintype "passive"))
      (node (ref "R504") (pin "2") (pinfunction "2_2") (pintype "passive"))
      (node (ref "S502") (pin "1") (pinfunction "O_1") (pintype "passive"))
      (node (ref "TP503") (pin "TP") (pinfunction "TP_TP") (pintype "input"))
      (node (ref "U501") (pin "5") (pinfunction "P$V+_5") (pintype "bidirectional"))
      (node (ref "U502") (pin "5") (pinfunction "VCC_5") (pintype "power_in"))
      (node (ref "U503") (pin "8") (pinfunction "VCC_8") (pintype "bidirectional"))
      (node (ref "U504") (pin "5") (pinfunction "OUT_5") (pintype "passive"))
    )
    (net (code "27") (name "END_IN") (class "Default")
      (node (ref "D1501") (pin "A") (pinfunction "A_A") (pintype "passive"))
      (node (ref "J1501") (pin "1") (pinfunction "1_1") (pintype "passive"))
      (node (ref "J1614") (pin "1") (pinfunction "1_1") (pintype "passive"))
      (node (ref "R1501") (pin "2") (pinfunction "2_2") (pintype "passive"))
    )
    (net (code "28") (name "END_VCC") (class "Default")
      (node (ref "C1502") (pin "1") (pinfunction "1_1") (pintype "passive"))
      (node (ref "D1502") (pin "A") (pinfunction "A_A") (pintype "passive"))
      (node (ref "IC1501") (pin "2") (pinfunction "VO_2") (pintype "passive"))
      (node (ref "J1501") (pin "2") (pinfunction "2_2") (pintype "passive"))
      (node (ref "TP1501") (pin "TP") (pinfunction "TP_TP") (pintype "input"))
    )
    (net (code "29") (name "EXO_IN") (class "Default")
      (node (ref "D303") (pin "A") (pinfunction "A_A") (pintype "passive"))
      (node (ref "J1602") (pin "1") (pinfunction "1_1") (pintype "passive"))
      (node (ref "U302") (pin "1") (pinfunction "A_1") (pintype "input"))
    )
    (net (code "30") (name "EXO_MISO") (class "Default")
      (node (ref "J301") (pin "1") (pinfunction "1_1") (pintype "passive"))
      (node (ref "U303") (pin "6") (pinfunction "PB1(MISO)_6") (pintype "bidirectional"))
    )
    (net (code "31") (name "EXO_MOSI") (class "Default")
      (node (ref "J301") (pin "4") (pinfunction "4_4") (pintype "passive"))
      (node (ref "U303") (pin "5") (pinfunction "PB0(MOSI)_5") (pintype "bidirectional"))
    )
    (net (code "32") (name "EXO_OUT") (class "Default")
      (node (ref "D302") (pin "A") (pinfunction "A_A") (pintype "passive"))
      (node (ref "J1603") (pin "2") (pinfunction "2_2") (pintype "passive"))
      (node (ref "S302") (pin "2") (pinfunction "P_2") (pintype "passive"))
      (node (ref "U301") (pin "2") (pinfunction "A_2") (pintype "bidirectional"))
    )
    (net (code "33") (name "EXO_OUT_SWITCH") (class "Default")
      (node (ref "S302") (pin "3") (pinfunction "S_3") (pintype "passive"))
      (node (ref "U303") (pin "3") (pinfunction "PB4(ADC2)_3") (pintype "bidirectional"))
    )
    (net (code "34") (name "EXO_RST") (class "Default")
      (node (ref "J301") (pin "5") (pinfunction "5_5") (pintype "passive"))
      (node (ref "R304") (pin "1") (pinfunction "1_1") (pintype "passive"))
      (node (ref "S301") (pin "3") (pinfunction "2_3") (pintype "passive"))
      (node (ref "S301") (pin "4") (pinfunction "2_4") (pintype "passive"))
      (node (ref "U303") (pin "1") (pinfunction "PB5(NRES)_1") (pintype "bidirectional"))
    )
    (net (code "35") (name "EXO_SCK") (class "Default")
      (node (ref "J301") (pin "3") (pinfunction "3_3") (pintype "passive"))
      (node (ref "R301") (pin "2") (pinfunction "2_2") (pintype "passive"))
      (node (ref "R303") (pin "1") (pinfunction "P$1_1") (pintype "bidirectional"))
      (node (ref "U303") (pin "7") (pinfunction "PB2(SCK/ADC1)_7") (pintype "bidirectional"))
    )
    (net (code "36") (name "EXO_VCC") (class "Default")
      (node (ref "C301") (pin "2") (pinfunction "2_2") (pintype "passive"))
      (node (ref "C302") (pin "+") (pinfunction "+_+") (pintype "passive"))
      (node (ref "D304") (pin "A") (pinfunction "A_A") (pintype "passive"))
      (node (ref "J301") (pin "2") (pinfunction "2_2") (pintype "passive"))
      (node (ref "Q301") (pin "3") (pinfunction "C_3") (pintype "passive"))
      (node (ref "R303") (pin "2") (pinfunction "P$2_2") (pintype "bidirectional"))
      (node (ref "R304") (pin "2") (pinfunction "2_2") (pintype "passive"))
      (node (ref "S302") (pin "1") (pinfunction "O_1") (pintype "passive"))
      (node (ref "U301") (pin "5") (pinfunction "P$V+_5") (pintype "bidirectional"))
      (node (ref "U302") (pin "5") (pinfunction "VCC_5") (pintype "power_in"))
      (node (ref "U303") (pin "8") (pinfunction "VCC_8") (pintype "bidirectional"))
      (node (ref "U304") (pin "5") (pinfunction "OUT_5") (pintype "passive"))
    )
    (net (code "37") (name "EXP_IN") (class "Default")
      (node (ref "D1003") (pin "A") (pinfunction "A_A") (pintype "passive"))
      (node (ref "J1609") (pin "1") (pinfunction "1_1") (pintype "passive"))
      (node (ref "U1001") (pin "2") (pinfunction "PB3(ADC3)_2") (pintype "bidirectional"))
    )
    (net (code "38") (name "EXP_MISO") (class "Default")
      (node (ref "J1005") (pin "1") (pinfunction "1_1") (pintype "passive"))
      (node (ref "U1001") (pin "6") (pinfunction "PB1(MISO)_6") (pintype "bidirectional"))
    )
    (net (code "39") (name "EXP_MOSI") (class "Default")
      (node (ref "J1005") (pin "4") (pinfunction "4_4") (pintype "passive"))
      (node (ref "R1001") (pin "1") (pinfunction "1_1") (pintype "passive"))
      (node (ref "R1002") (pin "1") (pinfunction "1_1") (pintype "passive"))
      (node (ref "U1001") (pin "5") (pinfunction "PB0(MOSI)_5") (pintype "bidirectional"))
    )
    (net (code "40") (name "EXP_OUT") (class "Default")
      (node (ref "D1002") (pin "A") (pinfunction "A_A") (pintype "passive"))
      (node (ref "J1004") (pin "2") (pinfunction "2_2") (pintype "passive"))
      (node (ref "J1610") (pin "2") (pinfunction "2_2") (pintype "passive"))
      (node (ref "R1004") (pin "1") (pinfunction "1_1") (pintype "passive"))
      (node (ref "S1002") (pin "2") (pinfunction "P_2") (pintype "passive"))
    )
    (net (code "41") (name "EXP_RST") (class "Default")
      (node (ref "J1005") (pin "5") (pinfunction "5_5") (pintype "passive"))
      (node (ref "R1005") (pin "1") (pinfunction "1_1") (pintype "passive"))
      (node (ref "S1001") (pin "3") (pinfunction "2_3") (pintype "passive"))
      (node (ref "S1001") (pin "4") (pinfunction "2_4") (pintype "passive"))
      (node (ref "U1001") (pin "1") (pinfunction "PB5(NRES)_1") (pintype "bidirectional"))
    )
    (net (code "42") (name "EXP_SCK") (class "Default")
      (node (ref "J1005") (pin "3") (pinfunction "3_3") (pintype "passive"))
      (node (ref "R1003") (pin "2") (pinfunction "2_2") (pintype "passive"))
      (node (ref "U1001") (pin "7") (pinfunction "PB2(SCK/ADC1)_7") (pintype "bidirectional"))
    )
    (net (code "43") (name "EXP_VCC") (class "Default")
      (node (ref "C1001") (pin "2") (pinfunction "2_2") (pintype "passive"))
      (node (ref "C1002") (pin "+") (pinfunction "+_+") (pintype "passive"))
      (node (ref "D1004") (pin "A") (pinfunction "A_A") (pintype "passive"))
      (node (ref "J1004") (pin "1") (pinfunction "1_1") (pintype "passive"))
      (node (ref "J1005") (pin "2") (pinfunction "2_2") (pintype "passive"))
      (node (ref "R1005") (pin "2") (pinfunction "2_2") (pintype "passive"))
      (node (ref "S1002") (pin "1") (pinfunction "O_1") (pintype "passive"))
      (node (ref "TP1001") (pin "TP") (pinfunction "TP_TP") (pintype "input"))
      (node (ref "U1001") (pin "8") (pinfunction "VCC_8") (pintype "bidirectional"))
      (node (ref "U1002") (pin "5") (pinfunction "OUT_5") (pintype "passive"))
    )
    (net (code "44") (name "GND") (class "Default")
      (node (ref "C1001") (pin "1") (pinfunction "1_1") (pintype "passive"))
      (node (ref "C1002") (pin "-") (pinfunction "-_-") (pintype "passive"))
      (node (ref "C101") (pin "-") (pinfunction "-_-") (pintype "passive"))
      (node (ref "C1101") (pin "1") (pinfunction "1_1") (pintype "passive"))
      (node (ref "C1102") (pin "1") (pinfunction "1_1") (pintype "passive"))
      (node (ref "C1103") (pin "2") (pinfunction "2_2") (pintype "passive"))
      (node (ref "C1201") (pin "1") (pinfunction "1_1") (pintype "passive"))
      (node (ref "C1202") (pin "1") (pinfunction "1_1") (pintype "passive"))
      (node (ref "C1203") (pin "2") (pinfunction "2_2") (pintype "passive"))
      (node (ref "C1301") (pin "1") (pinfunction "1_1") (pintype "passive"))
      (node (ref "C1302") (pin "1") (pinfunction "1_1") (pintype "passive"))
      (node (ref "C1303") (pin "2") (pinfunction "2_2") (pintype "passive"))
      (node (ref "C1401") (pin "-") (pinfunction "-_-") (pintype "passive"))
      (node (ref "C1501") (pin "1") (pinfunction "1_1") (pintype "passive"))
      (node (ref "C1502") (pin "2") (pinfunction "2_2") (pintype "passive"))
      (node (ref "C1601") (pin "-") (pinfunction "-_-") (pintype "passive"))
      (node (ref "C1602") (pin "-") (pinfunction "-_-") (pintype "passive"))
      (node (ref "C1603") (pin "-") (pinfunction "-_-") (pintype "passive"))
      (node (ref "C1604") (pin "2") (pinfunction "2_2") (pintype "passive"))
      (node (ref "C201") (pin "1") (pinfunction "1_1") (pintype "passive"))
      (node (ref "C202") (pin "-") (pinfunction "-_-") (pintype "passive"))
      (node (ref "C301") (pin "1") (pinfunction "1_1") (pintype "passive"))
      (node (ref "C302") (pin "-") (pinfunction "-_-") (pintype "passive"))
      (node (ref "C401") (pin "1") (pinfunction "1_1") (pintype "passive"))
      (node (ref "C402") (pin "-") (pinfunction "-_-") (pintype "passive"))
      (node (ref "C501") (pin "1") (pinfunction "1_1") (pintype "passive"))
      (node (ref "C502") (pin "-") (pinfunction "-_-") (pintype "passive"))
      (node (ref "C601") (pin "1") (pinfunction "1_1") (pintype "passive"))
      (node (ref "C602") (pin "-") (pinfunction "-_-") (pintype "passive"))
      (node (ref "C701") (pin "1") (pinfunction "1_1") (pintype "passive"))
      (node (ref "C702") (pin "1") (pinfunction "1_1") (pintype "passive"))
      (node (ref "C703") (pin "-") (pinfunction "-_-") (pintype "passive"))
      (node (ref "C801") (pin "-") (pinfunction "-_-") (pintype "passive"))
      (node (ref "C901") (pin "1") (pinfunction "1_1") (pintype "passive"))
      (node (ref "C902") (pin "-") (pinfunction "-_-") (pintype "passive"))
      (node (ref "D1601") (pin "A") (pinfunction "A_A") (pintype "passive"))
      (node (ref "D301") (pin "K") (pinfunction "C_K") (pintype "passive"))
      (node (ref "IC1101") (pin "3") (pinfunction "GND_3") (pintype "passive"))
      (node (ref "IC1201") (pin "3") (pinfunction "GND_3") (pintype "passive"))
      (node (ref "IC1301") (pin "3") (pinfunction "GND_3") (pintype "passive"))
      (node (ref "IC1501") (pin "3") (pinfunction "GND_3") (pintype "passive"))
      (node (ref "J1002") (pin "2") (pinfunction "2_2") (pintype "passive"))
      (node (ref "J1003") (pin "2") (pinfunction "2_2") (pintype "passive"))
      (node (ref "J1005") (pin "6") (pinfunction "6_6") (pintype "passive"))
      (node (ref "J1104") (pin "6") (pinfunction "6_6") (pintype "passive"))
      (node (ref "J1204") (pin "6") (pinfunction "6_6") (pintype "passive"))
      (node (ref "J1304") (pin "6") (pinfunction "6_6") (pintype "passive"))
      (node (ref "J1501") (pin "3") (pinfunction "3_3") (pintype "passive"))
      (node (ref "J201") (pin "3") (pinfunction "3_3") (pintype "passive"))
      (node (ref "J202") (pin "2") (pinfunction "2_2") (pintype "passive"))
      (node (ref "J204") (pin "6") (pinfunction "6_6") (pintype "passive"))
      (node (ref "J301") (pin "6") (pinfunction "6_6") (pintype "passive"))
      (node (ref "J401") (pin "6") (pinfunction "6_6") (pintype "passive"))
      (node (ref "J501") (pin "2") (pinfunction "2_2") (pintype "passive"))
      (node (ref "J503") (pin "6") (pinfunction "6_6") (pintype "passive"))
      (node (ref "J601") (pin "2") (pinfunction "2_2") (pintype "passive"))
      (node (ref "J603") (pin "6") (pinfunction "6_6") (pintype "passive"))
      (node (ref "J701") (pin "2") (pinfunction "2_2") (pintype "passive"))
      (node (ref "J703") (pin "6") (pinfunction "6_6") (pintype "passive"))
      (node (ref "J704") (pin "6") (pinfunction "6_6") (pintype "passive"))
      (node (ref "J903") (pin "6") (pinfunction "6_6") (pintype "passive"))
      (node (ref "Q1001") (pin "1") (pinfunction "S_1") (pintype "passive"))
      (node (ref "Q1001") (pin "2") (pinfunction "S_2") (pintype "passive"))
      (node (ref "Q1001") (pin "3") (pinfunction "S_3") (pintype "passive"))
      (node (ref "Q1401") (pin "1") (pinfunction "S_1") (pintype "passive"))
      (node (ref "Q1401") (pin "2") (pinfunction "S_2") (pintype "passive"))
      (node (ref "Q1401") (pin "3") (pinfunction "S_3") (pintype "passive"))
      (node (ref "Q201") (pin "1") (pinfunction "S_1") (pintype "passive"))
      (node (ref "Q201") (pin "2") (pinfunction "S_2") (pintype "passive"))
      (node (ref "Q201") (pin "3") (pinfunction "S_3") (pintype "passive"))
      (node (ref "Q501") (pin "1") (pinfunction "S_1") (pintype "passive"))
      (node (ref "Q501") (pin "2") (pinfunction "S_2") (pintype "passive"))
      (node (ref "Q501") (pin "3") (pinfunction "S_3") (pintype "passive"))
      (node (ref "Q601") (pin "1") (pinfunction "S_1") (pintype "passive"))
      (node (ref "Q601") (pin "2") (pinfunction "S_2") (pintype "passive"))
      (node (ref "Q601") (pin "3") (pinfunction "S_3") (pintype "passive"))
      (node (ref "Q801") (pin "1") (pinfunction "S_1") (pintype "passive"))
      (node (ref "Q801") (pin "2") (pinfunction "S_2") (pintype "passive"))
      (node (ref "Q801") (pin "3") (pinfunction "S_3") (pintype "passive"))
      (node (ref "Q901") (pin "1") (pinfunction "S_1") (pintype "passive"))
      (node (ref "Q901") (pin "2") (pinfunction "S_2") (pintype "passive"))
      (node (ref "Q901") (pin "3") (pinfunction "S_3") (pintype "passive"))
      (node (ref "R1002") (pin "2") (pinfunction "2_2") (pintype "passive"))
      (node (ref "R1004") (pin "2") (pinfunction "2_2") (pintype "passive"))
      (node (ref "R1006") (pin "1") (pinfunction "1_1") (pintype "passive"))
      (node (ref "R1007") (pin "1") (pinfunction "1_1") (pintype "passive"))
      (node (ref "R1008") (pin "1") (pinfunction "1_1") (pintype "passive"))
      (node (ref "R102") (pin "1") (pinfunction "1_1") (pintype "passive"))
      (node (ref "R103") (pin "1") (pinfunction "1_1") (pintype "passive"))
      (node (ref "R1101") (pin "2") (pinfunction "2_2") (pintype "passive"))
      (node (ref "R1102") (pin "2") (pinfunction "2_2") (pintype "passive"))
      (node (ref "R1104") (pin "1") (pinfunction "1_1") (pintype "passive"))
      (node (ref "R1105") (pin "1") (pinfunction "1_1") (pintype "passive"))
      (node (ref "R1106") (pin "1") (pinfunction "1_1") (pintype "passive"))
      (node (ref "R1201") (pin "2") (pinfunction "2_2") (pintype "passive"))
      (node (ref "R1202") (pin "2") (pinfunction "2_2") (pintype "passive"))
      (node (ref "R1204") (pin "1") (pinfunction "1_1") (pintype "passive"))
      (node (ref "R1205") (pin "1") (pinfunction "1_1") (pintype "passive"))
      (node (ref "R1206") (pin "1") (pinfunction "1_1") (pintype "passive"))
      (node (ref "R1301") (pin "2") (pinfunction "2_2") (pintype "passive"))
      (node (ref "R1302") (pin "2") (pinfunction "2_2") (pintype "passive"))
      (node (ref "R1304") (pin "1") (pinfunction "1_1") (pintype "passive"))
      (node (ref "R1305") (pin "1") (pinfunction "1_1") (pintype "passive"))
      (node (ref "R1306") (pin "1") (pinfunction "1_1") (pintype "passive"))
      (node (ref "R1401") (pin "2") (pinfunction "2_2") (pintype "passive"))
      (node (ref "R1403") (pin "2") (pinfunction "2_2") (pintype "passive"))
      (node (ref "R1404") (pin "1") (pinfunction "1_1") (pintype "passive"))
      (node (ref "R1405") (pin "1") (pinfunction "1_1") (pintype "passive"))
      (node (ref "R1406") (pin "1") (pinfunction "1_1") (pintype "passive"))
      (node (ref "R1501") (pin "1") (pinfunction "1_1") (pintype "passive"))
      (node (ref "R1502") (pin "1") (pinfunction "1_1") (pintype "passive"))
      (node (ref "R1503") (pin "1") (pinfunction "1_1") (pintype "passive"))
      (node (ref "R202") (pin "2") (pinfunction "2_2") (pintype "passive"))
      (node (ref "R205") (pin "1") (pinfunction "1_1") (pintype "passive"))
      (node (ref "R206") (pin "1") (pinfunction "1_1") (pintype "passive"))
      (node (ref "R207") (pin "1") (pinfunction "1_1") (pintype "passive"))
      (node (ref "R301") (pin "1") (pinfunction "1_1") (pintype "passive"))
      (node (ref "R305") (pin "1") (pinfunction "1_1") (pintype "passive"))
      (node (ref "R306") (pin "1") (pinfunction "1_1") (pintype "passive"))
      (node (ref "R307") (pin "1") (pinfunction "1_1") (pintype "passive"))
      (node (ref "R401") (pin "1") (pinfunction "1_1") (pintype "passive"))
      (node (ref "R404") (pin "2") (pinfunction "2_2") (pintype "passive"))
      (node (ref "R406") (pin "1") (pinfunction "1_1") (pintype "passive"))
      (node (ref "R407") (pin "1") (pinfunction "1_1") (pintype "passive"))
      (node (ref "R408") (pin "1") (pinfunction "1_1") (pintype "passive"))
      (node (ref "R503") (pin "2") (pinfunction "2_2") (pintype "passive"))
      (node (ref "R505") (pin "1") (pinfunction "1_1") (pintype "passive"))
      (node (ref "R506") (pin "1") (pinfunction "1_1") (pintype "passive"))
      (node (ref "R507") (pin "1") (pinfunction "1_1") (pintype "passive"))
      (node (ref "R602") (pin "2") (pinfunction "2_2") (pintype "passive"))
      (node (ref "R605") (pin "1") (pinfunction "1_1") (pintype "passive"))
      (node (ref "R606") (pin "1") (pinfunction "1_1") (pintype "passive"))
      (node (ref "R607") (pin "1") (pinfunction "1_1") (pintype "passive"))
      (node (ref "R705") (pin "1") (pinfunction "1_1") (pintype "passive"))
      (node (ref "R706") (pin "1") (pinfunction "1_1") (pintype "passive"))
      (node (ref "R707") (pin "1") (pinfunction "1_1") (pintype "passive"))
      (node (ref "R801") (pin "1") (pinfunction "1_1") (pintype "passive"))
      (node (ref "R803") (pin "2") (pinfunction "2_2") (pintype "passive"))
      (node (ref "R804") (pin "1") (pinfunction "1_1") (pintype "passive"))
      (node (ref "R805") (pin "1") (pinfunction "1_1") (pintype "passive"))
      (node (ref "R806") (pin "1") (pinfunction "1_1") (pintype "passive"))
      (node (ref "R902") (pin "2") (pinfunction "2_2") (pintype "passive"))
      (node (ref "R903") (pin "2") (pinfunction "2_2") (pintype "passive"))
      (node (ref "R905") (pin "1") (pinfunction "1_1") (pintype "passive"))
      (node (ref "R906") (pin "1") (pinfunction "1_1") (pintype "passive"))
      (node (ref "R907") (pin "1") (pinfunction "1_1") (pintype "passive"))
      (node (ref "S1001") (pin "1") (pinfunction "1_1") (pintype "passive"))
      (node (ref "S1001") (pin "2") (pinfunction "1_2") (pintype "passive"))
      (node (ref "S101") (pin "P$1") (pinfunction "1_P$1") (pintype "passive"))
      (node (ref "S1101") (pin "1") (pinfunction "1_1") (pintype "passive"))
      (node (ref "S1101") (pin "2") (pinfunction "1_2") (pintype "passive"))
      (node (ref "S1201") (pin "1") (pinfunction "1_1") (pintype "passive"))
      (node (ref "S1201") (pin "2") (pinfunction "1_2") (pintype "passive"))
      (node (ref "S1301") (pin "1") (pinfunction "1_1") (pintype "passive"))
      (node (ref "S1301") (pin "2") (pinfunction "1_2") (pintype "passive"))
      (node (ref "S201") (pin "1") (pinfunction "1_1") (pintype "passive"))
      (node (ref "S201") (pin "2") (pinfunction "1_2") (pintype "passive"))
      (node (ref "S301") (pin "1") (pinfunction "1_1") (pintype "passive"))
      (node (ref "S301") (pin "2") (pinfunction "1_2") (pintype "passive"))
      (node (ref "S401") (pin "1") (pinfunction "1_1") (pintype "passive"))
      (node (ref "S401") (pin "2") (pinfunction "1_2") (pintype "passive"))
      (node (ref "S501") (pin "1") (pinfunction "1_1") (pintype "passive"))
      (node (ref "S501") (pin "2") (pinfunction "1_2") (pintype "passive"))
      (node (ref "S601") (pin "1") (pinfunction "1_1") (pintype "passive"))
      (node (ref "S601") (pin "2") (pinfunction "1_2") (pintype "passive"))
      (node (ref "S701") (pin "1") (pinfunction "1_1") (pintype "passive"))
      (node (ref "S701") (pin "2") (pinfunction "1_2") (pintype "passive"))
      (node (ref "S702") (pin "1") (pinfunction "1_1") (pintype "passive"))
      (node (ref "S702") (pin "2") (pinfunction "1_2") (pintype "passive"))
      (node (ref "S901") (pin "1") (pinfunction "1_1") (pintype "passive"))
      (node (ref "S901") (pin "2") (pinfunction "1_2") (pintype "passive"))
      (node (ref "U1001") (pin "4") (pinfunction "GND_4") (pintype "bidirectional"))
      (node (ref "U1002") (pin "2") (pinfunction "GND_2") (pintype "input"))
      (node (ref "U101") (pin "3") (pinfunction "P$V-_3") (pintype "bidirectional"))
      (node (ref "U102") (pin "2") (pinfunction "GND_2") (pintype "input"))
      (node (ref "U1101") (pin "6") (pinfunction "VSS_6") (pintype "bidirectional"))
      (node (ref "U1101") (pin "PAD") (pinfunction "VSS_PAD") (pintype "bidirectional"))
      (node (ref "U1102") (pin "4") (pinfunction "GND_4") (pintype "bidirectional"))
      (node (ref "U1201") (pin "6") (pinfunction "VSS_6") (pintype "bidirectional"))
      (node (ref "U1201") (pin "PAD") (pinfunction "VSS_PAD") (pintype "bidirectional"))
      (node (ref "U1202") (pin "4") (pinfunction "GND_4") (pintype "bidirectional"))
      (node (ref "U1301") (pin "6") (pinfunction "VSS_6") (pintype "bidirectional"))
      (node (ref "U1301") (pin "PAD") (pinfunction "VSS_PAD") (pintype "bidirectional"))
      (node (ref "U1302") (pin "4") (pinfunction "GND_4") (pintype "bidirectional"))
      (node (ref "U1401") (pin "3") (pinfunction "P$V-_3") (pintype "bidirectional"))
      (node (ref "U1402") (pin "2") (pinfunction "GND_2") (pintype "input"))
      (node (ref "U201") (pin "3") (pinfunction "P$V-_3") (pintype "bidirectional"))
      (node (ref "U202") (pin "4") (pinfunction "GND_4") (pintype "bidirectional"))
      (node (ref "U203") (pin "2") (pinfunction "GND_2") (pintype "input"))
      (node (ref "U301") (pin "3") (pinfunction "P$V-_3") (pintype "bidirectional"))
      (node (ref "U302") (pin "3") (pinfunction "GND_3") (pintype "power_in"))
      (node (ref "U303") (pin "4") (pinfunction "GND_4") (pintype "bidirectional"))
      (node (ref "U304") (pin "2") (pinfunction "GND_2") (pintype "input"))
      (node (ref "U401") (pin "3") (pinfunction "P$V-_3") (pintype "bidirectional"))
      (node (ref "U402") (pin "3") (pinfunction "GND_3") (pintype "power_in"))
      (node (ref "U403") (pin "4") (pinfunction "GND_4") (pintype "bidirectional"))
      (node (ref "U404") (pin "2") (pinfunction "GND_2") (pintype "input"))
      (node (ref "U501") (pin "3") (pinfunction "P$V-_3") (pintype "bidirectional"))
      (node (ref "U502") (pin "3") (pinfunction "GND_3") (pintype "power_in"))
      (node (ref "U503") (pin "4") (pinfunction "GND_4") (pintype "bidirectional"))
      (node (ref "U504") (pin "2") (pinfunction "GND_2") (pintype "input"))
      (node (ref "U601") (pin "3") (pinfunction "P$V-_3") (pintype "bidirectional"))
      (node (ref "U602") (pin "3") (pinfunction "GND_3") (pintype "power_in"))
      (node (ref "U603") (pin "4") (pinfunction "GND_4") (pintype "bidirectional"))
      (node (ref "U604") (pin "2") (pinfunction "GND_2") (pintype "input"))
      (node (ref "U701") (pin "4") (pinfunction "GND_4") (pintype "bidirectional"))
      (node (ref "U702") (pin "4") (pinfunction "GND_4") (pintype "bidirectional"))
      (node (ref "U703") (pin "2") (pinfunction "GND_2") (pintype "input"))
      (node (ref "U801") (pin "3") (pinfunction "P$V-_3") (pintype "bidirectional"))
      (node (ref "U802") (pin "3") (pinfunction "GND_3") (pintype "power_in"))
      (node (ref "U803") (pin "2") (pinfunction "GND_2") (pintype "input"))
      (node (ref "U901") (pin "4") (pinfunction "GND_4") (pintype "bidirectional"))
      (node (ref "U902") (pin "2") (pinfunction "GND_2") (pintype "input"))
      (node (ref "X1601") (pin "2") (pinfunction "1_2") (pintype "passive"))
    )
    (net (code "45") (name "IMA0.5_IN") (class "Default")
      (node (ref "D1403") (pin "A") (pinfunction "A_A") (pintype "passive"))
      (node (ref "J1613") (pin "1") (pinfunction "1_1") (pintype "passive"))
      (node (ref "JP1401") (pin "1") (pinfunction "1_1") (pintype "passive"))
      (node (ref "U1401") (pin "2") (pinfunction "A_2") (pintype "bidirectional"))
    )
    (net (code "46") (name "IMA0.5_OUT") (class "Default")
      (node (ref "D1402") (pin "A") (pinfunction "A_A") (pintype "passive"))
      (node (ref "J1401") (pin "2") (pinfunction "2_2") (pintype "passive"))
      (node (ref "J1614") (pin "2") (pinfunction "2_2") (pintype "passive"))
      (node (ref "R1401") (pin "1") (pinfunction "1_1") (pintype "passive"))
      (node (ref "S1401") (pin "2") (pinfunction "P_2") (pintype "passive"))
    )
    (net (code "47") (name "IMA0.5_VCC") (class "Default")
      (node (ref "C1401") (pin "+") (pinfunction "+_+") (pintype "passive"))
      (node (ref "D1404") (pin "A") (pinfunction "A_A") (pintype "passive"))
      (node (ref "J1401") (pin "1") (pinfunction "1_1") (pintype "passive"))
      (node (ref "S1401") (pin "1") (pinfunction "O_1") (pintype "passive"))
      (node (ref "TP1402") (pin "TP") (pinfunction "TP_TP") (pintype "input"))
      (node (ref "U1401") (pin "5") (pinfunction "P$V+_5") (pintype "bidirectional"))
      (node (ref "U1402") (pin "5") (pinfunction "OUT_5") (pintype "passive"))
    )
    (net (code "48") (name "IMA7_IN") (class "Default")
      (node (ref "D1302") (pin "A") (pinfunction "A_A") (pintype "passive"))
      (node (ref "J1612") (pin "1") (pinfunction "1_1") (pintype "passive"))
      (node (ref "U1302") (pin "2") (pinfunction "PB3(ADC3)_2") (pintype "bidirectional"))
    )
    (net (code "49") (name "IMA7_MISO") (class "Default")
      (node (ref "J1304") (pin "1") (pinfunction "1_1") (pintype "passive"))
      (node (ref "U1301") (pin "9") (pinfunction "AIN2/EN_9") (pintype "bidirectional"))
      (node (ref "U1302") (pin "6") (pinfunction "PB1(MISO)_6") (pintype "bidirectional"))
    )
    (net (code "50") (name "IMA7_MOSI") (class "Default")
      (node (ref "J1304") (pin "4") (pinfunction "4_4") (pintype "passive"))
      (node (ref "U1301") (pin "10") (pinfunction "AIN1/PH_10") (pintype "bidirectional"))
      (node (ref "U1302") (pin "5") (pinfunction "PB0(MOSI)_5") (pintype "bidirectional"))
    )
    (net (code "51") (name "IMA7_OUT") (class "Default")
      (node (ref "D1301") (pin "A") (pinfunction "A_A") (pintype "passive"))
      (node (ref "J1301") (pin "2") (pinfunction "2_2") (pintype "passive"))
      (node (ref "J1613") (pin "2") (pinfunction "2_2") (pintype "passive"))
      (node (ref "R1301") (pin "1") (pinfunction "1_1") (pintype "passive"))
      (node (ref "S1302") (pin "2") (pinfunction "P_2") (pintype "passive"))
    )
    (net (code "52") (name "IMA7_RST") (class "Default")
      (node (ref "J1304") (pin "5") (pinfunction "5_5") (pintype "passive"))
      (node (ref "R1303") (pin "1") (pinfunction "1_1") (pintype "passive"))
      (node (ref "S1301") (pin "3") (pinfunction "2_3") (pintype "passive"))
      (node (ref "S1301") (pin "4") (pinfunction "2_4") (pintype "passive"))
      (node (ref "U1302") (pin "1") (pinfunction "PB5(NRES)_1") (pintype "bidirectional"))
    )
    (net (code "53") (name "IMA7_SCK") (class "Default")
      (node (ref "J1302") (pin "2") (pinfunction "2_2") (pintype "passive"))
      (node (ref "J1304") (pin "3") (pinfunction "3_3") (pintype "passive"))
      (node (ref "R1302") (pin "1") (pinfunction "1_1") (pintype "passive"))
      (node (ref "U1302") (pin "7") (pinfunction "PB2(SCK/ADC1)_7") (pintype "bidirectional"))
    )
    (net (code "54") (name "IMA7_VCC") (class "Default")
      (node (ref "C1301") (pin "2") (pinfunction "2_2") (pintype "passive"))
      (node (ref "C1303") (pin "1") (pinfunction "1_1") (pintype "passive"))
      (node (ref "D1303") (pin "A") (pinfunction "A_A") (pintype "passive"))
      (node (ref "IC1301") (pin "2") (pinfunction "VO_2") (pintype "passive"))
      (node (ref "J1301") (pin "1") (pinfunction "1_1") (pintype "passive"))
      (node (ref "J1302") (pin "1") (pinfunction "1_1") (pintype "passive"))
      (node (ref "J1304") (pin "2") (pinfunction "2_2") (pintype "passive"))
      (node (ref "R1303") (pin "2") (pinfunction "2_2") (pintype "passive"))
      (node (ref "S1302") (pin "1") (pinfunction "O_1") (pintype "passive"))
      (node (ref "TP1301") (pin "TP") (pinfunction "TP_TP") (pintype "input"))
      (node (ref "U1301") (pin "1") (pinfunction "VM_1") (pintype "bidirectional"))
      (node (ref "U1301") (pin "11") (pinfunction "MODE_11") (pintype "bidirectional"))
      (node (ref "U1301") (pin "12") (pinfunction "VCC_12") (pintype "bidirectional"))
      (node (ref "U1302") (pin "8") (pinfunction "VCC_8") (pintype "bidirectional"))
    )
    (net (code "55") (name "IR_1_MISO") (class "Default")
      (node (ref "J702") (pin "1") (pinfunction "1_1") (pintype "passive"))
      (node (ref "J704") (pin "1") (pinfunction "1_1") (pintype "passive"))
      (node (ref "U702") (pin "6") (pinfunction "PB1(MISO)_6") (pintype "bidirectional"))
    )
    (net (code "56") (name "IR_1_MOSI") (class "Default")
      (node (ref "J704") (pin "4") (pinfunction "4_4") (pintype "passive"))
      (node (ref "U702") (pin "5") (pinfunction "PB0(MOSI)_5") (pintype "bidirectional"))
    )
    (net (code "57") (name "IR_1_RST") (class "Default")
      (node (ref "J704") (pin "5") (pinfunction "5_5") (pintype "passive"))
      (node (ref "R704") (pin "1") (pinfunction "1_1") (pintype "passive"))
      (node (ref "S702") (pin "3") (pinfunction "2_3") (pintype "passive"))
      (node (ref "S702") (pin "4") (pinfunction "2_4") (pintype "passive"))
      (node (ref "U702") (pin "1") (pinfunction "PB5(NRES)_1") (pintype "bidirectional"))
    )
    (net (code "58") (name "IR_1_SCK") (class "Default")
      (node (ref "J704") (pin "3") (pinfunction "3_3") (pintype "passive"))
      (node (ref "U702") (pin "7") (pinfunction "PB2(SCK/ADC1)_7") (pintype "bidirectional"))
    )
    (net (code "59") (name "IR_2_MISO") (class "Default")
      (node (ref "J703") (pin "1") (pinfunction "1_1") (pintype "passive"))
      (node (ref "U701") (pin "6") (pinfunction "PB1(MISO)_6") (pintype "bidirectional"))
    )
    (net (code "60") (name "IR_2_MOSI") (class "Default")
      (node (ref "J703") (pin "4") (pinfunction "4_4") (pintype "passive"))
      (node (ref "U701") (pin "5") (pinfunction "PB0(MOSI)_5") (pintype "bidirectional"))
    )
    (net (code "61") (name "IR_2_RST") (class "Default")
      (node (ref "J703") (pin "5") (pinfunction "5_5") (pintype "passive"))
      (node (ref "R703") (pin "1") (pinfunction "1_1") (pintype "passive"))
      (node (ref "S701") (pin "3") (pinfunction "2_3") (pintype "passive"))
      (node (ref "S701") (pin "4") (pinfunction "2_4") (pintype "passive"))
      (node (ref "U701") (pin "1") (pinfunction "PB5(NRES)_1") (pintype "bidirectional"))
    )
    (net (code "62") (name "IR_2_SCK") (class "Default")
      (node (ref "J703") (pin "3") (pinfunction "3_3") (pintype "passive"))
      (node (ref "R702") (pin "1") (pinfunction "1_1") (pintype "passive"))
      (node (ref "U701") (pin "7") (pinfunction "PB2(SCK/ADC1)_7") (pintype "bidirectional"))
    )
    (net (code "63") (name "IR_IN") (class "Default")
      (node (ref "D702") (pin "A") (pinfunction "A_A") (pintype "passive"))
      (node (ref "J1606") (pin "1") (pinfunction "1_1") (pintype "passive"))
      (node (ref "U702") (pin "2") (pinfunction "PB3(ADC3)_2") (pintype "bidirectional"))
    )
    (net (code "64") (name "IR_OUT") (class "Default")
      (node (ref "D701") (pin "A") (pinfunction "A_A") (pintype "passive"))
      (node (ref "J1607") (pin "2") (pinfunction "2_2") (pintype "passive"))
      (node (ref "S703") (pin "2") (pinfunction "P_2") (pintype "passive"))
    )
    (net (code "65") (name "IR_OUT_SWITCH") (class "Default")
      (node (ref "S703") (pin "3") (pinfunction "S_3") (pintype "passive"))
      (node (ref "U701") (pin "3") (pinfunction "PB4(ADC2)_3") (pintype "bidirectional"))
    )
    (net (code "66") (name "IR_VCC") (class "Default")
      (node (ref "C701") (pin "2") (pinfunction "2_2") (pintype "passive"))
      (node (ref "C702") (pin "2") (pinfunction "2_2") (pintype "passive"))
      (node (ref "C703") (pin "+") (pinfunction "+_+") (pintype "passive"))
      (node (ref "D703") (pin "A") (pinfunction "A_A") (pintype "passive"))
      (node (ref "J701") (pin "3") (pinfunction "3_3") (pintype "passive"))
      (node (ref "J703") (pin "2") (pinfunction "2_2") (pintype "passive"))
      (node (ref "J704") (pin "2") (pinfunction "2_2") (pintype "passive"))
      (node (ref "R701") (pin "1") (pinfunction "1_1") (pintype "passive"))
      (node (ref "R703") (pin "2") (pinfunction "2_2") (pintype "passive"))
      (node (ref "R704") (pin "2") (pinfunction "2_2") (pintype "passive"))
      (node (ref "S703") (pin "1") (pinfunction "O_1") (pintype "passive"))
      (node (ref "TP701") (pin "TP") (pinfunction "TP_TP") (pintype "input"))
      (node (ref "U701") (pin "8") (pinfunction "VCC_8") (pintype "bidirectional"))
      (node (ref "U702") (pin "8") (pinfunction "VCC_8") (pintype "bidirectional"))
      (node (ref "U703") (pin "5") (pinfunction "OUT_5") (pintype "passive"))
    )
    (net (code "67") (name "LEVER_IN") (class "Default")
      (node (ref "D903") (pin "A") (pinfunction "A_A") (pintype "passive"))
      (node (ref "J1608") (pin "1") (pinfunction "1_1") (pintype "passive"))
      (node (ref "U901") (pin "2") (pinfunction "PB3(ADC3)_2") (pintype "bidirectional"))
    )
    (net (code "68") (name "LEVER_MISO") (class "Default")
      (node (ref "J903") (pin "1") (pinfunction "1_1") (pintype "passive"))
      (node (ref "U901") (pin "6") (pinfunction "PB1(MISO)_6") (pintype "bidirectional"))
    )
    (net (code "69") (name "LEVER_MOSI") (class "Default")
      (node (ref "J903") (pin "4") (pinfunction "4_4") (pintype "passive"))
      (node (ref "U901") (pin "5") (pinfunction "PB0(MOSI)_5") (pintype "bidirectional"))
    )
    (net (code "70") (name "LEVER_OUT") (class "Default")
      (node (ref "D902") (pin "A") (pinfunction "A_A") (pintype "passive"))
      (node (ref "J1609") (pin "2") (pinfunction "2_2") (pintype "passive"))
      (node (ref "J901") (pin "2") (pinfunction "2_2") (pintype "passive"))
      (node (ref "R903") (pin "1") (pinfunction "1_1") (pintype "passive"))
      (node (ref "S902") (pin "2") (pinfunction "P_2") (pintype "passive"))
    )
    (net (code "71") (name "LEVER_RST") (class "Default")
      (node (ref "J903") (pin "5") (pinfunction "5_5") (pintype "passive"))
      (node (ref "R904") (pin "1") (pinfunction "1_1") (pintype "passive"))
      (node (ref "S901") (pin "3") (pinfunction "2_3") (pintype "passive"))
      (node (ref "S901") (pin "4") (pinfunction "2_4") (pintype "passive"))
      (node (ref "U901") (pin "1") (pinfunction "PB5(NRES)_1") (pintype "bidirectional"))
    )
    (net (code "72") (name "LEVER_SCK") (class "Default")
      (node (ref "J903") (pin "3") (pinfunction "3_3") (pintype "passive"))
      (node (ref "R901") (pin "1") (pinfunction "1_1") (pintype "passive"))
      (node (ref "R902") (pin "1") (pinfunction "1_1") (pintype "passive"))
      (node (ref "U901") (pin "7") (pinfunction "PB2(SCK/ADC1)_7") (pintype "bidirectional"))
    )
    (net (code "73") (name "LEVER_VCC") (class "Default")
      (node (ref "C901") (pin "2") (pinfunction "2_2") (pintype "passive"))
      (node (ref "C902") (pin "+") (pinfunction "+_+") (pintype "passive"))
      (node (ref "D904") (pin "A") (pinfunction "A_A") (pintype "passive"))
      (node (ref "J901") (pin "1") (pinfunction "1_1") (pintype "passive"))
      (node (ref "J903") (pin "2") (pinfunction "2_2") (pintype "passive"))
      (node (ref "R904") (pin "2") (pinfunction "2_2") (pintype "passive"))
      (node (ref "S902") (pin "1") (pinfunction "O_1") (pintype "passive"))
      (node (ref "TP901") (pin "TP") (pinfunction "TP_TP") (pintype "input"))
      (node (ref "U901") (pin "8") (pinfunction "VCC_8") (pintype "bidirectional"))
      (node (ref "U902") (pin "5") (pinfunction "OUT_5") (pintype "passive"))
    )
    (net (code "74") (name "LIGHT_IN") (class "Default")
      (node (ref "D403") (pin "A") (pinfunction "A_A") (pintype "passive"))
      (node (ref "J1603") (pin "1") (pinfunction "1_1") (pintype "passive"))
      (node (ref "U402") (pin "1") (pinfunction "A_1") (pintype "input"))
    )
    (net (code "75") (name "LIGHT_MISO") (class "Default")
      (node (ref "J401") (pin "1") (pinfunction "1_1") (pintype "passive"))
      (node (ref "U403") (pin "6") (pinfunction "PB1(MISO)_6") (pintype "bidirectional"))
    )
    (net (code "76") (name "LIGHT_MOSI") (class "Default")
      (node (ref "J401") (pin "4") (pinfunction "4_4") (pintype "passive"))
      (node (ref "U403") (pin "5") (pinfunction "PB0(MOSI)_5") (pintype "bidirectional"))
    )
    (net (code "77") (name "LIGHT_OUT") (class "Default")
      (node (ref "D402") (pin "A") (pinfunction "A_A") (pintype "passive"))
      (node (ref "J1604") (pin "2") (pinfunction "2_2") (pintype "passive"))
      (node (ref "S402") (pin "2") (pinfunction "P_2") (pintype "passive"))
      (node (ref "U401") (pin "2") (pinfunction "A_2") (pintype "bidirectional"))
    )
    (net (code "78") (name "LIGHT_OUT_SWITCH") (class "Default")
      (node (ref "S402") (pin "3") (pinfunction "S_3") (pintype "passive"))
      (node (ref "U403") (pin "3") (pinfunction "PB4(ADC2)_3") (pintype "bidirectional"))
    )
    (net (code "79") (name "LIGHT_RST") (class "Default")
      (node (ref "J401") (pin "5") (pinfunction "5_5") (pintype "passive"))
      (node (ref "R405") (pin "1") (pinfunction "1_1") (pintype "passive"))
      (node (ref "S401") (pin "3") (pinfunction "2_3") (pintype "passive"))
      (node (ref "S401") (pin "4") (pinfunction "2_4") (pintype "passive"))
      (node (ref "U403") (pin "1") (pinfunction "PB5(NRES)_1") (pintype "bidirectional"))
    )
    (net (code "80") (name "LIGHT_SCK") (class "Default")
      (node (ref "J401") (pin "3") (pinfunction "3_3") (pintype "passive"))
      (node (ref "R401") (pin "2") (pinfunction "2_2") (pintype "passive"))
      (node (ref "R402") (pin "1") (pinfunction "P$1_1") (pintype "bidirectional"))
      (node (ref "U403") (pin "7") (pinfunction "PB2(SCK/ADC1)_7") (pintype "bidirectional"))
    )
    (net (code "81") (name "LIGHT_VCC") (class "Default")
      (node (ref "C401") (pin "2") (pinfunction "2_2") (pintype "passive"))
      (node (ref "C402") (pin "+") (pinfunction "+_+") (pintype "passive"))
      (node (ref "D404") (pin "A") (pinfunction "A_A") (pintype "passive"))
      (node (ref "J401") (pin "2") (pinfunction "2_2") (pintype "passive"))
      (node (ref "Q401") (pin "3") (pinfunction "C_3") (pintype "passive"))
      (node (ref "R402") (pin "2") (pinfunction "P$2_2") (pintype "bidirectional"))
      (node (ref "R405") (pin "2") (pinfunction "2_2") (pintype "passive"))
      (node (ref "S402") (pin "1") (pinfunction "O_1") (pintype "passive"))
      (node (ref "TP403") (pin "TP") (pinfunction "TP_TP") (pintype "input"))
      (node (ref "U401") (pin "5") (pinfunction "P$V+_5") (pintype "bidirectional"))
      (node (ref "U402") (pin "5") (pinfunction "VCC_5") (pintype "power_in"))
      (node (ref "U403") (pin "8") (pinfunction "VCC_8") (pintype "bidirectional"))
      (node (ref "U404") (pin "5") (pinfunction "OUT_5") (pintype "passive"))
    )
    (net (code "82") (name "Net-(D101-PadC)") (class "Default")
      (node (ref "D101") (pin "C") (pinfunction "C_C") (pintype "passive"))
      (node (ref "R102") (pin "2") (pinfunction "2_2") (pintype "passive"))
    )
    (net (code "83") (name "Net-(D102-PadC)") (class "Default")
      (node (ref "D102") (pin "C") (pinfunction "C_C") (pintype "passive"))
      (node (ref "R103") (pin "2") (pinfunction "2_2") (pintype "passive"))
    )
    (net (code "84") (name "Net-(D202-PadC)") (class "Default")
      (node (ref "D202") (pin "C") (pinfunction "C_C") (pintype "passive"))
      (node (ref "R205") (pin "2") (pinfunction "2_2") (pintype "passive"))
    )
    (net (code "85") (name "Net-(D203-PadC)") (class "Default")
      (node (ref "D203") (pin "C") (pinfunction "C_C") (pintype "passive"))
      (node (ref "R206") (pin "2") (pinfunction "2_2") (pintype "passive"))
    )
    (net (code "86") (name "Net-(D204-PadC)") (class "Default")
      (node (ref "D204") (pin "C") (pinfunction "C_C") (pintype "passive"))
      (node (ref "R207") (pin "2") (pinfunction "2_2") (pintype "passive"))
    )
    (net (code "87") (name "Net-(D302-PadC)") (class "Default")
      (node (ref "D302") (pin "C") (pinfunction "C_C") (pintype "passive"))
      (node (ref "R305") (pin "2") (pinfunction "2_2") (pintype "passive"))
    )
    (net (code "88") (name "Net-(D303-PadC)") (class "Default")
      (node (ref "D303") (pin "C") (pinfunction "C_C") (pintype "passive"))
      (node (ref "R306") (pin "2") (pinfunction "2_2") (pintype "passive"))
    )
    (net (code "89") (name "Net-(D304-PadC)") (class "Default")
      (node (ref "D304") (pin "C") (pinfunction "C_C") (pintype "passive"))
      (node (ref "R307") (pin "2") (pinfunction "2_2") (pintype "passive"))
    )
    (net (code "90") (name "Net-(D401-C)") (class "Default")
      (node (ref "D401") (pin "K") (pinfunction "C_K") (pintype "passive"))
      (node (ref "R404") (pin "1") (pinfunction "1_1") (pintype "passive"))
    )
    (net (code "91") (name "Net-(D402-PadC)") (class "Default")
      (node (ref "D402") (pin "C") (pinfunction "C_C") (pintype "passive"))
      (node (ref "R406") (pin "2") (pinfunction "2_2") (pintype "passive"))
    )
    (net (code "92") (name "Net-(D403-PadC)") (class "Default")
      (node (ref "D403") (pin "C") (pinfunction "C_C") (pintype "passive"))
      (node (ref "R407") (pin "2") (pinfunction "2_2") (pintype "passive"))
    )
    (net (code "93") (name "Net-(D404-PadC)") (class "Default")
      (node (ref "D404") (pin "C") (pinfunction "C_C") (pintype "passive"))
      (node (ref "R408") (pin "2") (pinfunction "2_2") (pintype "passive"))
    )
    (net (code "94") (name "Net-(D502-PadC)") (class "Default")
      (node (ref "D502") (pin "C") (pinfunction "C_C") (pintype "passive"))
      (node (ref "R505") (pin "2") (pinfunction "2_2") (pintype "passive"))
    )
    (net (code "95") (name "Net-(D503-PadC)") (class "Default")
      (node (ref "D503") (pin "C") (pinfunction "C_C") (pintype "passive"))
      (node (ref "R506") (pin "2") (pinfunction "2_2") (pintype "passive"))
    )
    (net (code "96") (name "Net-(D504-PadC)") (class "Default")
      (node (ref "D504") (pin "C") (pinfunction "C_C") (pintype "passive"))
      (node (ref "R507") (pin "2") (pinfunction "2_2") (pintype "passive"))
    )
    (net (code "97") (name "Net-(D602-PadC)") (class "Default")
      (node (ref "D602") (pin "C") (pinfunction "C_C") (pintype "passive"))
      (node (ref "R605") (pin "2") (pinfunction "2_2") (pintype "passive"))
    )
    (net (code "98") (name "Net-(D603-PadC)") (class "Default")
      (node (ref "D603") (pin "C") (pinfunction "C_C") (pintype "passive"))
      (node (ref "R606") (pin "2") (pinfunction "2_2") (pintype "passive"))
    )
    (net (code "99") (name "Net-(D604-PadC)") (class "Default")
      (node (ref "D604") (pin "C") (pinfunction "C_C") (pintype "passive"))
      (node (ref "R607") (pin "2") (pinfunction "2_2") (pintype "passive"))
    )
    (net (code "100") (name "Net-(D701-PadC)") (class "Default")
      (node (ref "D701") (pin "C") (pinfunction "C_C") (pintype "passive"))
      (node (ref "R705") (pin "2") (pinfunction "2_2") (pintype "passive"))
    )
    (net (code "101") (name "Net-(D702-PadC)") (class "Default")
      (node (ref "D702") (pin "C") (pinfunction "C_C") (pintype "passive"))
      (node (ref "R706") (pin "2") (pinfunction "2_2") (pintype "passive"))
    )
    (net (code "102") (name "Net-(D703-PadC)") (class "Default")
      (node (ref "D703") (pin "C") (pinfunction "C_C") (pintype "passive"))
      (node (ref "R707") (pin "2") (pinfunction "2_2") (pintype "passive"))
    )
    (net (code "103") (name "Net-(D802-PadC)") (class "Default")
      (node (ref "D802") (pin "C") (pinfunction "C_C") (pintype "passive"))
      (node (ref "R804") (pin "2") (pinfunction "2_2") (pintype "passive"))
    )
    (net (code "104") (name "Net-(D803-PadC)") (class "Default")
      (node (ref "D803") (pin "C") (pinfunction "C_C") (pintype "passive"))
      (node (ref "R805") (pin "2") (pinfunction "2_2") (pintype "passive"))
    )
    (net (code "105") (name "Net-(D804-PadC)") (class "Default")
      (node (ref "D804") (pin "C") (pinfunction "C_C") (pintype "passive"))
      (node (ref "R806") (pin "2") (pinfunction "2_2") (pintype "passive"))
    )
    (net (code "106") (name "Net-(D902-PadC)") (class "Default")
      (node (ref "D902") (pin "C") (pinfunction "C_C") (pintype "passive"))
      (node (ref "R905") (pin "2") (pinfunction "2_2") (pintype "passive"))
    )
    (net (code "107") (name "Net-(D903-PadC)") (class "Default")
      (node (ref "D903") (pin "C") (pinfunction "C_C") (pintype "passive"))
      (node (ref "R906") (pin "2") (pinfunction "2_2") (pintype "passive"))
    )
    (net (code "108") (name "Net-(D904-PadC)") (class "Default")
      (node (ref "D904") (pin "C") (pinfunction "C_C") (pintype "passive"))
      (node (ref "R907") (pin "2") (pinfunction "2_2") (pintype "passive"))
    )
    (net (code "109") (name "Net-(D1002-PadC)") (class "Default")
      (node (ref "D1002") (pin "C") (pinfunction "C_C") (pintype "passive"))
      (node (ref "R1006") (pin "2") (pinfunction "2_2") (pintype "passive"))
    )
    (net (code "110") (name "Net-(D1003-PadC)") (class "Default")
      (node (ref "D1003") (pin "C") (pinfunction "C_C") (pintype "passive"))
      (node (ref "R1007") (pin "2") (pinfunction "2_2") (pintype "passive"))
    )
    (net (code "111") (name "Net-(D1004-PadC)") (class "Default")
      (node (ref "D1004") (pin "C") (pinfunction "C_C") (pintype "passive"))
      (node (ref "R1008") (pin "2") (pinfunction "2_2") (pintype "passive"))
    )
    (net (code "112") (name "Net-(D1101-PadC)") (class "Default")
      (node (ref "D1101") (pin "C") (pinfunction "C_C") (pintype "passive"))
      (node (ref "R1104") (pin "2") (pinfunction "2_2") (pintype "passive"))
    )
    (net (code "113") (name "Net-(D1102-PadC)") (class "Default")
      (node (ref "D1102") (pin "C") (pinfunction "C_C") (pintype "passive"))
      (node (ref "R1105") (pin "2") (pinfunction "2_2") (pintype "passive"))
    )
    (net (code "114") (name "Net-(D1103-PadC)") (class "Default")
      (node (ref "D1103") (pin "C") (pinfunction "C_C") (pintype "passive"))
      (node (ref "R1106") (pin "2") (pinfunction "2_2") (pintype "passive"))
    )
    (net (code "115") (name "Net-(D1201-PadC)") (class "Default")
      (node (ref "D1201") (pin "C") (pinfunction "C_C") (pintype "passive"))
      (node (ref "R1204") (pin "2") (pinfunction "2_2") (pintype "passive"))
    )
    (net (code "116") (name "Net-(D1202-PadC)") (class "Default")
      (node (ref "D1202") (pin "C") (pinfunction "C_C") (pintype "passive"))
      (node (ref "R1205") (pin "2") (pinfunction "2_2") (pintype "passive"))
    )
    (net (code "117") (name "Net-(D1203-PadC)") (class "Default")
      (node (ref "D1203") (pin "C") (pinfunction "C_C") (pintype "passive"))
      (node (ref "R1206") (pin "2") (pinfunction "2_2") (pintype "passive"))
    )
    (net (code "118") (name "Net-(D1301-PadC)") (class "Default")
      (node (ref "D1301") (pin "C") (pinfunction "C_C") (pintype "passive"))
      (node (ref "R1304") (pin "2") (pinfunction "2_2") (pintype "passive"))
    )
    (net (code "119") (name "Net-(D1302-PadC)") (class "Default")
      (node (ref "D1302") (pin "C") (pinfunction "C_C") (pintype "passive"))
      (node (ref "R1305") (pin "2") (pinfunction "2_2") (pintype "passive"))
    )
    (net (code "120") (name "Net-(D1303-PadC)") (class "Default")
      (node (ref "D1303") (pin "C") (pinfunction "C_C") (pintype "passive"))
      (node (ref "R1306") (pin "2") (pinfunction "2_2") (pintype "passive"))
    )
    (net (code "121") (name "Net-(D1402-PadC)") (class "Default")
      (node (ref "D1402") (pin "C") (pinfunction "C_C") (pintype "passive"))
      (node (ref "R1404") (pin "2") (pinfunction "2_2") (pintype "passive"))
    )
    (net (code "122") (name "Net-(D1403-PadC)") (class "Default")
      (node (ref "D1403") (pin "C") (pinfunction "C_C") (pintype "passive"))
      (node (ref "R1405") (pin "2") (pinfunction "2_2") (pintype "passive"))
    )
    (net (code "123") (name "Net-(D1404-PadC)") (class "Default")
      (node (ref "D1404") (pin "C") (pinfunction "C_C") (pintype "passive"))
      (node (ref "R1406") (pin "2") (pinfunction "2_2") (pintype "passive"))
    )
    (net (code "124") (name "Net-(D1501-PadC)") (class "Default")
      (node (ref "D1501") (pin "C") (pinfunction "C_C") (pintype "passive"))
      (node (ref "R1502") (pin "2") (pinfunction "2_2") (pintype "passive"))
    )
    (net (code "125") (name "Net-(D1502-PadC)") (class "Default")
      (node (ref "D1502") (pin "C") (pinfunction "C_C") (pintype "passive"))
      (node (ref "R1503") (pin "2") (pinfunction "2_2") (pintype "passive"))
    )
    (net (code "126") (name "Net-(J501-Pad1)") (class "Default")
      (node (ref "J501") (pin "1") (pinfunction "1_1") (pintype "passive"))
      (node (ref "R501") (pin "1") (pinfunction "1_1") (pintype "passive"))
    )
    (net (code "127") (name "Net-(J701-Pad1)") (class "Default")
      (node (ref "J701") (pin "1") (pinfunction "1_1") (pintype "passive"))
      (node (ref "R702") (pin "2") (pinfunction "2_2") (pintype "passive"))
    )
    (net (code "128") (name "Net-(J702-Pad2)") (class "Default")
      (node (ref "J702") (pin "2") (pinfunction "2_2") (pintype "passive"))
      (node (ref "R701") (pin "2") (pinfunction "2_2") (pintype "passive"))
    )
    (net (code "129") (name "Net-(J1002-Pad1)") (class "Default")
      (node (ref "J1002") (pin "1") (pinfunction "1_1") (pintype "passive"))
      (node (ref "R1003") (pin "1") (pinfunction "1_1") (pintype "passive"))
    )
    (net (code "130") (name "Net-(JP201-Pad2)") (class "Default")
      (node (ref "JP201") (pin "2") (pinfunction "2_2") (pintype "passive"))
      (node (ref "JP202") (pin "2") (pinfunction "2_2") (pintype "passive"))
      (node (ref "R201") (pin "1") (pinfunction "1_1") (pintype "passive"))
      (node (ref "R202") (pin "1") (pinfunction "1_1") (pintype "passive"))
      (node (ref "TP201") (pin "TP") (pinfunction "TP_TP") (pintype "input"))
    )
    (net (code "131") (name "Net-(JP1401-Pad2)") (class "Default")
      (node (ref "JP1401") (pin "2") (pinfunction "2_2") (pintype "passive"))
      (node (ref "JP1402") (pin "2") (pinfunction "2_2") (pintype "passive"))
      (node (ref "R1402") (pin "1") (pinfunction "1_1") (pintype "passive"))
      (node (ref "R1403") (pin "1") (pinfunction "1_1") (pintype "passive"))
      (node (ref "TP1401") (pin "TP") (pinfunction "TP_TP") (pintype "input"))
    )
    (net (code "132") (name "Net-(Q201-D)") (class "Default")
      (node (ref "D201") (pin "A") (pinfunction "A_A") (pintype "passive"))
      (node (ref "J203") (pin "2") (pinfunction "2_2") (pintype "passive"))
      (node (ref "Q201") (pin "MB") (pinfunction "D_MB") (pintype "passive"))
    )
    (net (code "133") (name "Net-(Q201-G)") (class "Default")
      (node (ref "Q201") (pin "4") (pinfunction "G_4") (pintype "passive"))
      (node (ref "R201") (pin "2") (pinfunction "2_2") (pintype "passive"))
    )
    (net (code "134") (name "Net-(Q301-B)") (class "Default")
      (node (ref "Q301") (pin "1") (pinfunction "B_1") (pintype "passive"))
      (node (ref "R302") (pin "2") (pinfunction "2_2") (pintype "passive"))
    )
    (net (code "135") (name "Net-(Q301-E)") (class "Default")
      (node (ref "D301") (pin "A") (pinfunction "A_A") (pintype "passive"))
      (node (ref "Q301") (pin "2") (pinfunction "E_2") (pintype "passive"))
    )
    (net (code "136") (name "Net-(Q401-B)") (class "Default")
      (node (ref "Q401") (pin "1") (pinfunction "B_1") (pintype "passive"))
      (node (ref "R403") (pin "2") (pinfunction "2_2") (pintype "passive"))
    )
    (net (code "137") (name "Net-(Q401-E)") (class "Default")
      (node (ref "D401") (pin "A") (pinfunction "A_A") (pintype "passive"))
      (node (ref "Q401") (pin "2") (pinfunction "E_2") (pintype "passive"))
    )
    (net (code "138") (name "Net-(Q501-D)") (class "Default")
      (node (ref "D501") (pin "A") (pinfunction "A_A") (pintype "passive"))
      (node (ref "J502") (pin "2") (pinfunction "2_2") (pintype "passive"))
      (node (ref "Q501") (pin "MB") (pinfunction "D_MB") (pintype "passive"))
    )
    (net (code "139") (name "Net-(Q501-G)") (class "Default")
      (node (ref "Q501") (pin "4") (pinfunction "G_4") (pintype "passive"))
      (node (ref "R502") (pin "2") (pinfunction "2_2") (pintype "passive"))
    )
    (net (code "140") (name "Net-(Q601-D)") (class "Default")
      (node (ref "D601") (pin "A") (pinfunction "A_A") (pintype "passive"))
      (node (ref "J602") (pin "2") (pinfunction "2_2") (pintype "passive"))
      (node (ref "Q601") (pin "MB") (pinfunction "D_MB") (pintype "passive"))
    )
    (net (code "141") (name "Net-(Q601-G)") (class "Default")
      (node (ref "Q601") (pin "4") (pinfunction "G_4") (pintype "passive"))
      (node (ref "R601") (pin "2") (pinfunction "2_2") (pintype "passive"))
    )
    (net (code "142") (name "Net-(Q801-D)") (class "Default")
      (node (ref "D801") (pin "A") (pinfunction "A_A") (pintype "passive"))
      (node (ref "J802") (pin "2") (pinfunction "2_2") (pintype "passive"))
      (node (ref "Q801") (pin "MB") (pinfunction "D_MB") (pintype "passive"))
    )
    (net (code "143") (name "Net-(Q801-G)") (class "Default")
      (node (ref "Q801") (pin "4") (pinfunction "G_4") (pintype "passive"))
      (node (ref "R802") (pin "2") (pinfunction "2_2") (pintype "passive"))
    )
    (net (code "144") (name "Net-(Q901-D)") (class "Default")
      (node (ref "D901") (pin "A") (pinfunction "A_A") (pintype "passive"))
      (node (ref "J902") (pin "2") (pinfunction "2_2") (pintype "passive"))
      (node (ref "Q901") (pin "MB") (pinfunction "D_MB") (pintype "passive"))
    )
    (net (code "145") (name "Net-(Q901-G)") (class "Default")
      (node (ref "Q901") (pin "4") (pinfunction "G_4") (pintype "passive"))
      (node (ref "R901") (pin "2") (pinfunction "2_2") (pintype "passive"))
    )
    (net (code "146") (name "Net-(Q1001-D)") (class "Default")
      (node (ref "D1001") (pin "A") (pinfunction "A_A") (pintype "passive"))
      (node (ref "J1001") (pin "2") (pinfunction "2_2") (pintype "passive"))
      (node (ref "Q1001") (pin "MB") (pinfunction "D_MB") (pintype "passive"))
    )
    (net (code "147") (name "Net-(Q1001-G)") (class "Default")
      (node (ref "Q1001") (pin "4") (pinfunction "G_4") (pintype "passive"))
      (node (ref "R1001") (pin "2") (pinfunction "2_2") (pintype "passive"))
    )
    (net (code "148") (name "Net-(Q1401-D)") (class "Default")
      (node (ref "D1401") (pin "A") (pinfunction "A_A") (pintype "passive"))
      (node (ref "J1402") (pin "2") (pinfunction "2_2") (pintype "passive"))
      (node (ref "Q1401") (pin "MB") (pinfunction "D_MB") (pintype "passive"))
    )
    (net (code "149") (name "Net-(Q1401-G)") (class "Default")
      (node (ref "Q1401") (pin "4") (pinfunction "G_4") (pintype "passive"))
      (node (ref "R1402") (pin "2") (pinfunction "2_2") (pintype "passive"))
    )
    (net (code "150") (name "Net-(S101-2)") (class "Default")
      (node (ref "JP101") (pin "1") (pinfunction "1_1") (pintype "passive"))
      (node (ref "R101") (pin "2") (pinfunction "2_2") (pintype "passive"))
      (node (ref "S101") (pin "P$2") (pinfunction "2_P$2") (pintype "passive"))
      (node (ref "U101") (pin "2") (pinfunction "A_2") (pintype "bidirectional"))
    )
    (net (code "151") (name "Net-(U101A-Y)") (class "Default")
      (node (ref "JP102") (pin "1") (pinfunction "1_1") (pintype "passive"))
      (node (ref "U101") (pin "4") (pinfunction "Y_4") (pintype "bidirectional"))
    )
    (net (code "152") (name "Net-(U201A-Y)") (class "Default")
      (node (ref "JP202") (pin "1") (pinfunction "1_1") (pintype "passive"))
      (node (ref "U201") (pin "4") (pinfunction "Y_4") (pintype "bidirectional"))
    )
    (net (code "153") (name "Net-(U202-PB3(ADC3))") (class "Default")
      (node (ref "TP203") (pin "TP") (pinfunction "TP_TP") (pintype "input"))
      (node (ref "U202") (pin "2") (pinfunction "PB3(ADC3)_2") (pintype "bidirectional"))
    )
    (net (code "154") (name "Net-(U301A-Y)") (class "Default")
      (node (ref "TP301") (pin "TP") (pinfunction "TP_TP") (pintype "input"))
      (node (ref "U301") (pin "4") (pinfunction "Y_4") (pintype "bidirectional"))
      (node (ref "U302") (pin "2") (pinfunction "B_2") (pintype "input"))
    )
    (net (code "155") (name "Net-(U302A-Y)") (class "Default")
      (node (ref "R302") (pin "1") (pinfunction "1_1") (pintype "passive"))
      (node (ref "TP302") (pin "TP") (pinfunction "TP_TP") (pintype "input"))
      (node (ref "U302") (pin "4") (pinfunction "Y_4") (pintype "output"))
    )
    (net (code "156") (name "Net-(U303-PB3(ADC3))") (class "Default")
      (node (ref "TP303") (pin "TP") (pinfunction "TP_TP") (pintype "input"))
      (node (ref "U303") (pin "2") (pinfunction "PB3(ADC3)_2") (pintype "bidirectional"))
    )
    (net (code "157") (name "Net-(U401A-Y)") (class "Default")
      (node (ref "TP401") (pin "TP") (pinfunction "TP_TP") (pintype "input"))
      (node (ref "U401") (pin "4") (pinfunction "Y_4") (pintype "bidirectional"))
      (node (ref "U402") (pin "2") (pinfunction "B_2") (pintype "input"))
    )
    (net (code "158") (name "Net-(U402A-Y)") (class "Default")
      (node (ref "R403") (pin "1") (pinfunction "1_1") (pintype "passive"))
      (node (ref "TP402") (pin "TP") (pinfunction "TP_TP") (pintype "input"))
      (node (ref "U402") (pin "4") (pinfunction "Y_4") (pintype "output"))
    )
    (net (code "159") (name "Net-(U403-PB3(ADC3))") (class "Default")
      (node (ref "TP404") (pin "TP") (pinfunction "TP_TP") (pintype "input"))
      (node (ref "U403") (pin "2") (pinfunction "PB3(ADC3)_2") (pintype "bidirectional"))
    )
    (net (code "160") (name "Net-(U501A-Y)") (class "Default")
      (node (ref "TP501") (pin "TP") (pinfunction "TP_TP") (pintype "input"))
      (node (ref "U501") (pin "4") (pinfunction "Y_4") (pintype "bidirectional"))
      (node (ref "U502") (pin "2") (pinfunction "B_2") (pintype "input"))
    )
    (net (code "161") (name "Net-(U502A-Y)") (class "Default")
      (node (ref "R502") (pin "1") (pinfunction "1_1") (pintype "passive"))
      (node (ref "R503") (pin "1") (pinfunction "1_1") (pintype "passive"))
      (node (ref "TP502") (pin "TP") (pinfunction "TP_TP") (pintype "input"))
      (node (ref "U502") (pin "4") (pinfunction "Y_4") (pintype "output"))
    )
    (net (code "162") (name "Net-(U503-PB3(ADC3))") (class "Default")
      (node (ref "TP504") (pin "TP") (pinfunction "TP_TP") (pintype "input"))
      (node (ref "U503") (pin "2") (pinfunction "PB3(ADC3)_2") (pintype "bidirectional"))
    )
    (net (code "163") (name "Net-(U601A-Y)") (class "Default")
      (node (ref "TP602") (pin "TP") (pinfunction "TP_TP") (pintype "input"))
      (node (ref "U601") (pin "4") (pinfunction "Y_4") (pintype "bidirectional"))
      (node (ref "U602") (pin "2") (pinfunction "B_2") (pintype "input"))
    )
    (net (code "164") (name "Net-(U602A-Y)") (class "Default")
      (node (ref "R601") (pin "1") (pinfunction "1_1") (pintype "passive"))
      (node (ref "R602") (pin "1") (pinfunction "1_1") (pintype "passive"))
      (node (ref "TP603") (pin "TP") (pinfunction "TP_TP") (pintype "input"))
      (node (ref "U602") (pin "4") (pinfunction "Y_4") (pintype "output"))
    )
    (net (code "165") (name "Net-(U603-PB3(ADC3))") (class "Default")
      (node (ref "TP604") (pin "TP") (pinfunction "TP_TP") (pintype "input"))
      (node (ref "U603") (pin "2") (pinfunction "PB3(ADC3)_2") (pintype "bidirectional"))
    )
    (net (code "166") (name "Net-(U701-PB3(ADC3))") (class "Default")
      (node (ref "TP702") (pin "TP") (pinfunction "TP_TP") (pintype "input"))
      (node (ref "U701") (pin "2") (pinfunction "PB3(ADC3)_2") (pintype "bidirectional"))
    )
    (net (code "167") (name "Net-(U702-PB4(ADC2))") (class "Default")
      (node (ref "TP703") (pin "TP") (pinfunction "TP_TP") (pintype "input"))
      (node (ref "U702") (pin "3") (pinfunction "PB4(ADC2)_3") (pintype "bidirectional"))
    )
    (net (code "168") (name "Net-(U801A-Y)") (class "Default")
      (node (ref "TP802") (pin "TP") (pinfunction "TP_TP") (pintype "input"))
      (node (ref "U801") (pin "4") (pinfunction "Y_4") (pintype "bidirectional"))
      (node (ref "U802") (pin "2") (pinfunction "B_2") (pintype "input"))
    )
    (net (code "169") (name "Net-(U802A-Y)") (class "Default")
      (node (ref "R802") (pin "1") (pinfunction "1_1") (pintype "passive"))
      (node (ref "R803") (pin "1") (pinfunction "1_1") (pintype "passive"))
      (node (ref "TP803") (pin "TP") (pinfunction "TP_TP") (pintype "input"))
      (node (ref "U802") (pin "4") (pinfunction "Y_4") (pintype "output"))
    )
    (net (code "170") (name "Net-(U901-PB4(ADC2))") (class "Default")
      (node (ref "TP902") (pin "TP") (pinfunction "TP_TP") (pintype "input"))
      (node (ref "U901") (pin "3") (pinfunction "PB4(ADC2)_3") (pintype "bidirectional"))
    )
    (net (code "171") (name "Net-(U1001-PB4(ADC2))") (class "Default")
      (node (ref "TP1002") (pin "TP") (pinfunction "TP_TP") (pintype "input"))
      (node (ref "U1001") (pin "3") (pinfunction "PB4(ADC2)_3") (pintype "bidirectional"))
    )
    (net (code "172") (name "Net-(U1101-AOUT1)") (class "Default")
      (node (ref "J1102") (pin "1") (pinfunction "1_1") (pintype "passive"))
      (node (ref "U1101") (pin "2") (pinfunction "AOUT1_2") (pintype "bidirectional"))
    )
    (net (code "173") (name "Net-(U1101-AOUT2)") (class "Default")
      (node (ref "J1102") (pin "2") (pinfunction "2_2") (pintype "passive"))
      (node (ref "U1101") (pin "3") (pinfunction "AOUT2_3") (pintype "bidirectional"))
    )
    (net (code "174") (name "Net-(U1102-PB4(ADC2))") (class "Default")
      (node (ref "TP1102") (pin "TP") (pinfunction "TP_TP") (pintype "input"))
      (node (ref "U1102") (pin "3") (pinfunction "PB4(ADC2)_3") (pintype "bidirectional"))
    )
    (net (code "175") (name "Net-(U1201-AOUT1)") (class "Default")
      (node (ref "J1203") (pin "1") (pinfunction "1_1") (pintype "passive"))
      (node (ref "U1201") (pin "2") (pinfunction "AOUT1_2") (pintype "bidirectional"))
    )
    (net (code "176") (name "Net-(U1201-AOUT2)") (class "Default")
      (node (ref "J1203") (pin "2") (pinfunction "2_2") (pintype "passive"))
      (node (ref "U1201") (pin "3") (pinfunction "AOUT2_3") (pintype "bidirectional"))
    )
    (net (code "177") (name "Net-(U1202-PB4(ADC2))") (class "Default")
      (node (ref "TP1202") (pin "TP") (pinfunction "TP_TP") (pintype "input"))
      (node (ref "U1202") (pin "3") (pinfunction "PB4(ADC2)_3") (pintype "bidirectional"))
    )
    (net (code "178") (name "Net-(U1301-AOUT1)") (class "Default")
      (node (ref "J1303") (pin "1") (pinfunction "1_1") (pintype "passive"))
      (node (ref "U1301") (pin "2") (pinfunction "AOUT1_2") (pintype "bidirectional"))
    )
    (net (code "179") (name "Net-(U1301-AOUT2)") (class "Default")
      (node (ref "J1303") (pin "2") (pinfunction "2_2") (pintype "passive"))
      (node (ref "U1301") (pin "3") (pinfunction "AOUT2_3") (pintype "bidirectional"))
    )
    (net (code "180") (name "Net-(U1302-PB4(ADC2))") (class "Default")
      (node (ref "TP1302") (pin "TP") (pinfunction "TP_TP") (pintype "input"))
      (node (ref "U1302") (pin "3") (pinfunction "PB4(ADC2)_3") (pintype "bidirectional"))
    )
    (net (code "181") (name "Net-(U1401A-Y)") (class "Default")
      (node (ref "JP1402") (pin "1") (pinfunction "1_1") (pintype "passive"))
      (node (ref "U1401") (pin "4") (pinfunction "Y_4") (pintype "bidirectional"))
    )
    (net (code "182") (name "START_OUT") (class "Default")
      (node (ref "D101") (pin "A") (pinfunction "A_A") (pintype "passive"))
      (node (ref "J1601") (pin "2") (pinfunction "2_2") (pintype "passive"))
      (node (ref "JP101") (pin "2") (pinfunction "2_2") (pintype "passive"))
      (node (ref "JP102") (pin "2") (pinfunction "2_2") (pintype "passive"))
      (node (ref "S102") (pin "2") (pinfunction "P_2") (pintype "passive"))
    )
    (net (code "183") (name "START_VCC") (class "Default")
      (node (ref "C101") (pin "+") (pinfunction "+_+") (pintype "passive"))
      (node (ref "D102") (pin "A") (pinfunction "A_A") (pintype "passive"))
      (node (ref "R101") (pin "1") (pinfunction "1_1") (pintype "passive"))
      (node (ref "S102") (pin "1") (pinfunction "O_1") (pintype "passive"))
      (node (ref "TP101") (pin "TP") (pinfunction "TP_TP") (pintype "input"))
      (node (ref "U101") (pin "5") (pinfunction "P$V+_5") (pintype "bidirectional"))
      (node (ref "U102") (pin "5") (pinfunction "OUT_5") (pintype "passive"))
    )
    (net (code "184") (name "TIMER_IN") (class "Default")
      (node (ref "D1102") (pin "A") (pinfunction "A_A") (pintype "passive"))
      (node (ref "J1610") (pin "1") (pinfunction "1_1") (pintype "passive"))
      (node (ref "U1102") (pin "2") (pinfunction "PB3(ADC3)_2") (pintype "bidirectional"))
    )
    (net (code "185") (name "TIMER_MISO") (class "Default")
      (node (ref "J1104") (pin "1") (pinfunction "1_1") (pintype "passive"))
      (node (ref "U1101") (pin "9") (pinfunction "AIN2/EN_9") (pintype "bidirectional"))
      (node (ref "U1102") (pin "6") (pinfunction "PB1(MISO)_6") (pintype "bidirectional"))
    )
    (net (code "186") (name "TIMER_MOSI") (class "Default")
      (node (ref "J1104") (pin "4") (pinfunction "4_4") (pintype "passive"))
      (node (ref "U1101") (pin "10") (pinfunction "AIN1/PH_10") (pintype "bidirectional"))
      (node (ref "U1102") (pin "5") (pinfunction "PB0(MOSI)_5") (pintype "bidirectional"))
    )
    (net (code "187") (name "TIMER_OUT") (class "Default")
      (node (ref "D1101") (pin "A") (pinfunction "A_A") (pintype "passive"))
      (node (ref "J1101") (pin "2") (pinfunction "2_2") (pintype "passive"))
      (node (ref "J1611") (pin "2") (pinfunction "2_2") (pintype "passive"))
      (node (ref "R1101") (pin "1") (pinfunction "1_1") (pintype "passive"))
      (node (ref "S1102") (pin "2") (pinfunction "P_2") (pintype "passive"))
    )
    (net (code "188") (name "TIMER_RST") (class "Default")
      (node (ref "J1104") (pin "5") (pinfunction "5_5") (pintype "passive"))
      (node (ref "R1103") (pin "1") (pinfunction "1_1") (pintype "passive"))
      (node (ref "S1101") (pin "3") (pinfunction "2_3") (pintype "passive"))
      (node (ref "S1101") (pin "4") (pinfunction "2_4") (pintype "passive"))
      (node (ref "U1102") (pin "1") (pinfunction "PB5(NRES)_1") (pintype "bidirectional"))
    )
    (net (code "189") (name "TIMER_SCK") (class "Default")
      (node (ref "J1103") (pin "2") (pinfunction "2_2") (pintype "passive"))
      (node (ref "J1104") (pin "3") (pinfunction "3_3") (pintype "passive"))
      (node (ref "R1102") (pin "1") (pinfunction "1_1") (pintype "passive"))
      (node (ref "U1102") (pin "7") (pinfunction "PB2(SCK/ADC1)_7") (pintype "bidirectional"))
    )
    (net (code "190") (name "TIMER_VCC") (class "Default")
      (node (ref "C1101") (pin "2") (pinfunction "2_2") (pintype "passive"))
      (node (ref "C1103") (pin "1") (pinfunction "1_1") (pintype "passive"))
      (node (ref "D1103") (pin "A") (pinfunction "A_A") (pintype "passive"))
      (node (ref "IC1101") (pin "2") (pinfunction "VO_2") (pintype "passive"))
      (node (ref "J1101") (pin "1") (pinfunction "1_1") (pintype "passive"))
      (node (ref "J1103") (pin "1") (pinfunction "1_1") (pintype "passive"))
      (node (ref "J1104") (pin "2") (pinfunction "2_2") (pintype "passive"))
      (node (ref "R1103") (pin "2") (pinfunction "2_2") (pintype "passive"))
      (node (ref "S1102") (pin "1") (pinfunction "O_1") (pintype "passive"))
      (node (ref "TP1101") (pin "TP") (pinfunction "TP_TP") (pintype "input"))
      (node (ref "U1101") (pin "1") (pinfunction "VM_1") (pintype "bidirectional"))
      (node (ref "U1101") (pin "11") (pinfunction "MODE_11") (pintype "bidirectional"))
      (node (ref "U1101") (pin "12") (pinfunction "VCC_12") (pintype "bidirectional"))
      (node (ref "U1102") (pin "8") (pinfunction "VCC_8") (pintype "bidirectional"))
    )
    (net (code "191") (name "V_BATT") (class "Default")
      (node (ref "C1102") (pin "2") (pinfunction "2_2") (pintype "passive"))
      (node (ref "C1202") (pin "2") (pinfunction "2_2") (pintype "passive"))
      (node (ref "C1302") (pin "2") (pinfunction "2_2") (pintype "passive"))
      (node (ref "C1501") (pin "2") (pinfunction "2_2") (pintype "passive"))
      (node (ref "C1601") (pin "+") (pinfunction "+_+") (pintype "passive"))
      (node (ref "C1602") (pin "+") (pinfunction "+_+") (pintype "passive"))
      (node (ref "C1603") (pin "+") (pinfunction "+_+") (pintype "passive"))
      (node (ref "C1604") (pin "1") (pinfunction "1_1") (pintype "passive"))
      (node (ref "D1001") (pin "C") (pinfunction "C_C") (pintype "passive"))
      (node (ref "D1401") (pin "C") (pinfunction "C_C") (pintype "passive"))
      (node (ref "D1601") (pin "C") (pinfunction "C_C") (pintype "passive"))
      (node (ref "D201") (pin "C") (pinfunction "C_C") (pintype "passive"))
      (node (ref "D501") (pin "C") (pinfunction "C_C") (pintype "passive"))
      (node (ref "D601") (pin "C") (pinfunction "C_C") (pintype "passive"))
      (node (ref "D801") (pin "C") (pinfunction "C_C") (pintype "passive"))
      (node (ref "D901") (pin "C") (pinfunction "C_C") (pintype "passive"))
      (node (ref "IC1101") (pin "1") (pinfunction "VI_1") (pintype "input"))
      (node (ref "IC1201") (pin "1") (pinfunction "VI_1") (pintype "input"))
      (node (ref "IC1301") (pin "1") (pinfunction "VI_1") (pintype "input"))
      (node (ref "IC1501") (pin "1") (pinfunction "VI_1") (pintype "input"))
      (node (ref "J1001") (pin "1") (pinfunction "1_1") (pintype "passive"))
      (node (ref "J1003") (pin "1") (pinfunction "1_1") (pintype "passive"))
      (node (ref "J1402") (pin "1") (pinfunction "1_1") (pintype "passive"))
      (node (ref "J201") (pin "2") (pinfunction "2_2") (pintype "passive"))
      (node (ref "J202") (pin "1") (pinfunction "1_1") (pintype "passive"))
      (node (ref "J203") (pin "1") (pinfunction "1_1") (pintype "passive"))
      (node (ref "J502") (pin "1") (pinfunction "1_1") (pintype "passive"))
      (node (ref "J602") (pin "1") (pinfunction "1_1") (pintype "passive"))
      (node (ref "J802") (pin "1") (pinfunction "1_1") (pintype "passive"))
      (node (ref "J902") (pin "1") (pinfunction "1_1") (pintype "passive"))
      (node (ref "U1002") (pin "1") (pinfunction "IN_1") (pintype "input"))
      (node (ref "U1002") (pin "3") (pinfunction "EN_3") (pintype "input"))
      (node (ref "U102") (pin "1") (pinfunction "IN_1") (pintype "input"))
      (node (ref "U102") (pin "3") (pinfunction "EN_3") (pintype "input"))
      (node (ref "U1402") (pin "1") (pinfunction "IN_1") (pintype "input"))
      (node (ref "U1402") (pin "3") (pinfunction "EN_3") (pintype "input"))
      (node (ref "U203") (pin "1") (pinfunction "IN_1") (pintype "input"))
      (node (ref "U203") (pin "3") (pinfunction "EN_3") (pintype "input"))
      (node (ref "U304") (pin "1") (pinfunction "IN_1") (pintype "input"))
      (node (ref "U304") (pin "3") (pinfunction "EN_3") (pintype "input"))
      (node (ref "U404") (pin "1") (pinfunction "IN_1") (pintype "input"))
      (node (ref "U404") (pin "3") (pinfunction "EN_3") (pintype "input"))
      (node (ref "U504") (pin "1") (pinfunction "IN_1") (pintype "input"))
      (node (ref "U504") (pin "3") (pinfunction "EN_3") (pintype "input"))
      (node (ref "U604") (pin "1") (pinfunction "IN_1") (pintype "input"))
      (node (ref "U604") (pin "3") (pinfunction "EN_3") (pintype "input"))
      (node (ref "U703") (pin "1") (pinfunction "IN_1") (pintype "input"))
      (node (ref "U703") (pin "3") (pinfunction "EN_3") (pintype "input"))
      (node (ref "U803") (pin "1") (pinfunction "IN_1") (pintype "input"))
      (node (ref "U803") (pin "3") (pinfunction "EN_3") (pintype "input"))
      (node (ref "U902") (pin "1") (pinfunction "IN_1") (pintype "input"))
      (node (ref "U902") (pin "3") (pinfunction "EN_3") (pintype "input"))
      (node (ref "X1601") (pin "1") (pinfunction "1_1") (pintype "passive"))
    )
    (net (code "192") (name "WATER_IN") (class "Default")
      (node (ref "D603") (pin "A") (pinfunction "A_A") (pintype "passive"))
      (node (ref "J1605") (pin "1") (pinfunction "1_1") (pintype "passive"))
      (node (ref "U602") (pin "1") (pinfunction "A_1") (pintype "input"))
    )
    (net (code "193") (name "WATER_MISO") (class "Default")
      (node (ref "J603") (pin "1") (pinfunction "1_1") (pintype "passive"))
      (node (ref "U603") (pin "6") (pinfunction "PB1(MISO)_6") (pintype "bidirectional"))
    )
    (net (code "194") (name "WATER_MOSI") (class "Default")
      (node (ref "J603") (pin "4") (pinfunction "4_4") (pintype "passive"))
      (node (ref "U603") (pin "5") (pinfunction "PB0(MOSI)_5") (pintype "bidirectional"))
    )
    (net (code "195") (name "WATER_OUT") (class "Default")
      (node (ref "D602") (pin "A") (pinfunction "A_A") (pintype "passive"))
      (node (ref "J1606") (pin "2") (pinfunction "2_2") (pintype "passive"))
      (node (ref "S602") (pin "2") (pinfunction "P_2") (pintype "passive"))
      (node (ref "U601") (pin "2") (pinfunction "A_2") (pintype "bidirectional"))
    )
    (net (code "196") (name "WATER_OUT_SWITCH") (class "Default")
      (node (ref "S602") (pin "3") (pinfunction "S_3") (pintype "passive"))
      (node (ref "U603") (pin "3") (pinfunction "PB4(ADC2)_3") (pintype "bidirectional"))
    )
    (net (code "197") (name "WATER_RST") (class "Default")
      (node (ref "J603") (pin "5") (pinfunction "5_5") (pintype "passive"))
      (node (ref "R604") (pin "1") (pinfunction "1_1") (pintype "passive"))
      (node (ref "S601") (pin "3") (pinfunction "2_3") (pintype "passive"))
      (node (ref "S601") (pin "4") (pinfunction "2_4") (pintype "passive"))
      (node (ref "U603") (pin "1") (pinfunction "PB5(NRES)_1") (pintype "bidirectional"))
    )
    (net (code "198") (name "WATER_SCK") (class "Default")
      (node (ref "J601") (pin "1") (pinfunction "1_1") (pintype "passive"))
      (node (ref "J603") (pin "3") (pinfunction "3_3") (pintype "passive"))
      (node (ref "R603") (pin "1") (pinfunction "1_1") (pintype "passive"))
      (node (ref "U603") (pin "7") (pinfunction "PB2(SCK/ADC1)_7") (pintype "bidirectional"))
    )
    (net (code "199") (name "WATER_VCC") (class "Default")
      (node (ref "C601") (pin "2") (pinfunction "2_2") (pintype "passive"))
      (node (ref "C602") (pin "+") (pinfunction "+_+") (pintype "passive"))
      (node (ref "D604") (pin "A") (pinfunction "A_A") (pintype "passive"))
      (node (ref "J603") (pin "2") (pinfunction "2_2") (pintype "passive"))
      (node (ref "R603") (pin "2") (pinfunction "2_2") (pintype "passive"))
      (node (ref "R604") (pin "2") (pinfunction "2_2") (pintype "passive"))
      (node (ref "S602") (pin "1") (pinfunction "O_1") (pintype "passive"))
      (node (ref "TP601") (pin "TP") (pinfunction "TP_TP") (pintype "input"))
      (node (ref "U601") (pin "5") (pinfunction "P$V+_5") (pintype "bidirectional"))
      (node (ref "U602") (pin "5") (pinfunction "VCC_5") (pintype "power_in"))
      (node (ref "U603") (pin "8") (pinfunction "VCC_8") (pintype "bidirectional"))
      (node (ref "U604") (pin "5") (pinfunction "OUT_5") (pintype "passive"))
    )
    (net (code "200") (name "unconnected-(S102-S-Pad3)") (class "Default")
      (node (ref "S102") (pin "3") (pinfunction "S_3") (pintype "passive"))
    )
    (net (code "201") (name "unconnected-(S801-S-Pad3)") (class "Default")
      (node (ref "S801") (pin "3") (pinfunction "S_3") (pintype "passive"))
    )
    (net (code "202") (name "unconnected-(S902-S-Pad3)") (class "Default")
      (node (ref "S902") (pin "3") (pinfunction "S_3") (pintype "passive"))
    )
    (net (code "203") (name "unconnected-(S1002-S-Pad3)") (class "Default")
      (node (ref "S1002") (pin "3") (pinfunction "S_3") (pintype "passive"))
    )
    (net (code "204") (name "unconnected-(S1102-S-Pad3)") (class "Default")
      (node (ref "S1102") (pin "3") (pinfunction "S_3") (pintype "passive"))
    )
    (net (code "205") (name "unconnected-(S1202-S-Pad3)") (class "Default")
      (node (ref "S1202") (pin "3") (pinfunction "S_3") (pintype "passive"))
    )
    (net (code "206") (name "unconnected-(S1302-S-Pad3)") (class "Default")
      (node (ref "S1302") (pin "3") (pinfunction "S_3") (pintype "passive"))
    )
    (net (code "207") (name "unconnected-(S1401-S-Pad3)") (class "Default")
      (node (ref "S1401") (pin "3") (pinfunction "S_3") (pintype "passive"))
    )
    (net (code "208") (name "unconnected-(U102-BP-Pad4)") (class "Default")
      (node (ref "U102") (pin "4") (pinfunction "BP_4") (pintype "input"))
    )
    (net (code "209") (name "unconnected-(U203-BP-Pad4)") (class "Default")
      (node (ref "U203") (pin "4") (pinfunction "BP_4") (pintype "input"))
    )
    (net (code "210") (name "unconnected-(U304-BP-Pad4)") (class "Default")
      (node (ref "U304") (pin "4") (pinfunction "BP_4") (pintype "input"))
    )
    (net (code "211") (name "unconnected-(U404-BP-Pad4)") (class "Default")
      (node (ref "U404") (pin "4") (pinfunction "BP_4") (pintype "input"))
    )
    (net (code "212") (name "unconnected-(U504-BP-Pad4)") (class "Default")
      (node (ref "U504") (pin "4") (pinfunction "BP_4") (pintype "input"))
    )
    (net (code "213") (name "unconnected-(U604-BP-Pad4)") (class "Default")
      (node (ref "U604") (pin "4") (pinfunction "BP_4") (pintype "input"))
    )
    (net (code "214") (name "unconnected-(U703-BP-Pad4)") (class "Default")
      (node (ref "U703") (pin "4") (pinfunction "BP_4") (pintype "input"))
    )
    (net (code "215") (name "unconnected-(U803-BP-Pad4)") (class "Default")
      (node (ref "U803") (pin "4") (pinfunction "BP_4") (pintype "input"))
    )
    (net (code "216") (name "unconnected-(U902-BP-Pad4)") (class "Default")
      (node (ref "U902") (pin "4") (pinfunction "BP_4") (pintype "input"))
    )
    (net (code "217") (name "unconnected-(U1002-BP-Pad4)") (class "Default")
      (node (ref "U1002") (pin "4") (pinfunction "BP_4") (pintype "input"))
    )
    (net (code "218") (name "unconnected-(U1101-BIN1{slash}PH-Pad8)") (class "Default")
      (node (ref "U1101") (pin "8") (pinfunction "BIN1/PH_8") (pintype "bidirectional"))
    )
    (net (code "219") (name "unconnected-(U1101-BIN2{slash}EN-Pad7)") (class "Default")
      (node (ref "U1101") (pin "7") (pinfunction "BIN2/EN_7") (pintype "bidirectional"))
    )
    (net (code "220") (name "unconnected-(U1101-BOUT1-Pad4)") (class "Default")
      (node (ref "U1101") (pin "4") (pinfunction "BOUT1_4") (pintype "bidirectional"))
    )
    (net (code "221") (name "unconnected-(U1101-BOUT2-Pad5)") (class "Default")
      (node (ref "U1101") (pin "5") (pinfunction "BOUT2_5") (pintype "bidirectional"))
    )
    (net (code "222") (name "unconnected-(U1201-BIN1{slash}PH-Pad8)") (class "Default")
      (node (ref "U1201") (pin "8") (pinfunction "BIN1/PH_8") (pintype "bidirectional"))
    )
    (net (code "223") (name "unconnected-(U1201-BIN2{slash}EN-Pad7)") (class "Default")
      (node (ref "U1201") (pin "7") (pinfunction "BIN2/EN_7") (pintype "bidirectional"))
    )
    (net (code "224") (name "unconnected-(U1201-BOUT1-Pad4)") (class "Default")
      (node (ref "U1201") (pin "4") (pinfunction "BOUT1_4") (pintype "bidirectional"))
    )
    (net (code "225") (name "unconnected-(U1201-BOUT2-Pad5)") (class "Default")
      (node (ref "U1201") (pin "5") (pinfunction "BOUT2_5") (pintype "bidirectional"))
    )
    (net (code "226") (name "unconnected-(U1301-BIN1{slash}PH-Pad8)") (class "Default")
      (node (ref "U1301") (pin "8") (pinfunction "BIN1/PH_8") (pintype "bidirectional"))
    )
    (net (code "227") (name "unconnected-(U1301-BIN2{slash}EN-Pad7)") (class "Default")
      (node (ref "U1301") (pin "7") (pinfunction "BIN2/EN_7") (pintype "bidirectional"))
    )
    (net (code "228") (name "unconnected-(U1301-BOUT1-Pad4)") (class "Default")
      (node (ref "U1301") (pin "4") (pinfunction "BOUT1_4") (pintype "bidirectional"))
    )
    (net (code "229") (name "unconnected-(U1301-BOUT2-Pad5)") (class "Default")
      (node (ref "U1301") (pin "5") (pinfunction "BOUT2_5") (pintype "bidirectional"))
    )
    (net (code "230") (name "unconnected-(U1402-BP-Pad4)") (class "Default")
      (node (ref "U1402") (pin "4") (pinfunction "BP_4") (pintype "input"))
    )
  )
)
